# Titan_v1p7.net
KiCad netlist of a schematic drawn in EAGLE
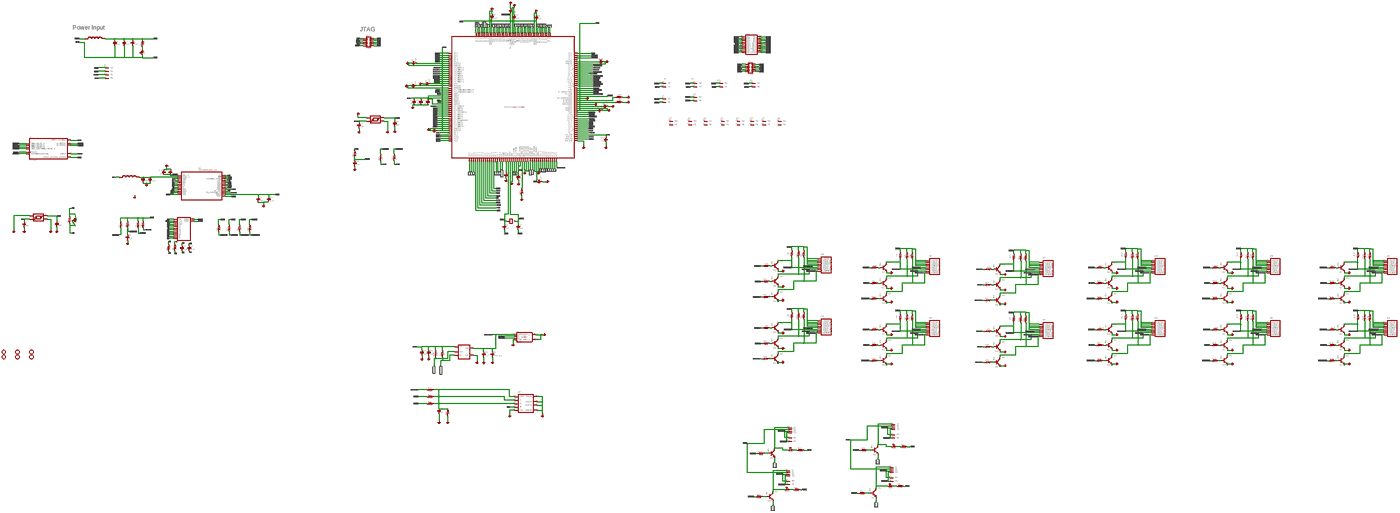
[diagram p0: schematic, sheet 1, overview]
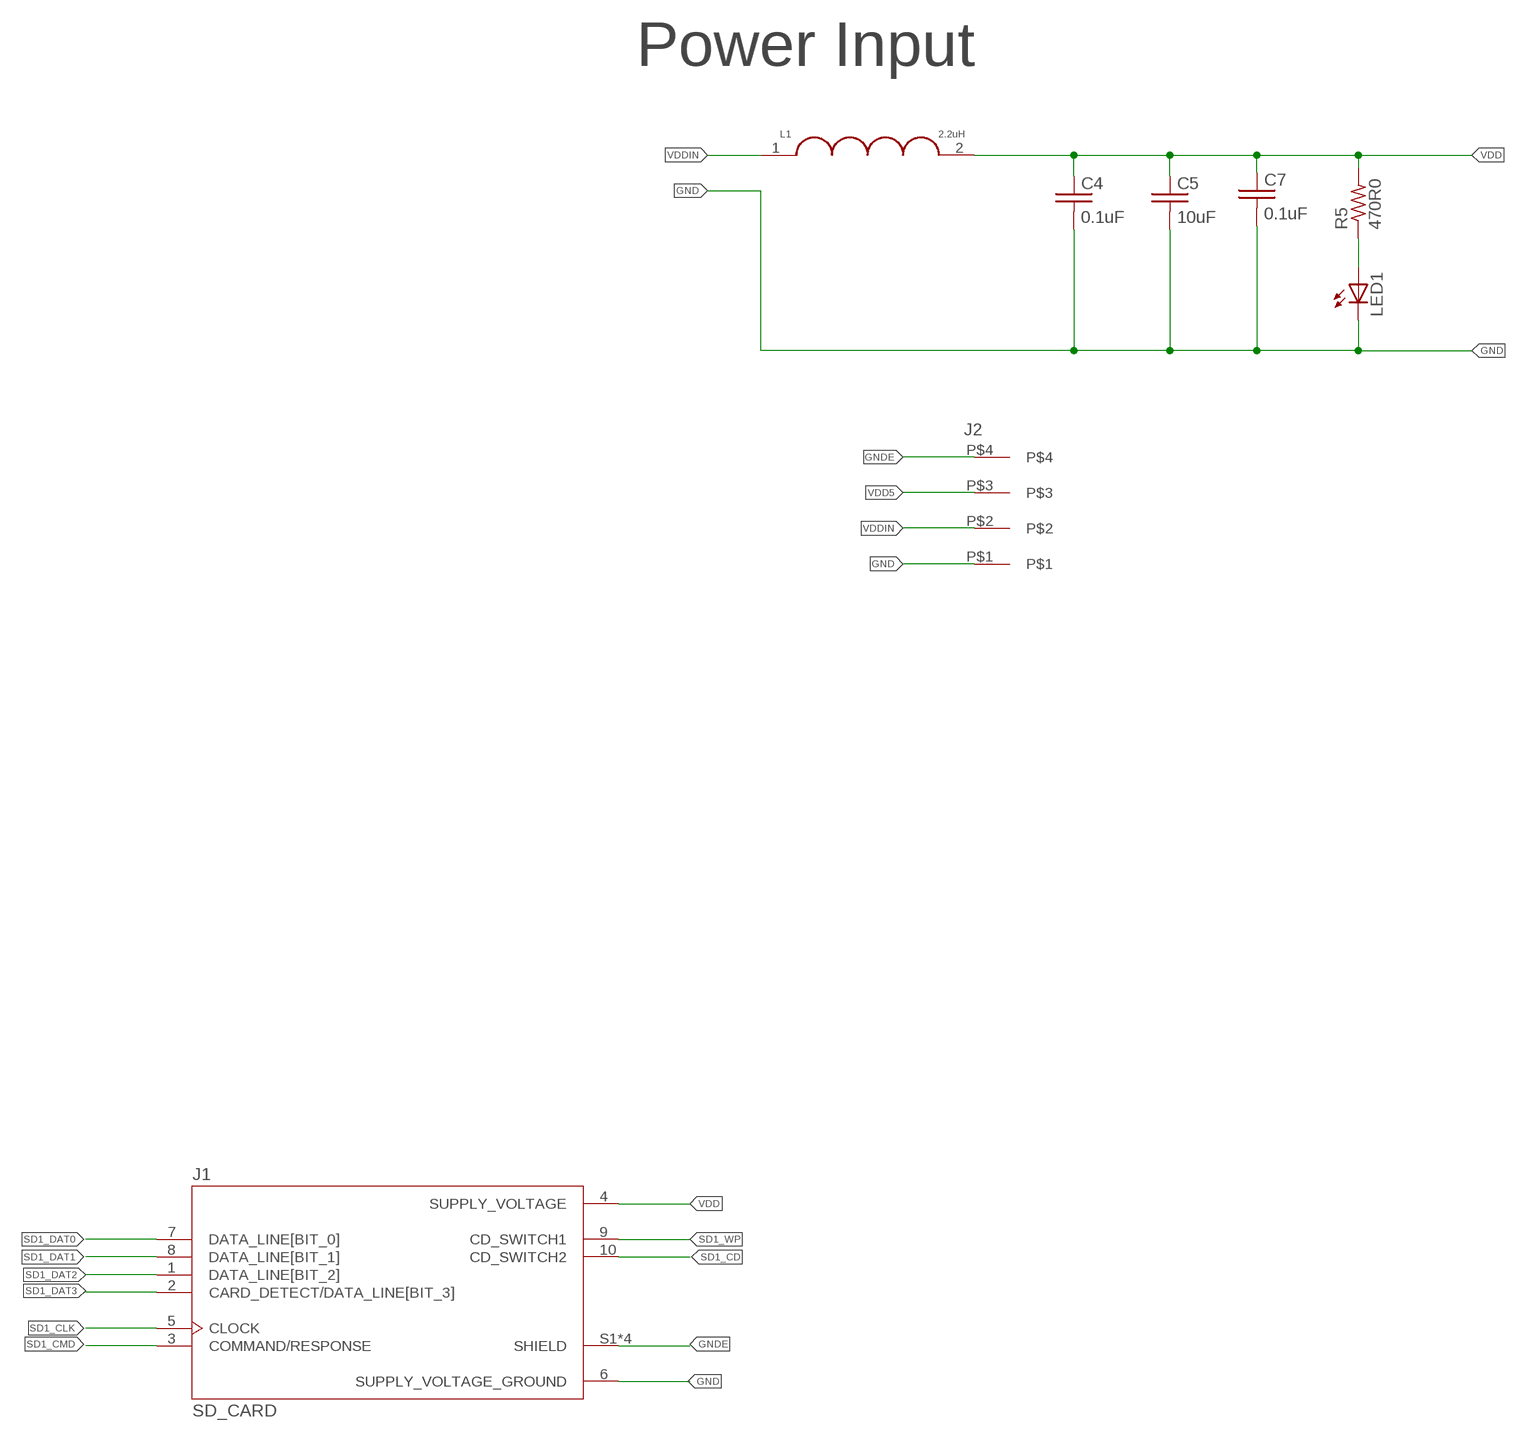
[diagram p1: schematic, sheet 1, part 1 of 8]
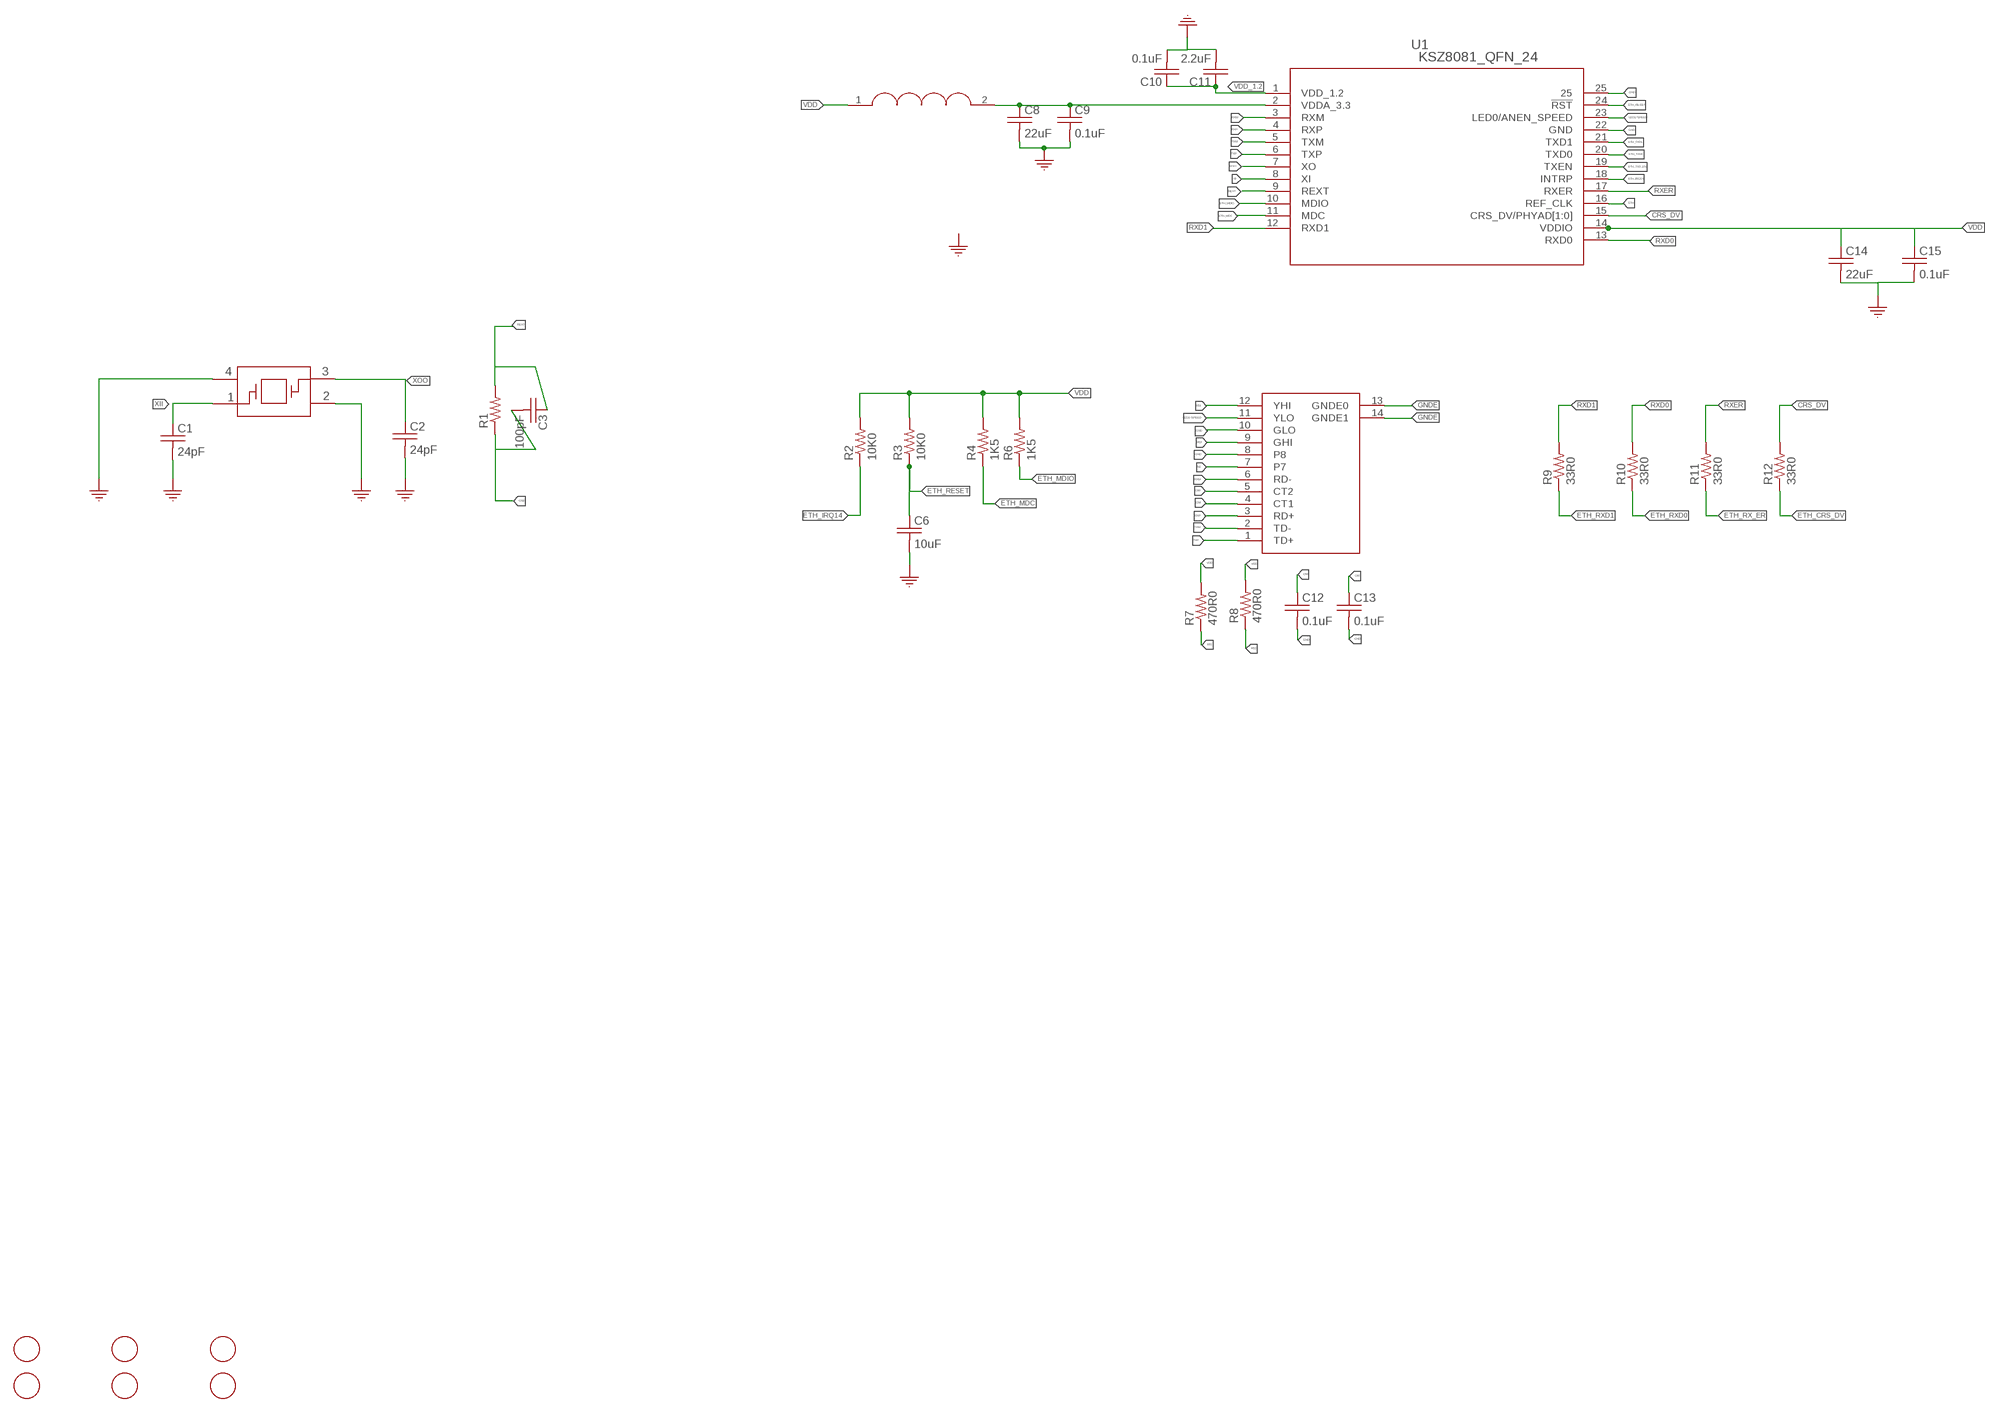
[diagram p2: schematic, sheet 1, part 2 of 8]
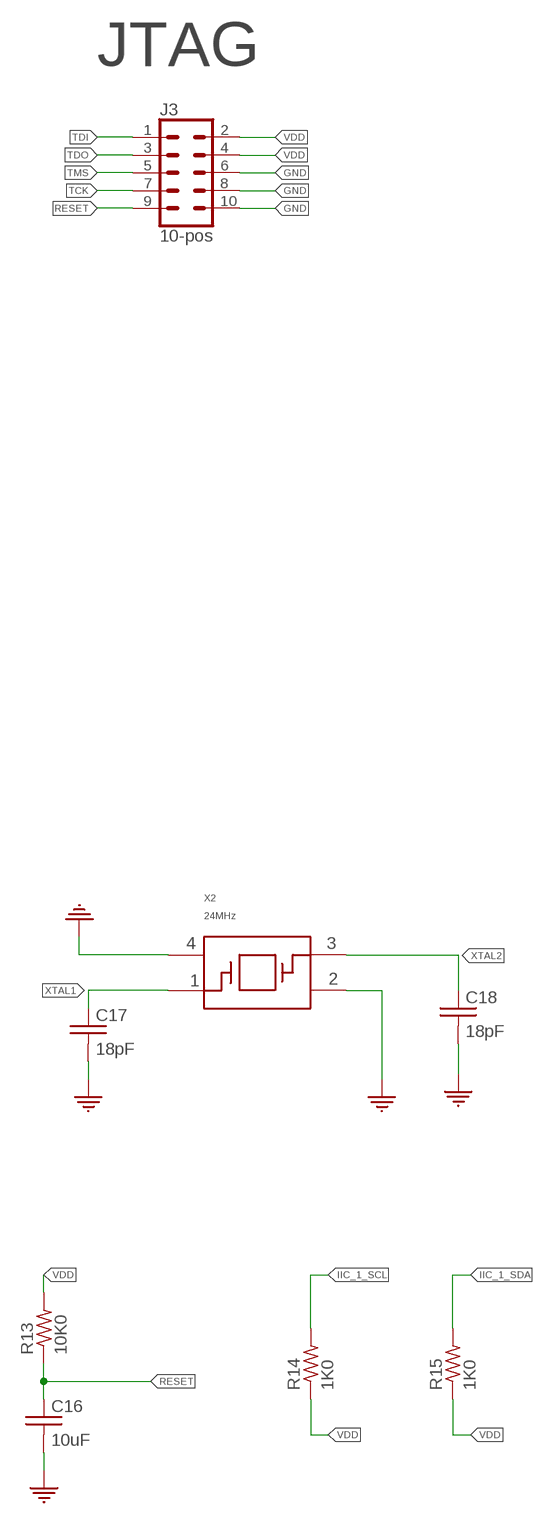
[diagram p3: schematic, sheet 1, part 3 of 8]
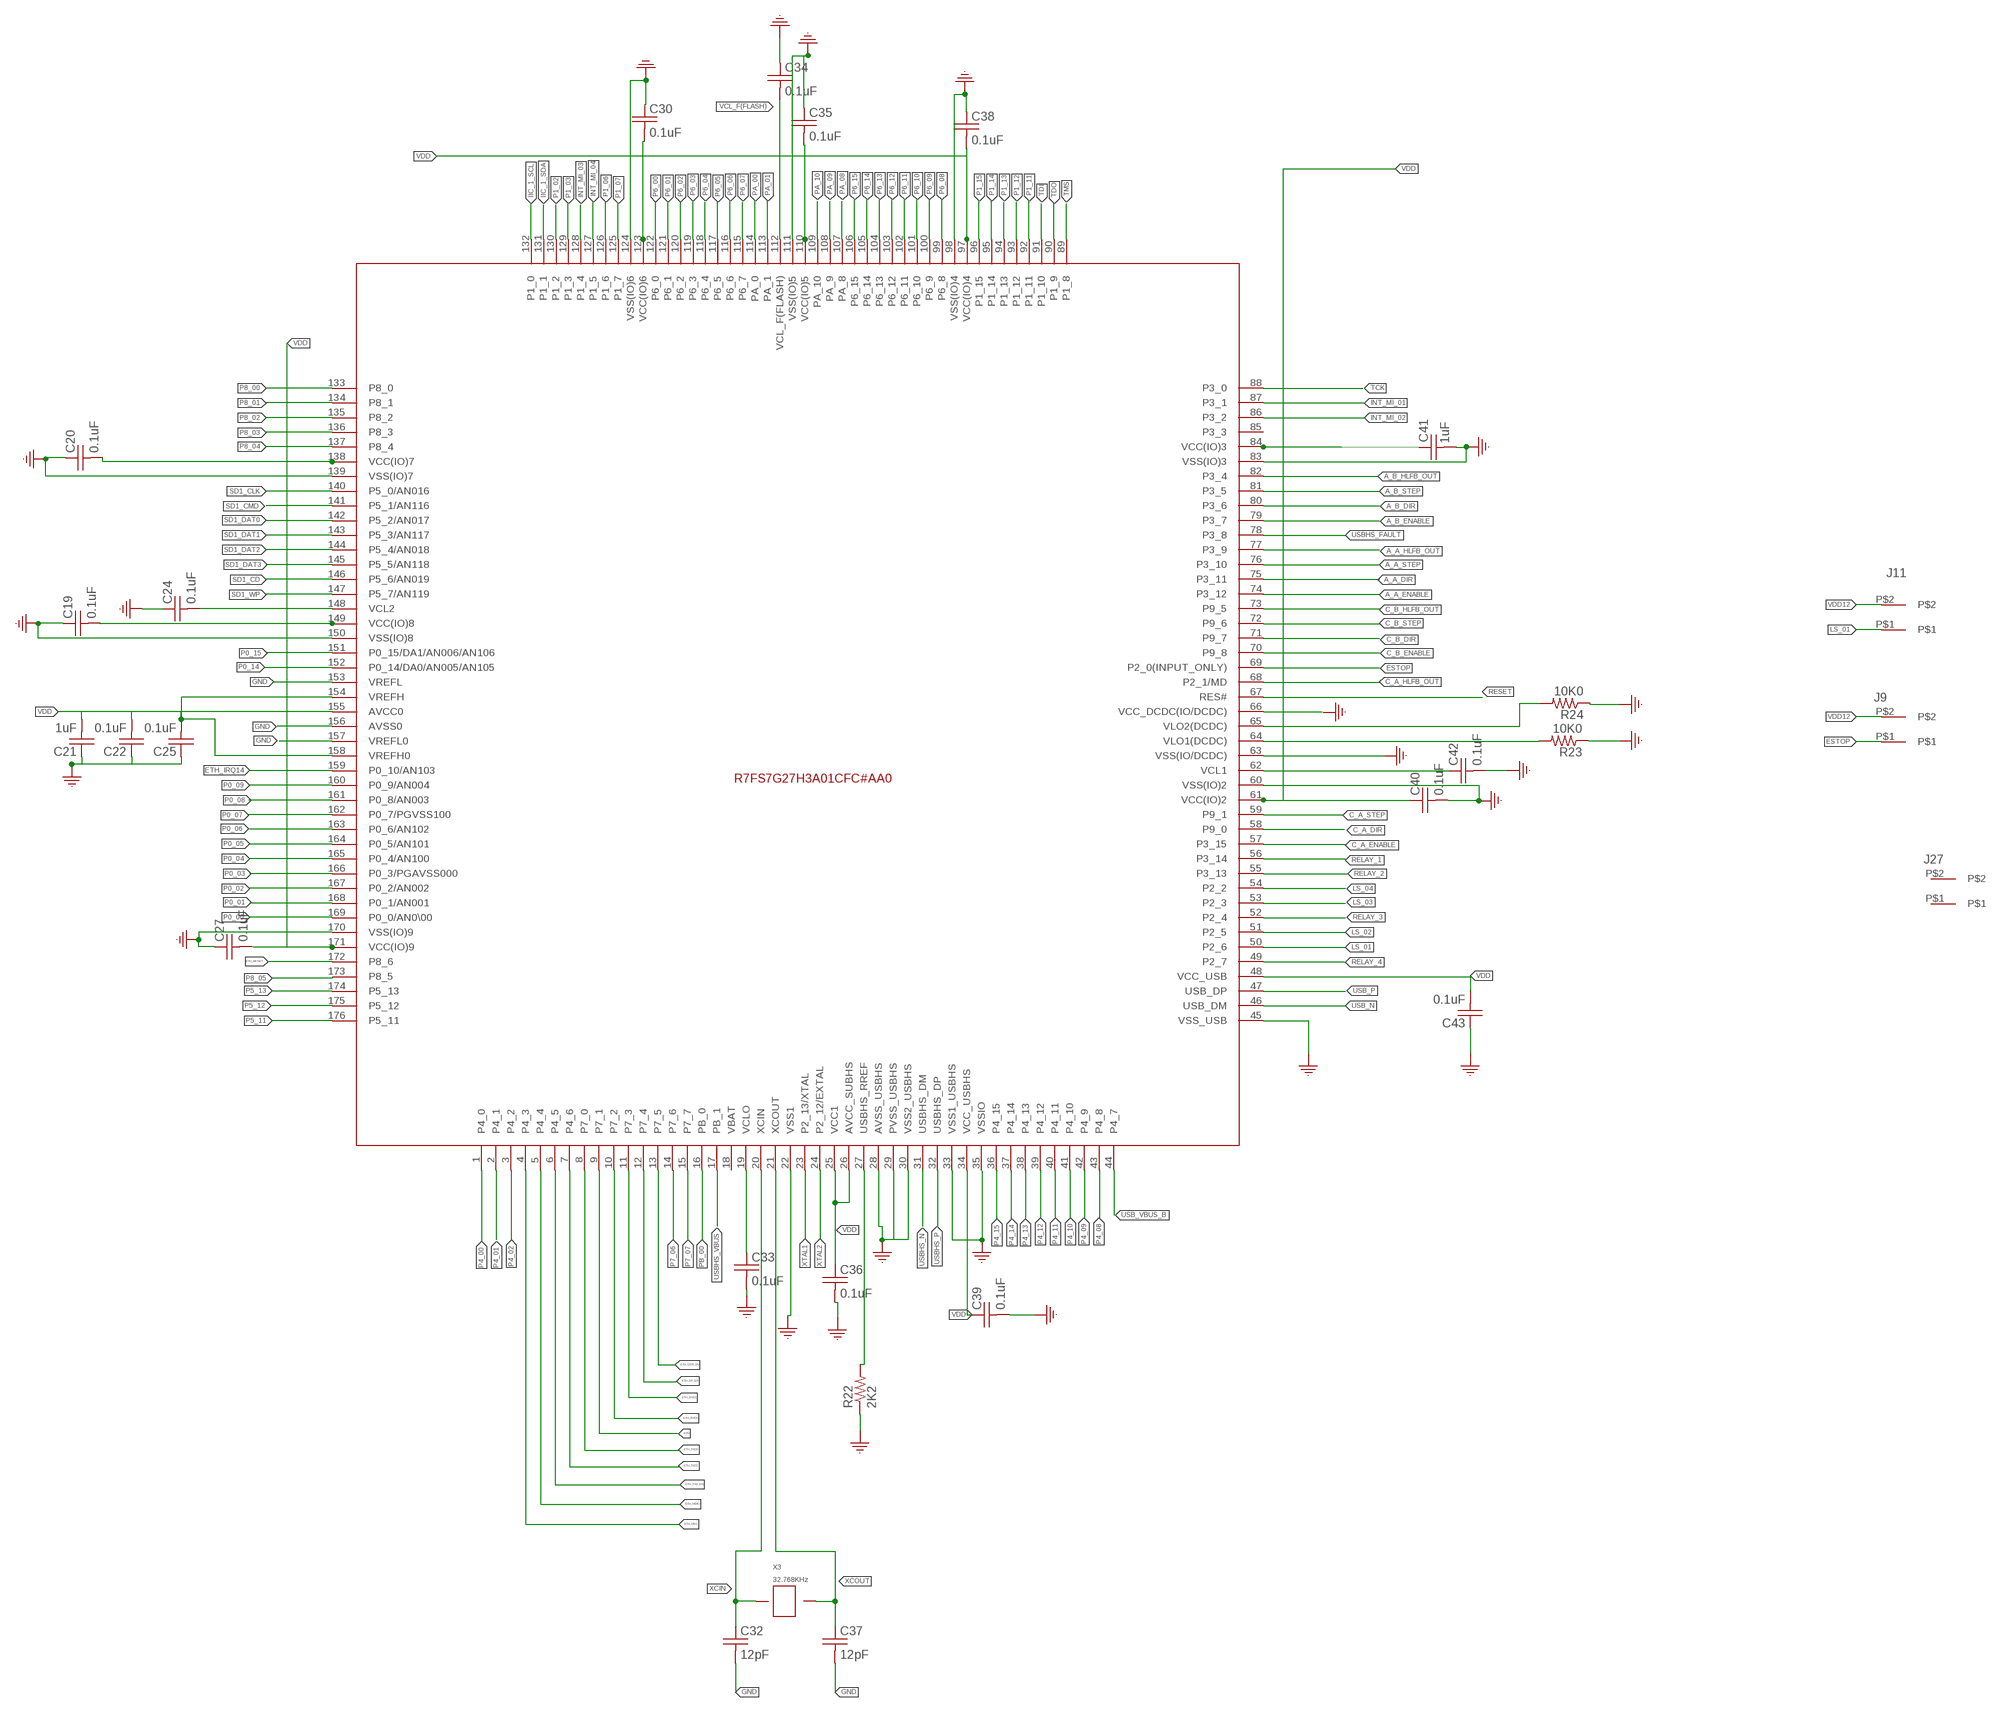
[diagram p4: schematic, sheet 1, part 4 of 8]
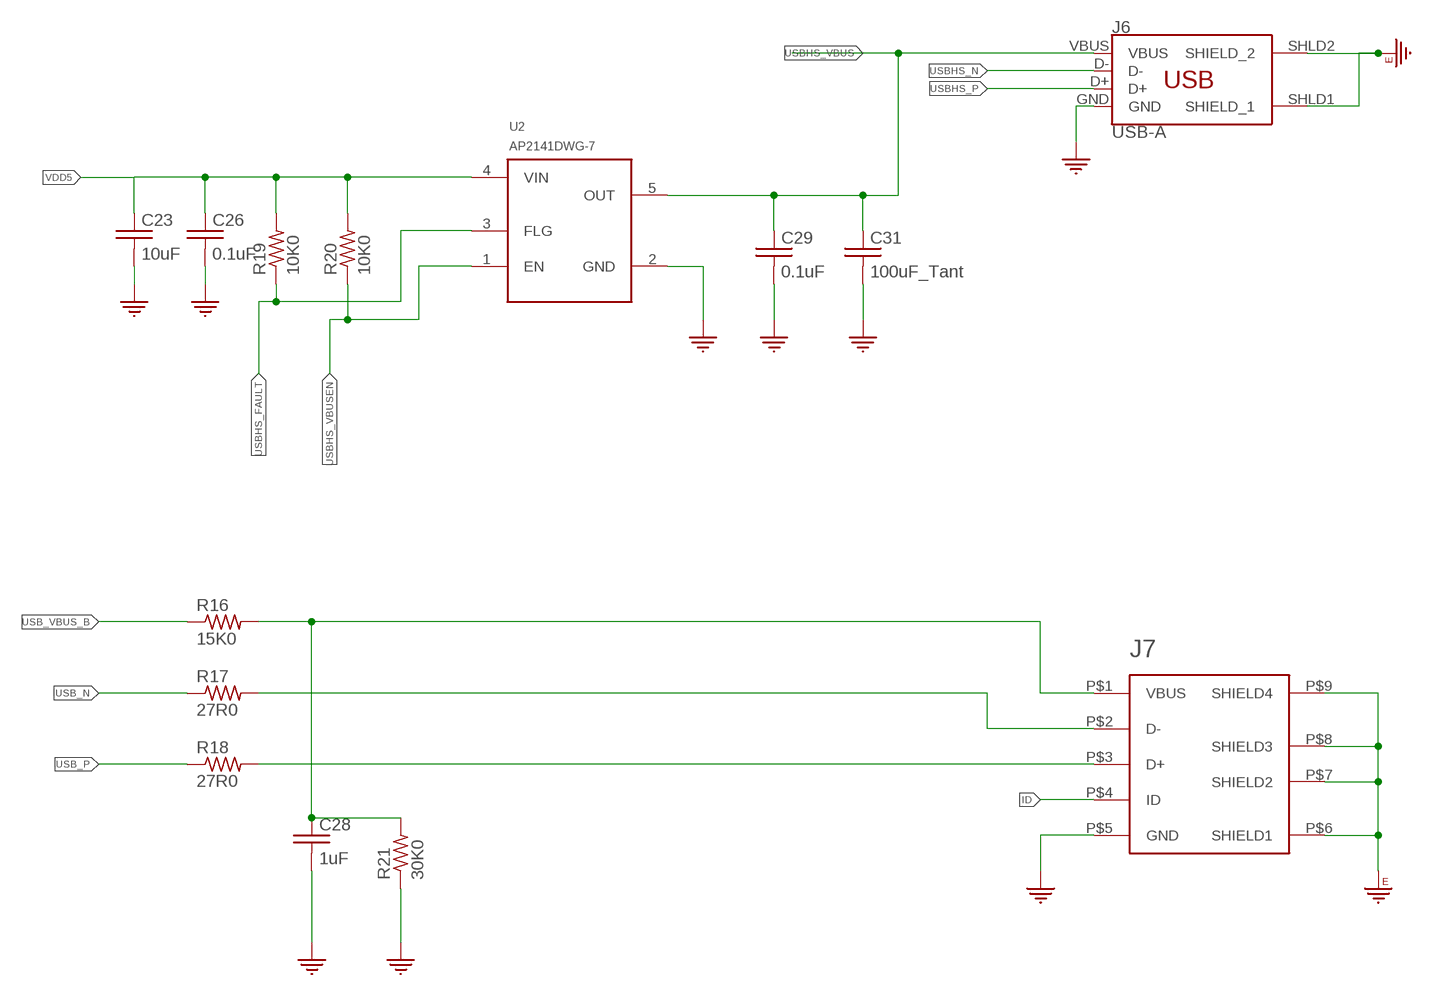
[diagram p5: schematic, sheet 1, part 5 of 8]
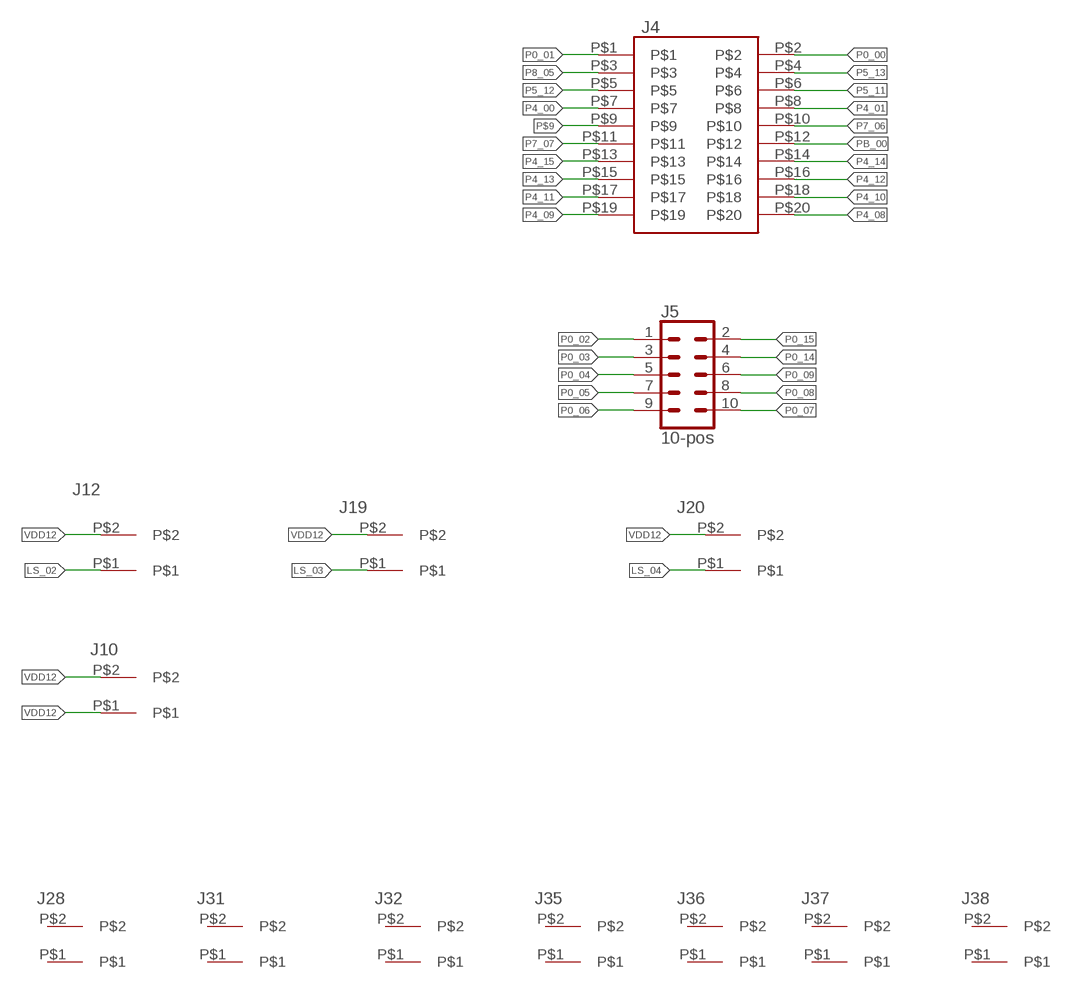
[diagram p6: schematic, sheet 1, part 6 of 8]
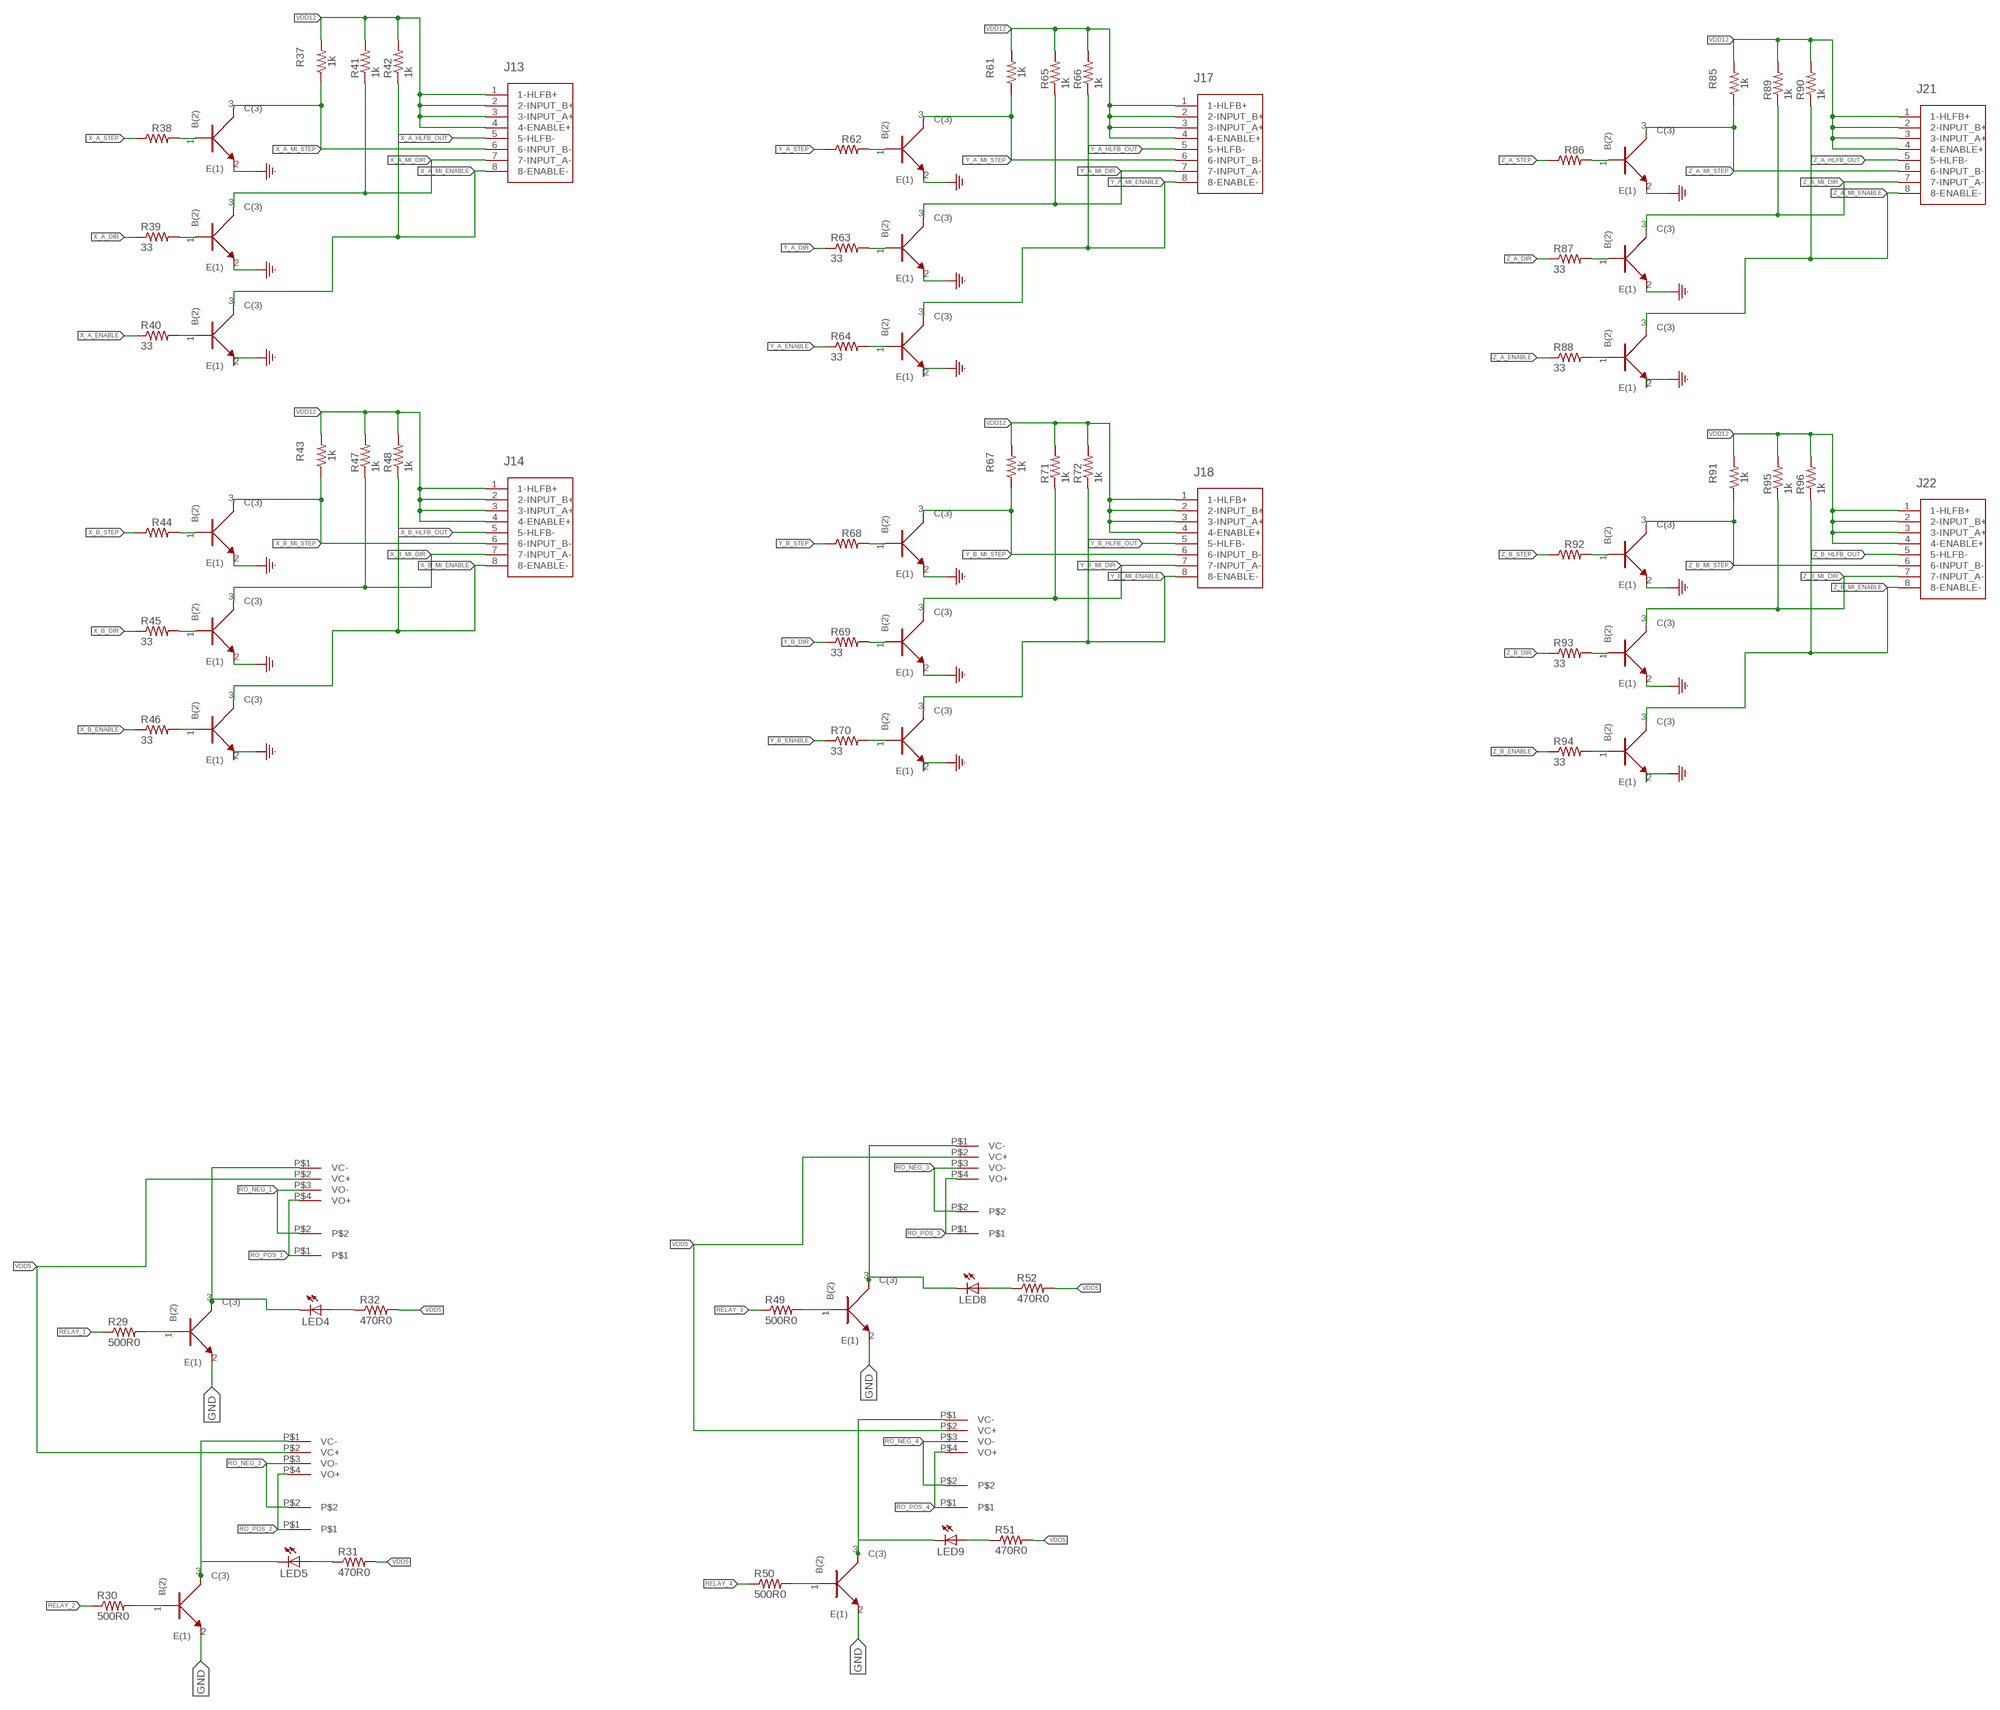
[diagram p7: schematic, sheet 1, part 7 of 8]
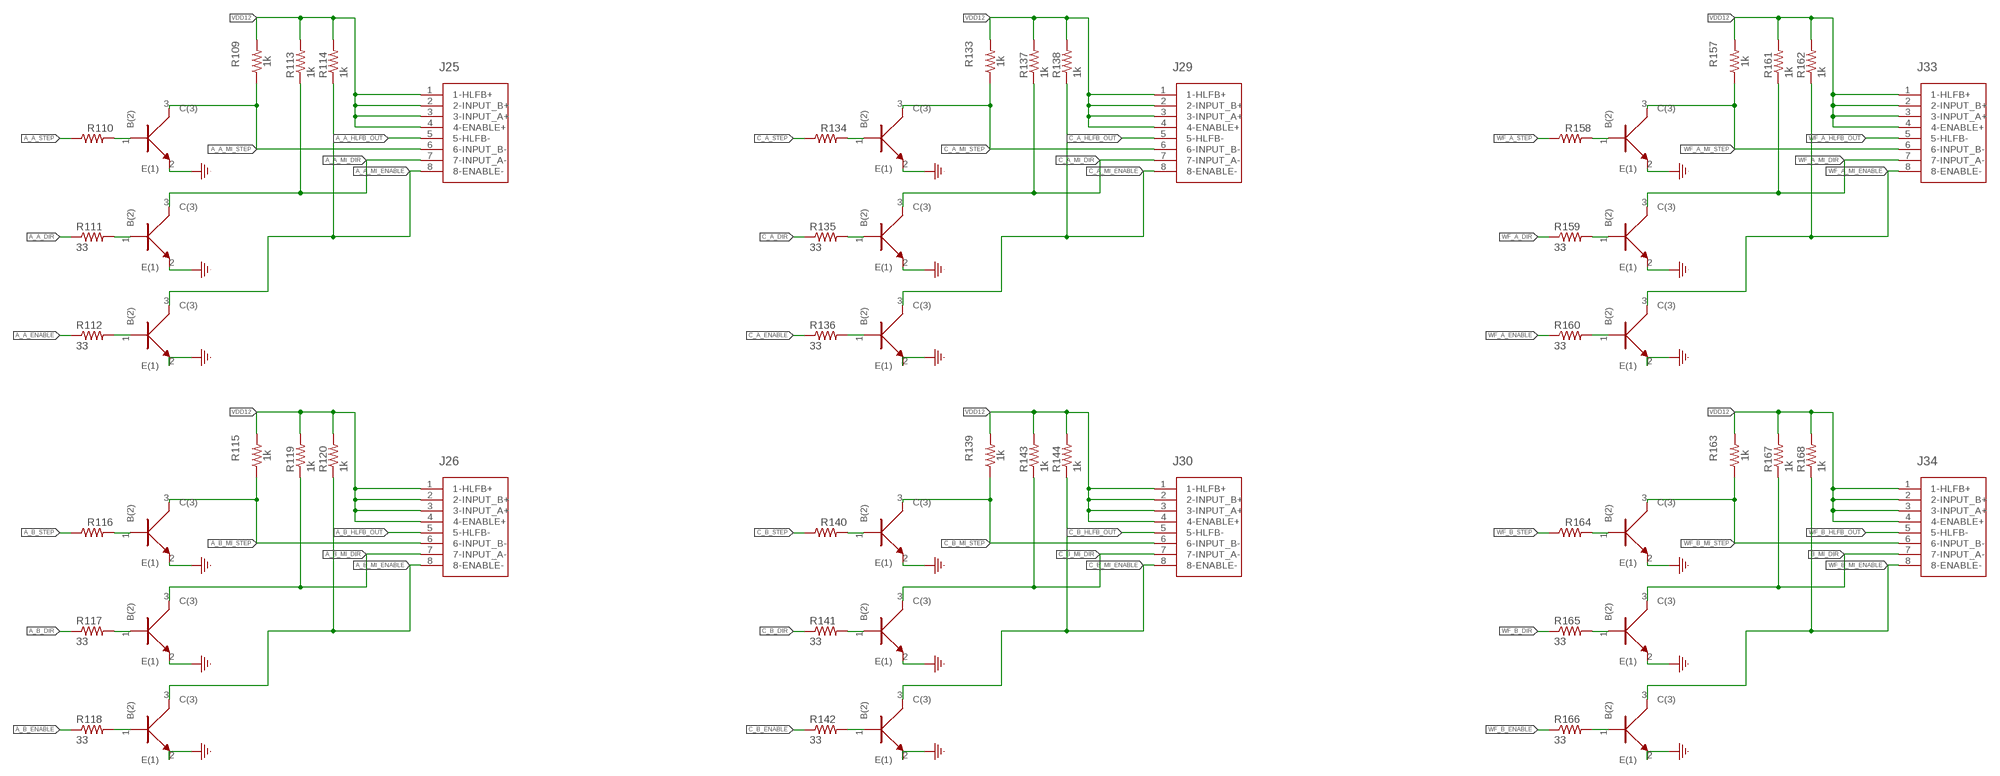
[diagram p8: schematic, sheet 1, part 8 of 8]

(export (version "E")
  (design (tool "Eeschema 10.0.6"))
  (components
    (comp (ref "AFID1")
      (value "FIDUCIAL_1MM")
      (footprint "eagle-import:FIDUCIAL_1MM")
      (libsource (lib "eagle-import") (part "FIDUCIAL_1MM"))
    )
    (comp (ref "AFID2")
      (value "FIDUCIAL_1MM")
      (footprint "eagle-import:FIDUCIAL_1MM")
      (libsource (lib "eagle-import") (part "FIDUCIAL_1MM"))
    )
    (comp (ref "AFID3")
      (value "FIDUCIAL_1MM")
      (footprint "eagle-import:FIDUCIAL_1MM")
      (libsource (lib "eagle-import") (part "FIDUCIAL_1MM"))
    )
    (comp (ref "AFID4")
      (value "FIDUCIAL_1MM")
      (footprint "eagle-import:FIDUCIAL_1MM")
      (libsource (lib "eagle-import") (part "FIDUCIAL_1MM"))
    )
    (comp (ref "AFID5")
      (value "FIDUCIAL_1MM")
      (footprint "eagle-import:FIDUCIAL_1MM")
      (libsource (lib "eagle-import") (part "FIDUCIAL_1MM"))
    )
    (comp (ref "AFID6")
      (value "FIDUCIAL_1MM")
      (footprint "eagle-import:FIDUCIAL_1MM")
      (libsource (lib "eagle-import") (part "FIDUCIAL_1MM"))
    )
    (comp (ref "C1")
      (value "24pF")
      (footprint "eagle-import:0402")
      (fields (field (name "PARTNO") "CC0402GRNPO9BN240"))
      (libsource (lib "eagle-import") (part "C_0402_24PF"))
    )
    (comp (ref "C2")
      (value "24pF")
      (footprint "eagle-import:0402")
      (fields (field (name "PARTNO") "CC0402GRNPO9BN240"))
      (libsource (lib "eagle-import") (part "C_0402_24PF"))
    )
    (comp (ref "C3")
      (value "100pF")
      (footprint "eagle-import:0402")
      (fields (field (name "PARTNO") "CL05C101JB5NNNC"))
      (libsource (lib "eagle-import") (part "C_0402_100PF"))
    )
    (comp (ref "C4")
      (value "0.1uF")
      (footprint "eagle-import:0402")
      (fields (field (name "PARTNO") "CL05F104ZO5NNNC"))
      (libsource (lib "eagle-import") (part "C_0402_0.1UF"))
    )
    (comp (ref "C5")
      (value "10uF")
      (footprint "eagle-import:0402")
      (fields (field (name "PARTNO") "CL05A106MP8NUB8"))
      (libsource (lib "eagle-import") (part "C_0402_10UF"))
    )
    (comp (ref "C6")
      (value "10uF")
      (footprint "eagle-import:0402")
      (fields (field (name "PARTNO") "CL05A106MP8NUB8"))
      (libsource (lib "eagle-import") (part "C_0402_10UF"))
    )
    (comp (ref "C7")
      (value "0.1uF")
      (footprint "eagle-import:0402")
      (fields (field (name "PARTNO") "CL05F104ZO5NNNC"))
      (libsource (lib "eagle-import") (part "C_0402_0.1UF"))
    )
    (comp (ref "C8")
      (value "22uF")
      (footprint "eagle-import:0402")
      (fields (field (name "PARTNO") "CL05A226MQ5N6J8"))
      (libsource (lib "eagle-import") (part "C_0402_22UF"))
    )
    (comp (ref "C9")
      (value "0.1uF")
      (footprint "eagle-import:0402")
      (fields (field (name "PARTNO") "CL05F104ZO5NNNC"))
      (libsource (lib "eagle-import") (part "C_0402_0.1UF"))
    )
    (comp (ref "C10")
      (value "0.1uF")
      (footprint "eagle-import:0402")
      (fields (field (name "PARTNO") "CL05F104ZO5NNNC"))
      (libsource (lib "eagle-import") (part "C_0402_0.1UF"))
    )
    (comp (ref "C11")
      (value "2.2uF")
      (footprint "eagle-import:0402")
      (fields (field (name "PARTNO") "GRM155C81C225ME15D"))
      (libsource (lib "eagle-import") (part "C_0402_2.2UF"))
    )
    (comp (ref "C12")
      (value "0.1uF")
      (footprint "eagle-import:0402")
      (fields (field (name "PARTNO") "CL05F104ZO5NNNC"))
      (libsource (lib "eagle-import") (part "C_0402_0.1UF"))
    )
    (comp (ref "C13")
      (value "0.1uF")
      (footprint "eagle-import:0402")
      (fields (field (name "PARTNO") "CL05F104ZO5NNNC"))
      (libsource (lib "eagle-import") (part "C_0402_0.1UF"))
    )
    (comp (ref "C14")
      (value "22uF")
      (footprint "eagle-import:0402")
      (fields (field (name "PARTNO") "CL05A226MQ5N6J8"))
      (libsource (lib "eagle-import") (part "C_0402_22UF"))
    )
    (comp (ref "C15")
      (value "0.1uF")
      (footprint "eagle-import:0402")
      (fields (field (name "PARTNO") "CL05F104ZO5NNNC"))
      (libsource (lib "eagle-import") (part "C_0402_0.1UF"))
    )
    (comp (ref "C16")
      (value "10uF")
      (footprint "eagle-import:0402")
      (fields (field (name "PARTNO") "CL05A106MP8NUB8"))
      (libsource (lib "eagle-import") (part "C_0402_10UF"))
    )
    (comp (ref "C17")
      (value "18pF")
      (footprint "eagle-import:0402")
      (fields (field (name "PARTNO") "UMK105CG180JV-F"))
      (libsource (lib "eagle-import") (part "C_0402_18PF"))
    )
    (comp (ref "C18")
      (value "18pF")
      (footprint "eagle-import:0402")
      (fields (field (name "PARTNO") "UMK105CG180JV-F"))
      (libsource (lib "eagle-import") (part "C_0402_18PF"))
    )
    (comp (ref "C19")
      (value "0.1uF")
      (footprint "eagle-import:0402")
      (fields (field (name "PARTNO") "CL05F104ZO5NNNC"))
      (libsource (lib "eagle-import") (part "C_0402_0.1UF"))
    )
    (comp (ref "C20")
      (value "0.1uF")
      (footprint "eagle-import:0402")
      (fields (field (name "PARTNO") "CL05F104ZO5NNNC"))
      (libsource (lib "eagle-import") (part "C_0402_0.1UF"))
    )
    (comp (ref "C21")
      (value "1uF")
      (footprint "eagle-import:0402")
      (fields (field (name "PARTNO") "CL05A105KO5NNNC"))
      (libsource (lib "eagle-import") (part "C_0402_1UF"))
    )
    (comp (ref "C22")
      (value "0.1uF")
      (footprint "eagle-import:0402")
      (fields (field (name "PARTNO") "CL05F104ZO5NNNC"))
      (libsource (lib "eagle-import") (part "C_0402_0.1UF"))
    )
    (comp (ref "C23")
      (value "10uF")
      (footprint "eagle-import:0402")
      (fields (field (name "PARTNO") "CL05A106MP8NUB8"))
      (libsource (lib "eagle-import") (part "C_0402_10UF"))
    )
    (comp (ref "C24")
      (value "0.1uF")
      (footprint "eagle-import:0402")
      (fields (field (name "PARTNO") "CL05F104ZO5NNNC"))
      (libsource (lib "eagle-import") (part "C_0402_0.1UF"))
    )
    (comp (ref "C25")
      (value "0.1uF")
      (footprint "eagle-import:0402")
      (fields (field (name "PARTNO") "CL05F104ZO5NNNC"))
      (libsource (lib "eagle-import") (part "C_0402_0.1UF"))
    )
    (comp (ref "C26")
      (value "0.1uF")
      (footprint "eagle-import:0402")
      (fields (field (name "PARTNO") "CL05F104ZO5NNNC"))
      (libsource (lib "eagle-import") (part "C_0402_0.1UF"))
    )
    (comp (ref "C27")
      (value "0.1uF")
      (footprint "eagle-import:0402")
      (fields (field (name "PARTNO") "CL05F104ZO5NNNC"))
      (libsource (lib "eagle-import") (part "C_0402_0.1UF"))
    )
    (comp (ref "C28")
      (value "1uF")
      (footprint "eagle-import:0402")
      (fields (field (name "PARTNO") "CL05A105KO5NNNC"))
      (libsource (lib "eagle-import") (part "C_0402_1UF"))
    )
    (comp (ref "C29")
      (value "0.1uF")
      (footprint "eagle-import:0402")
      (fields (field (name "PARTNO") "CL05F104ZO5NNNC"))
      (libsource (lib "eagle-import") (part "C_0402_0.1UF"))
    )
    (comp (ref "C30")
      (value "0.1uF")
      (footprint "eagle-import:0402")
      (fields (field (name "PARTNO") "CL05F104ZO5NNNC"))
      (libsource (lib "eagle-import") (part "C_0402_0.1UF"))
    )
    (comp (ref "C31")
      (value "100uF_Tant")
      (footprint "eagle-import:C1210")
      (fields (field (name "PARTNO") "TLJT107M010R0900"))
      (libsource (lib "eagle-import") (part "C_1210_100UF_TANT"))
    )
    (comp (ref "C32")
      (value "12pF")
      (footprint "eagle-import:0402")
      (fields (field (name "PARTNO") "CL05C120JB5NNNC"))
      (libsource (lib "eagle-import") (part "C_0402_12PF"))
    )
    (comp (ref "C33")
      (value "0.1uF")
      (footprint "eagle-import:0402")
      (fields (field (name "PARTNO") "CL05F104ZO5NNNC"))
      (libsource (lib "eagle-import") (part "C_0402_0.1UF"))
    )
    (comp (ref "C34")
      (value "0.1uF")
      (footprint "eagle-import:0402")
      (fields (field (name "PARTNO") "CL05F104ZO5NNNC"))
      (libsource (lib "eagle-import") (part "C_0402_0.1UF"))
    )
    (comp (ref "C35")
      (value "0.1uF")
      (footprint "eagle-import:0402")
      (fields (field (name "PARTNO") "CL05F104ZO5NNNC"))
      (libsource (lib "eagle-import") (part "C_0402_0.1UF"))
    )
    (comp (ref "C36")
      (value "0.1uF")
      (footprint "eagle-import:0402")
      (fields (field (name "PARTNO") "CL05F104ZO5NNNC"))
      (libsource (lib "eagle-import") (part "C_0402_0.1UF"))
    )
    (comp (ref "C37")
      (value "12pF")
      (footprint "eagle-import:0402")
      (fields (field (name "PARTNO") "CL05C120JB5NNNC"))
      (libsource (lib "eagle-import") (part "C_0402_12PF"))
    )
    (comp (ref "C38")
      (value "0.1uF")
      (footprint "eagle-import:0402")
      (fields (field (name "PARTNO") "CL05F104ZO5NNNC"))
      (libsource (lib "eagle-import") (part "C_0402_0.1UF"))
    )
    (comp (ref "C39")
      (value "0.1uF")
      (footprint "eagle-import:0402")
      (fields (field (name "PARTNO") "CL05F104ZO5NNNC"))
      (libsource (lib "eagle-import") (part "C_0402_0.1UF"))
    )
    (comp (ref "C40")
      (value "0.1uF")
      (footprint "eagle-import:0402")
      (fields (field (name "PARTNO") "CL05F104ZO5NNNC"))
      (libsource (lib "eagle-import") (part "C_0402_0.1UF"))
    )
    (comp (ref "C41")
      (value "1uF")
      (footprint "eagle-import:0402")
      (fields (field (name "PARTNO") "CL05A105KO5NNNC"))
      (libsource (lib "eagle-import") (part "C_0402_1UF"))
    )
    (comp (ref "C42")
      (value "0.1uF")
      (footprint "eagle-import:0402")
      (fields (field (name "PARTNO") "CL05F104ZO5NNNC"))
      (libsource (lib "eagle-import") (part "C_0402_0.1UF"))
    )
    (comp (ref "C43")
      (value "0.1uF")
      (footprint "eagle-import:0402")
      (fields (field (name "PARTNO") "CL05F104ZO5NNNC"))
      (libsource (lib "eagle-import") (part "C_0402_0.1UF"))
    )
    (comp (ref "FB1")
      (value "FB2_603")
      (footprint "eagle-import:0603")
      (fields (field (name "PARTNO") "BLM18PG121SN1D"))
      (libsource (lib "eagle-import") (part "FB_0603_120_OHM0603"))
    )
    (comp (ref "J1")
      (value "SD_CARD")
      (footprint "eagle-import:SD_CARD")
      (fields (field (name "MF") "Amphenol ICC") (field (name "PARTNO") "114-00841-68"))
      (libsource (lib "eagle-import") (part "SD_CARD_1140084168"))
    )
    (comp (ref "J2")
      (value "4-pos")
      (footprint "eagle-import:1X4_3.81MM_PITCH")
      (fields (field (name "PARTNO") "691322310004"))
      (libsource (lib "eagle-import") (part "3.81MM_1_X_4_RT_ANGLE_PLUG_HEADER"))
    )
    (comp (ref "J3")
      (value "10-pos")
      (footprint "eagle-import:2X5")
      (fields (field (name "PARTNO") "PH2RA-10-UA"))
      (libsource (lib "eagle-import") (part "CONN_05X2_RAPTH"))
    )
    (comp (ref "J4")
      (value "20-pos")
      (footprint "eagle-import:2_X_10_.1_INCH")
      (fields (field (name "PARTNO") "67996-420HLF"))
      (libsource (lib "eagle-import") (part "2_X_10_HEADER_GENERIC"))
    )
    (comp (ref "J5")
      (value "10-pos")
      (footprint "eagle-import:2X5")
      (fields (field (name "PARTNO") "PH2RA-10-UA"))
      (libsource (lib "eagle-import") (part "CONN_05X2_RAPTH"))
    )
    (comp (ref "J6")
      (value "USB-A")
      (footprint "eagle-import:USB_A_SMT")
      (fields (field (name "PARTNO") "87583-3010RPALF"))
      (libsource (lib "eagle-import") (part "USB_A"))
    )
    (comp (ref "J7")
      (value "USB-B-Micro")
      (footprint "eagle-import:USB_MICRO-B")
      (fields (field (name "PARTNO") "10118192-0002LF"))
      (libsource (lib "eagle-import") (part "USB_MICRO-B"))
    )
    (comp (ref "J9")
      (value "2-pos")
      (footprint "eagle-import:2_3.81MM_PITCH")
      (fields (field (name "PARTNO") "691322310002"))
      (libsource (lib "eagle-import") (part "3.81MM_1_X_2_RT_ANGLE_PLUG_HEADER"))
    )
    (comp (ref "J10")
      (value "2-pos")
      (footprint "eagle-import:2_3.81MM_PITCH")
      (fields (field (name "PARTNO") "691322310002"))
      (libsource (lib "eagle-import") (part "3.81MM_1_X_2_RT_ANGLE_PLUG_HEADER"))
    )
    (comp (ref "J11")
      (value "2-pos")
      (footprint "eagle-import:2_3.81MM_PITCH")
      (fields (field (name "PARTNO") "691322310002"))
      (libsource (lib "eagle-import") (part "3.81MM_1_X_2_RT_ANGLE_PLUG_HEADER"))
    )
    (comp (ref "J12")
      (value "2-pos")
      (footprint "eagle-import:2_3.81MM_PITCH")
      (fields (field (name "PARTNO") "691322310002"))
      (libsource (lib "eagle-import") (part "3.81MM_1_X_2_RT_ANGLE_PLUG_HEADER"))
    )
    (comp (ref "J13")
      (value "TEKNIC_8PIN_MOTOR")
      (footprint "eagle-import:CON_39281083")
      (fields
        (field (name "MANUFACTURER_PART_NUMBER") "39281083")
        (field (name "COPYRIGHT") "Copyright (C) 2022 Ultra Librarian. All rights reserved.")
      )
      (libsource (lib "eagle-import") (part "TEKNIC_8PIN_MOTOR"))
    )
    (comp (ref "J14")
      (value "TEKNIC_8PIN_MOTOR")
      (footprint "eagle-import:CON_39281083")
      (fields
        (field (name "MANUFACTURER_PART_NUMBER") "39281083")
        (field (name "COPYRIGHT") "Copyright (C) 2022 Ultra Librarian. All rights reserved.")
      )
      (libsource (lib "eagle-import") (part "TEKNIC_8PIN_MOTOR"))
    )
    (comp (ref "J15")
      (value "2-pos")
      (footprint "eagle-import:2_3.81MM_PITCH")
      (fields (field (name "PARTNO") "691322310002"))
      (libsource (lib "eagle-import") (part "3.81MM_1_X_2_RT_ANGLE_PLUG_HEADER"))
    )
    (comp (ref "J16")
      (value "2-pos")
      (footprint "eagle-import:2_3.81MM_PITCH")
      (fields (field (name "PARTNO") "691322310002"))
      (libsource (lib "eagle-import") (part "3.81MM_1_X_2_RT_ANGLE_PLUG_HEADER"))
    )
    (comp (ref "J17")
      (value "TEKNIC_8PIN_MOTOR")
      (footprint "eagle-import:CON_39281083")
      (fields
        (field (name "MANUFACTURER_PART_NUMBER") "39281083")
        (field (name "COPYRIGHT") "Copyright (C) 2022 Ultra Librarian. All rights reserved.")
      )
      (libsource (lib "eagle-import") (part "TEKNIC_8PIN_MOTOR"))
    )
    (comp (ref "J18")
      (value "TEKNIC_8PIN_MOTOR")
      (footprint "eagle-import:CON_39281083")
      (fields
        (field (name "MANUFACTURER_PART_NUMBER") "39281083")
        (field (name "COPYRIGHT") "Copyright (C) 2022 Ultra Librarian. All rights reserved.")
      )
      (libsource (lib "eagle-import") (part "TEKNIC_8PIN_MOTOR"))
    )
    (comp (ref "J19")
      (value "2-pos")
      (footprint "eagle-import:2_3.81MM_PITCH")
      (fields (field (name "PARTNO") "691322310002"))
      (libsource (lib "eagle-import") (part "3.81MM_1_X_2_RT_ANGLE_PLUG_HEADER"))
    )
    (comp (ref "J20")
      (value "2-pos")
      (footprint "eagle-import:2_3.81MM_PITCH")
      (fields (field (name "PARTNO") "691322310002"))
      (libsource (lib "eagle-import") (part "3.81MM_1_X_2_RT_ANGLE_PLUG_HEADER"))
    )
    (comp (ref "J21")
      (value "TEKNIC_8PIN_MOTOR")
      (footprint "eagle-import:CON_39281083")
      (fields
        (field (name "MANUFACTURER_PART_NUMBER") "39281083")
        (field (name "COPYRIGHT") "Copyright (C) 2022 Ultra Librarian. All rights reserved.")
      )
      (libsource (lib "eagle-import") (part "TEKNIC_8PIN_MOTOR"))
    )
    (comp (ref "J22")
      (value "TEKNIC_8PIN_MOTOR")
      (footprint "eagle-import:CON_39281083")
      (fields
        (field (name "MANUFACTURER_PART_NUMBER") "39281083")
        (field (name "COPYRIGHT") "Copyright (C) 2022 Ultra Librarian. All rights reserved.")
      )
      (libsource (lib "eagle-import") (part "TEKNIC_8PIN_MOTOR"))
    )
    (comp (ref "J23")
      (value "2-pos")
      (footprint "eagle-import:2_3.81MM_PITCH")
      (fields (field (name "PARTNO") "691322310002"))
      (libsource (lib "eagle-import") (part "3.81MM_1_X_2_RT_ANGLE_PLUG_HEADER"))
    )
    (comp (ref "J24")
      (value "2-pos")
      (footprint "eagle-import:2_3.81MM_PITCH")
      (fields (field (name "PARTNO") "691322310002"))
      (libsource (lib "eagle-import") (part "3.81MM_1_X_2_RT_ANGLE_PLUG_HEADER"))
    )
    (comp (ref "J25")
      (value "TEKNIC_8PIN_MOTOR")
      (footprint "eagle-import:CON_39281083")
      (fields
        (field (name "MANUFACTURER_PART_NUMBER") "39281083")
        (field (name "COPYRIGHT") "Copyright (C) 2022 Ultra Librarian. All rights reserved.")
      )
      (libsource (lib "eagle-import") (part "TEKNIC_8PIN_MOTOR"))
    )
    (comp (ref "J26")
      (value "TEKNIC_8PIN_MOTOR")
      (footprint "eagle-import:CON_39281083")
      (fields
        (field (name "MANUFACTURER_PART_NUMBER") "39281083")
        (field (name "COPYRIGHT") "Copyright (C) 2022 Ultra Librarian. All rights reserved.")
      )
      (libsource (lib "eagle-import") (part "TEKNIC_8PIN_MOTOR"))
    )
    (comp (ref "J27")
      (value "2-pos")
      (footprint "eagle-import:2_3.81MM_PITCH")
      (fields (field (name "PARTNO") "691322310002"))
      (libsource (lib "eagle-import") (part "3.81MM_1_X_2_RT_ANGLE_PLUG_HEADER"))
    )
    (comp (ref "J28")
      (value "2-pos")
      (footprint "eagle-import:2_3.81MM_PITCH")
      (fields (field (name "PARTNO") "691322310002"))
      (libsource (lib "eagle-import") (part "3.81MM_1_X_2_RT_ANGLE_PLUG_HEADER"))
    )
    (comp (ref "J29")
      (value "TEKNIC_8PIN_MOTOR")
      (footprint "eagle-import:CON_39281083")
      (fields
        (field (name "MANUFACTURER_PART_NUMBER") "39281083")
        (field (name "COPYRIGHT") "Copyright (C) 2022 Ultra Librarian. All rights reserved.")
      )
      (libsource (lib "eagle-import") (part "TEKNIC_8PIN_MOTOR"))
    )
    (comp (ref "J30")
      (value "TEKNIC_8PIN_MOTOR")
      (footprint "eagle-import:CON_39281083")
      (fields
        (field (name "MANUFACTURER_PART_NUMBER") "39281083")
        (field (name "COPYRIGHT") "Copyright (C) 2022 Ultra Librarian. All rights reserved.")
      )
      (libsource (lib "eagle-import") (part "TEKNIC_8PIN_MOTOR"))
    )
    (comp (ref "J31")
      (value "2-pos")
      (footprint "eagle-import:2_3.81MM_PITCH")
      (fields (field (name "PARTNO") "691322310002"))
      (libsource (lib "eagle-import") (part "3.81MM_1_X_2_RT_ANGLE_PLUG_HEADER"))
    )
    (comp (ref "J32")
      (value "2-pos")
      (footprint "eagle-import:2_3.81MM_PITCH")
      (fields (field (name "PARTNO") "691322310002"))
      (libsource (lib "eagle-import") (part "3.81MM_1_X_2_RT_ANGLE_PLUG_HEADER"))
    )
    (comp (ref "J33")
      (value "TEKNIC_8PIN_MOTOR")
      (footprint "eagle-import:CON_39281083")
      (fields
        (field (name "MANUFACTURER_PART_NUMBER") "39281083")
        (field (name "COPYRIGHT") "Copyright (C) 2022 Ultra Librarian. All rights reserved.")
      )
      (libsource (lib "eagle-import") (part "TEKNIC_8PIN_MOTOR"))
    )
    (comp (ref "J34")
      (value "TEKNIC_8PIN_MOTOR")
      (footprint "eagle-import:CON_39281083")
      (fields
        (field (name "MANUFACTURER_PART_NUMBER") "39281083")
        (field (name "COPYRIGHT") "Copyright (C) 2022 Ultra Librarian. All rights reserved.")
      )
      (libsource (lib "eagle-import") (part "TEKNIC_8PIN_MOTOR"))
    )
    (comp (ref "J35")
      (value "2-pos")
      (footprint "eagle-import:2_3.81MM_PITCH")
      (fields (field (name "PARTNO") "691322310002"))
      (libsource (lib "eagle-import") (part "3.81MM_1_X_2_RT_ANGLE_PLUG_HEADER"))
    )
    (comp (ref "J36")
      (value "2-pos")
      (footprint "eagle-import:2_3.81MM_PITCH")
      (fields (field (name "PARTNO") "691322310002"))
      (libsource (lib "eagle-import") (part "3.81MM_1_X_2_RT_ANGLE_PLUG_HEADER"))
    )
    (comp (ref "J37")
      (value "2-pos")
      (footprint "eagle-import:2_3.81MM_PITCH")
      (fields (field (name "PARTNO") "691322310002"))
      (libsource (lib "eagle-import") (part "3.81MM_1_X_2_RT_ANGLE_PLUG_HEADER"))
    )
    (comp (ref "J38")
      (value "2-pos")
      (footprint "eagle-import:2_3.81MM_PITCH")
      (fields (field (name "PARTNO") "691322310002"))
      (libsource (lib "eagle-import") (part "3.81MM_1_X_2_RT_ANGLE_PLUG_HEADER"))
    )
    (comp (ref "L1")
      (value "2.2uH")
      (footprint "eagle-import:1008")
      (fields (field (name "PARTNO") "LQM2HPN2R2MG0L"))
      (libsource (lib "eagle-import") (part "INDUCTOR_1008_2.2_MH_1.3A"))
    )
    (comp (ref "LED1")
      (value "Green")
      (footprint "eagle-import:0805")
      (fields (field (name "PARTNO") "LG R971-KN-1"))
      (libsource (lib "eagle-import") (part "LED_0805_GREEN"))
    )
    (comp (ref "LED4")
      (value "Green")
      (footprint "eagle-import:0805")
      (fields (field (name "PARTNO") "LG R971-KN-1"))
      (libsource (lib "eagle-import") (part "LED_0805_GREEN"))
    )
    (comp (ref "LED5")
      (value "Green")
      (footprint "eagle-import:0805")
      (fields (field (name "PARTNO") "LG R971-KN-1"))
      (libsource (lib "eagle-import") (part "LED_0805_GREEN"))
    )
    (comp (ref "LED8")
      (value "Green")
      (footprint "eagle-import:0805")
      (fields (field (name "PARTNO") "LG R971-KN-1"))
      (libsource (lib "eagle-import") (part "LED_0805_GREEN"))
    )
    (comp (ref "LED9")
      (value "Green")
      (footprint "eagle-import:0805")
      (fields (field (name "PARTNO") "LG R971-KN-1"))
      (libsource (lib "eagle-import") (part "LED_0805_GREEN"))
    )
    (comp (ref "R1")
      (value "6K49")
      (footprint "eagle-import:0402")
      (fields (field (name "PARTNO") "RMCF0402FT6K49"))
      (libsource (lib "eagle-import") (part "R_0402_6K49"))
    )
    (comp (ref "R2")
      (value "10K0")
      (footprint "eagle-import:0402")
      (fields (field (name "PARTNO") "RMCF0402JT10K0"))
      (libsource (lib "eagle-import") (part "R_0402_10K0"))
    )
    (comp (ref "R3")
      (value "10K0")
      (footprint "eagle-import:0402")
      (fields (field (name "PARTNO") "RMCF0402JT10K0"))
      (libsource (lib "eagle-import") (part "R_0402_10K0"))
    )
    (comp (ref "R4")
      (value "1K5")
      (footprint "eagle-import:0402")
      (fields (field (name "PARTNO") "RMCF0402JT1K50"))
      (libsource (lib "eagle-import") (part "R_0402_1K5"))
    )
    (comp (ref "R5")
      (value "470R0")
      (footprint "eagle-import:0402")
      (fields (field (name "PARTNO") "RMCF0402JT470R"))
      (libsource (lib "eagle-import") (part "R_0402_470R0"))
    )
    (comp (ref "R6")
      (value "1K5")
      (footprint "eagle-import:0402")
      (fields (field (name "PARTNO") "RMCF0402JT1K50"))
      (libsource (lib "eagle-import") (part "R_0402_1K5"))
    )
    (comp (ref "R7")
      (value "470R0")
      (footprint "eagle-import:0402")
      (fields (field (name "PARTNO") "RMCF0402JT470R"))
      (libsource (lib "eagle-import") (part "R_0402_470R0"))
    )
    (comp (ref "R8")
      (value "470R0")
      (footprint "eagle-import:0402")
      (fields (field (name "PARTNO") "RMCF0402JT470R"))
      (libsource (lib "eagle-import") (part "R_0402_470R0"))
    )
    (comp (ref "R9")
      (value "33R0")
      (footprint "eagle-import:0402")
      (fields (field (name "PARTNO") "RMCF0402JT33R0"))
      (libsource (lib "eagle-import") (part "R_0402_33R0"))
    )
    (comp (ref "R10")
      (value "33R0")
      (footprint "eagle-import:0402")
      (fields (field (name "PARTNO") "RMCF0402JT33R0"))
      (libsource (lib "eagle-import") (part "R_0402_33R0"))
    )
    (comp (ref "R11")
      (value "33R0")
      (footprint "eagle-import:0402")
      (fields (field (name "PARTNO") "RMCF0402JT33R0"))
      (libsource (lib "eagle-import") (part "R_0402_33R0"))
    )
    (comp (ref "R12")
      (value "33R0")
      (footprint "eagle-import:0402")
      (fields (field (name "PARTNO") "RMCF0402JT33R0"))
      (libsource (lib "eagle-import") (part "R_0402_33R0"))
    )
    (comp (ref "R13")
      (value "10K0")
      (footprint "eagle-import:0402")
      (fields (field (name "PARTNO") "RMCF0402JT10K0"))
      (libsource (lib "eagle-import") (part "R_0402_10K0"))
    )
    (comp (ref "R14")
      (value "1K0")
      (footprint "eagle-import:0402")
      (fields (field (name "PARTNO") "CRG0402J1K0"))
      (libsource (lib "eagle-import") (part "R_0402_1K0"))
    )
    (comp (ref "R15")
      (value "1K0")
      (footprint "eagle-import:0402")
      (fields (field (name "PARTNO") "CRG0402J1K0"))
      (libsource (lib "eagle-import") (part "R_0402_1K0"))
    )
    (comp (ref "R16")
      (value "15K0")
      (footprint "eagle-import:0402")
      (fields (field (name "PARTNO") "RMCF0402JT15K0"))
      (libsource (lib "eagle-import") (part "R_0402_15K0"))
    )
    (comp (ref "R17")
      (value "27R0")
      (footprint "eagle-import:0402")
      (fields (field (name "PARTNO") "RMCF0402JT27R0"))
      (libsource (lib "eagle-import") (part "R_0402_27R0"))
    )
    (comp (ref "R18")
      (value "27R0")
      (footprint "eagle-import:0402")
      (fields (field (name "PARTNO") "RMCF0402JT27R0"))
      (libsource (lib "eagle-import") (part "R_0402_27R0"))
    )
    (comp (ref "R19")
      (value "10K0")
      (footprint "eagle-import:0402")
      (fields (field (name "PARTNO") "RMCF0402JT10K0"))
      (libsource (lib "eagle-import") (part "R_0402_10K0"))
    )
    (comp (ref "R20")
      (value "10K0")
      (footprint "eagle-import:0402")
      (fields (field (name "PARTNO") "RMCF0402JT10K0"))
      (libsource (lib "eagle-import") (part "R_0402_10K0"))
    )
    (comp (ref "R21")
      (value "30K0")
      (footprint "eagle-import:0402")
      (fields (field (name "PARTNO") "RC0402JR-0730KL"))
      (libsource (lib "eagle-import") (part "R_0402_30K0"))
    )
    (comp (ref "R22")
      (value "2K2")
      (footprint "eagle-import:0402")
      (fields (field (name "PARTNO") "RMCF0402JT2K20"))
      (libsource (lib "eagle-import") (part "R_0402_2K2"))
    )
    (comp (ref "R23")
      (value "10K0")
      (footprint "eagle-import:0402")
      (fields (field (name "PARTNO") "RMCF0402JT10K0"))
      (libsource (lib "eagle-import") (part "R_0402_10K0"))
    )
    (comp (ref "R24")
      (value "10K0")
      (footprint "eagle-import:0402")
      (fields (field (name "PARTNO") "RMCF0402JT10K0"))
      (libsource (lib "eagle-import") (part "R_0402_10K0"))
    )
    (comp (ref "R29")
      (value "500R0")
      (footprint "eagle-import:0402")
      (libsource (lib "eagle-import") (part "R_0402"))
    )
    (comp (ref "R30")
      (value "500R0")
      (footprint "eagle-import:0402")
      (libsource (lib "eagle-import") (part "R_0402"))
    )
    (comp (ref "R31")
      (value "470R0")
      (footprint "eagle-import:0402")
      (fields (field (name "PARTNO") "RMCF0402JT470R"))
      (libsource (lib "eagle-import") (part "R_0402_470R0"))
    )
    (comp (ref "R32")
      (value "470R0")
      (footprint "eagle-import:0402")
      (fields (field (name "PARTNO") "RMCF0402JT470R"))
      (libsource (lib "eagle-import") (part "R_0402_470R0"))
    )
    (comp (ref "R37")
      (value "1k")
      (footprint "eagle-import:0805")
      (libsource (lib "eagle-import") (part "R_0805"))
    )
    (comp (ref "R38")
      (value "33")
      (footprint "eagle-import:0805")
      (libsource (lib "eagle-import") (part "R_0805"))
    )
    (comp (ref "R39")
      (value "33")
      (footprint "eagle-import:0805")
      (libsource (lib "eagle-import") (part "R_0805"))
    )
    (comp (ref "R40")
      (value "33")
      (footprint "eagle-import:0805")
      (libsource (lib "eagle-import") (part "R_0805"))
    )
    (comp (ref "R41")
      (value "1k")
      (footprint "eagle-import:0805")
      (libsource (lib "eagle-import") (part "R_0805"))
    )
    (comp (ref "R42")
      (value "1k")
      (footprint "eagle-import:0805")
      (libsource (lib "eagle-import") (part "R_0805"))
    )
    (comp (ref "R43")
      (value "1k")
      (footprint "eagle-import:0805")
      (libsource (lib "eagle-import") (part "R_0805"))
    )
    (comp (ref "R44")
      (value "33")
      (footprint "eagle-import:0805")
      (libsource (lib "eagle-import") (part "R_0805"))
    )
    (comp (ref "R45")
      (value "33")
      (footprint "eagle-import:0805")
      (libsource (lib "eagle-import") (part "R_0805"))
    )
    (comp (ref "R46")
      (value "33")
      (footprint "eagle-import:0805")
      (libsource (lib "eagle-import") (part "R_0805"))
    )
    (comp (ref "R47")
      (value "1k")
      (footprint "eagle-import:0805")
      (libsource (lib "eagle-import") (part "R_0805"))
    )
    (comp (ref "R48")
      (value "1k")
      (footprint "eagle-import:0805")
      (libsource (lib "eagle-import") (part "R_0805"))
    )
    (comp (ref "R49")
      (value "500R0")
      (footprint "eagle-import:0402")
      (libsource (lib "eagle-import") (part "R_0402"))
    )
    (comp (ref "R50")
      (value "500R0")
      (footprint "eagle-import:0402")
      (libsource (lib "eagle-import") (part "R_0402"))
    )
    (comp (ref "R51")
      (value "470R0")
      (footprint "eagle-import:0402")
      (fields (field (name "PARTNO") "RMCF0402JT470R"))
      (libsource (lib "eagle-import") (part "R_0402_470R0"))
    )
    (comp (ref "R52")
      (value "470R0")
      (footprint "eagle-import:0402")
      (fields (field (name "PARTNO") "RMCF0402JT470R"))
      (libsource (lib "eagle-import") (part "R_0402_470R0"))
    )
    (comp (ref "R61")
      (value "1k")
      (footprint "eagle-import:0805")
      (libsource (lib "eagle-import") (part "R_0805"))
    )
    (comp (ref "R62")
      (value "33")
      (footprint "eagle-import:0805")
      (libsource (lib "eagle-import") (part "R_0805"))
    )
    (comp (ref "R63")
      (value "33")
      (footprint "eagle-import:0805")
      (libsource (lib "eagle-import") (part "R_0805"))
    )
    (comp (ref "R64")
      (value "33")
      (footprint "eagle-import:0805")
      (libsource (lib "eagle-import") (part "R_0805"))
    )
    (comp (ref "R65")
      (value "1k")
      (footprint "eagle-import:0805")
      (libsource (lib "eagle-import") (part "R_0805"))
    )
    (comp (ref "R66")
      (value "1k")
      (footprint "eagle-import:0805")
      (libsource (lib "eagle-import") (part "R_0805"))
    )
    (comp (ref "R67")
      (value "1k")
      (footprint "eagle-import:0805")
      (libsource (lib "eagle-import") (part "R_0805"))
    )
    (comp (ref "R68")
      (value "33")
      (footprint "eagle-import:0805")
      (libsource (lib "eagle-import") (part "R_0805"))
    )
    (comp (ref "R69")
      (value "33")
      (footprint "eagle-import:0805")
      (libsource (lib "eagle-import") (part "R_0805"))
    )
    (comp (ref "R70")
      (value "33")
      (footprint "eagle-import:0805")
      (libsource (lib "eagle-import") (part "R_0805"))
    )
    (comp (ref "R71")
      (value "1k")
      (footprint "eagle-import:0805")
      (libsource (lib "eagle-import") (part "R_0805"))
    )
    (comp (ref "R72")
      (value "1k")
      (footprint "eagle-import:0805")
      (libsource (lib "eagle-import") (part "R_0805"))
    )
    (comp (ref "R85")
      (value "1k")
      (footprint "eagle-import:0805")
      (libsource (lib "eagle-import") (part "R_0805"))
    )
    (comp (ref "R86")
      (value "33")
      (footprint "eagle-import:0805")
      (libsource (lib "eagle-import") (part "R_0805"))
    )
    (comp (ref "R87")
      (value "33")
      (footprint "eagle-import:0805")
      (libsource (lib "eagle-import") (part "R_0805"))
    )
    (comp (ref "R88")
      (value "33")
      (footprint "eagle-import:0805")
      (libsource (lib "eagle-import") (part "R_0805"))
    )
    (comp (ref "R89")
      (value "1k")
      (footprint "eagle-import:0805")
      (libsource (lib "eagle-import") (part "R_0805"))
    )
    (comp (ref "R90")
      (value "1k")
      (footprint "eagle-import:0805")
      (libsource (lib "eagle-import") (part "R_0805"))
    )
    (comp (ref "R91")
      (value "1k")
      (footprint "eagle-import:0805")
      (libsource (lib "eagle-import") (part "R_0805"))
    )
    (comp (ref "R92")
      (value "33")
      (footprint "eagle-import:0805")
      (libsource (lib "eagle-import") (part "R_0805"))
    )
    (comp (ref "R93")
      (value "33")
      (footprint "eagle-import:0805")
      (libsource (lib "eagle-import") (part "R_0805"))
    )
    (comp (ref "R94")
      (value "33")
      (footprint "eagle-import:0805")
      (libsource (lib "eagle-import") (part "R_0805"))
    )
    (comp (ref "R95")
      (value "1k")
      (footprint "eagle-import:0805")
      (libsource (lib "eagle-import") (part "R_0805"))
    )
    (comp (ref "R96")
      (value "1k")
      (footprint "eagle-import:0805")
      (libsource (lib "eagle-import") (part "R_0805"))
    )
    (comp (ref "R109")
      (value "1k")
      (footprint "eagle-import:0805")
      (libsource (lib "eagle-import") (part "R_0805"))
    )
    (comp (ref "R110")
      (value "33")
      (footprint "eagle-import:0805")
      (libsource (lib "eagle-import") (part "R_0805"))
    )
    (comp (ref "R111")
      (value "33")
      (footprint "eagle-import:0805")
      (libsource (lib "eagle-import") (part "R_0805"))
    )
    (comp (ref "R112")
      (value "33")
      (footprint "eagle-import:0805")
      (libsource (lib "eagle-import") (part "R_0805"))
    )
    (comp (ref "R113")
      (value "1k")
      (footprint "eagle-import:0805")
      (libsource (lib "eagle-import") (part "R_0805"))
    )
    (comp (ref "R114")
      (value "1k")
      (footprint "eagle-import:0805")
      (libsource (lib "eagle-import") (part "R_0805"))
    )
    (comp (ref "R115")
      (value "1k")
      (footprint "eagle-import:0805")
      (libsource (lib "eagle-import") (part "R_0805"))
    )
    (comp (ref "R116")
      (value "33")
      (footprint "eagle-import:0805")
      (libsource (lib "eagle-import") (part "R_0805"))
    )
    (comp (ref "R117")
      (value "33")
      (footprint "eagle-import:0805")
      (libsource (lib "eagle-import") (part "R_0805"))
    )
    (comp (ref "R118")
      (value "33")
      (footprint "eagle-import:0805")
      (libsource (lib "eagle-import") (part "R_0805"))
    )
    (comp (ref "R119")
      (value "1k")
      (footprint "eagle-import:0805")
      (libsource (lib "eagle-import") (part "R_0805"))
    )
    (comp (ref "R120")
      (value "1k")
      (footprint "eagle-import:0805")
      (libsource (lib "eagle-import") (part "R_0805"))
    )
    (comp (ref "R133")
      (value "1k")
      (footprint "eagle-import:0805")
      (libsource (lib "eagle-import") (part "R_0805"))
    )
    (comp (ref "R134")
      (value "33")
      (footprint "eagle-import:0805")
      (libsource (lib "eagle-import") (part "R_0805"))
    )
    (comp (ref "R135")
      (value "33")
      (footprint "eagle-import:0805")
      (libsource (lib "eagle-import") (part "R_0805"))
    )
    (comp (ref "R136")
      (value "33")
      (footprint "eagle-import:0805")
      (libsource (lib "eagle-import") (part "R_0805"))
    )
    (comp (ref "R137")
      (value "1k")
      (footprint "eagle-import:0805")
      (libsource (lib "eagle-import") (part "R_0805"))
    )
    (comp (ref "R138")
      (value "1k")
      (footprint "eagle-import:0805")
      (libsource (lib "eagle-import") (part "R_0805"))
    )
    (comp (ref "R139")
      (value "1k")
      (footprint "eagle-import:0805")
      (libsource (lib "eagle-import") (part "R_0805"))
    )
    (comp (ref "R140")
      (value "33")
      (footprint "eagle-import:0805")
      (libsource (lib "eagle-import") (part "R_0805"))
    )
    (comp (ref "R141")
      (value "33")
      (footprint "eagle-import:0805")
      (libsource (lib "eagle-import") (part "R_0805"))
    )
    (comp (ref "R142")
      (value "33")
      (footprint "eagle-import:0805")
      (libsource (lib "eagle-import") (part "R_0805"))
    )
    (comp (ref "R143")
      (value "1k")
      (footprint "eagle-import:0805")
      (libsource (lib "eagle-import") (part "R_0805"))
    )
    (comp (ref "R144")
      (value "1k")
      (footprint "eagle-import:0805")
      (libsource (lib "eagle-import") (part "R_0805"))
    )
    (comp (ref "R157")
      (value "1k")
      (footprint "eagle-import:0805")
      (libsource (lib "eagle-import") (part "R_0805"))
    )
    (comp (ref "R158")
      (value "33")
      (footprint "eagle-import:0805")
      (libsource (lib "eagle-import") (part "R_0805"))
    )
    (comp (ref "R159")
      (value "33")
      (footprint "eagle-import:0805")
      (libsource (lib "eagle-import") (part "R_0805"))
    )
    (comp (ref "R160")
      (value "33")
      (footprint "eagle-import:0805")
      (libsource (lib "eagle-import") (part "R_0805"))
    )
    (comp (ref "R161")
      (value "1k")
      (footprint "eagle-import:0805")
      (libsource (lib "eagle-import") (part "R_0805"))
    )
    (comp (ref "R162")
      (value "1k")
      (footprint "eagle-import:0805")
      (libsource (lib "eagle-import") (part "R_0805"))
    )
    (comp (ref "R163")
      (value "1k")
      (footprint "eagle-import:0805")
      (libsource (lib "eagle-import") (part "R_0805"))
    )
    (comp (ref "R164")
      (value "33")
      (footprint "eagle-import:0805")
      (libsource (lib "eagle-import") (part "R_0805"))
    )
    (comp (ref "R165")
      (value "33")
      (footprint "eagle-import:0805")
      (libsource (lib "eagle-import") (part "R_0805"))
    )
    (comp (ref "R166")
      (value "33")
      (footprint "eagle-import:0805")
      (libsource (lib "eagle-import") (part "R_0805"))
    )
    (comp (ref "R167")
      (value "1k")
      (footprint "eagle-import:0805")
      (libsource (lib "eagle-import") (part "R_0805"))
    )
    (comp (ref "R168")
      (value "1k")
      (footprint "eagle-import:0805")
      (libsource (lib "eagle-import") (part "R_0805"))
    )
    (comp (ref "RJ1")
      (value "RJ45")
      (footprint "eagle-import:RJ45_TH_ELEC")
      (fields (field (name "PARTNO") "13F-64GYD2PL2NL"))
      (libsource (lib "eagle-import") (part "RJ45_WITH_ELEC"))
    )
    (comp (ref "U$1")
      (value "RELAY_KYOTO_KF0604D")
      (footprint "eagle-import:RELAY_KYOTO_KF0604D")
      (libsource (lib "eagle-import") (part "RELAY_KYOTO_KF0604D"))
    )
    (comp (ref "U$2")
      (value "RELAY_KYOTO_KF0604D")
      (footprint "eagle-import:RELAY_KYOTO_KF0604D")
      (libsource (lib "eagle-import") (part "RELAY_KYOTO_KF0604D"))
    )
    (comp (ref "U$7")
      (value "RELAY_KYOTO_KF0604D")
      (footprint "eagle-import:RELAY_KYOTO_KF0604D")
      (libsource (lib "eagle-import") (part "RELAY_KYOTO_KF0604D"))
    )
    (comp (ref "U$8")
      (value "RELAY_KYOTO_KF0604D")
      (footprint "eagle-import:RELAY_KYOTO_KF0604D")
      (libsource (lib "eagle-import") (part "RELAY_KYOTO_KF0604D"))
    )
    (comp (ref "U1")
      (value "KSZ8081_QFN_24")
      (footprint "eagle-import:QFN-24-M")
      (fields (field (name "PARTNO") "KSZ8081RNACA"))
      (libsource (lib "eagle-import") (part "KSZ8081RNACAQFN-24-M"))
    )
    (comp (ref "U2")
      (value "AP2151DWG-7")
      (footprint "eagle-import:SOT-23-5")
      (fields (field (name "PARTNO") "AP2151WG-7"))
      (libsource (lib "eagle-import") (part "AP2151DWG-7"))
    )
    (comp (ref "U3")
      (value "S7G2LQFP176")
      (footprint "eagle-import:LQFP176_24X24")
      (fields (field (name "PARTNO") "R7FS7G27H3A01CFC#AA0"))
      (libsource (lib "eagle-import") (part "RENESAS_S7G2_X_176"))
    )
    (comp (ref "U6")
      (value "NPN")
      (footprint "eagle-import:SOT323")
      (fields (field (name "PARTNO") "BC846BW_NPN"))
      (libsource (lib "eagle-import") (part "BC846BW"))
    )
    (comp (ref "U7")
      (value "NPN")
      (footprint "eagle-import:SOT323")
      (fields (field (name "PARTNO") "BC846BW_NPN"))
      (libsource (lib "eagle-import") (part "BC846BW"))
    )
    (comp (ref "U10")
      (value "NPN")
      (footprint "eagle-import:SOT323")
      (fields (field (name "PARTNO") "BC846BW_NPN"))
      (libsource (lib "eagle-import") (part "BC846BW"))
    )
    (comp (ref "U11")
      (value "NPN")
      (footprint "eagle-import:SOT323")
      (fields (field (name "PARTNO") "BC846BW_NPN"))
      (libsource (lib "eagle-import") (part "BC846BW"))
    )
    (comp (ref "U12")
      (value "NPN")
      (footprint "eagle-import:SOT323")
      (fields (field (name "PARTNO") "BC846BW_NPN"))
      (libsource (lib "eagle-import") (part "BC846BW"))
    )
    (comp (ref "U13")
      (value "NPN")
      (footprint "eagle-import:SOT323")
      (fields (field (name "PARTNO") "BC846BW_NPN"))
      (libsource (lib "eagle-import") (part "BC846BW"))
    )
    (comp (ref "U14")
      (value "NPN")
      (footprint "eagle-import:SOT323")
      (fields (field (name "PARTNO") "BC846BW_NPN"))
      (libsource (lib "eagle-import") (part "BC846BW"))
    )
    (comp (ref "U15")
      (value "NPN")
      (footprint "eagle-import:SOT323")
      (fields (field (name "PARTNO") "BC846BW_NPN"))
      (libsource (lib "eagle-import") (part "BC846BW"))
    )
    (comp (ref "U16")
      (value "NPN")
      (footprint "eagle-import:SOT323")
      (fields (field (name "PARTNO") "BC846BW_NPN"))
      (libsource (lib "eagle-import") (part "BC846BW"))
    )
    (comp (ref "U17")
      (value "NPN")
      (footprint "eagle-import:SOT323")
      (fields (field (name "PARTNO") "BC846BW_NPN"))
      (libsource (lib "eagle-import") (part "BC846BW"))
    )
    (comp (ref "U22")
      (value "NPN")
      (footprint "eagle-import:SOT323")
      (fields (field (name "PARTNO") "BC846BW_NPN"))
      (libsource (lib "eagle-import") (part "BC846BW"))
    )
    (comp (ref "U23")
      (value "NPN")
      (footprint "eagle-import:SOT323")
      (fields (field (name "PARTNO") "BC846BW_NPN"))
      (libsource (lib "eagle-import") (part "BC846BW"))
    )
    (comp (ref "U24")
      (value "NPN")
      (footprint "eagle-import:SOT323")
      (fields (field (name "PARTNO") "BC846BW_NPN"))
      (libsource (lib "eagle-import") (part "BC846BW"))
    )
    (comp (ref "U25")
      (value "NPN")
      (footprint "eagle-import:SOT323")
      (fields (field (name "PARTNO") "BC846BW_NPN"))
      (libsource (lib "eagle-import") (part "BC846BW"))
    )
    (comp (ref "U26")
      (value "NPN")
      (footprint "eagle-import:SOT323")
      (fields (field (name "PARTNO") "BC846BW_NPN"))
      (libsource (lib "eagle-import") (part "BC846BW"))
    )
    (comp (ref "U27")
      (value "NPN")
      (footprint "eagle-import:SOT323")
      (fields (field (name "PARTNO") "BC846BW_NPN"))
      (libsource (lib "eagle-import") (part "BC846BW"))
    )
    (comp (ref "U34")
      (value "NPN")
      (footprint "eagle-import:SOT323")
      (fields (field (name "PARTNO") "BC846BW_NPN"))
      (libsource (lib "eagle-import") (part "BC846BW"))
    )
    (comp (ref "U35")
      (value "NPN")
      (footprint "eagle-import:SOT323")
      (fields (field (name "PARTNO") "BC846BW_NPN"))
      (libsource (lib "eagle-import") (part "BC846BW"))
    )
    (comp (ref "U36")
      (value "NPN")
      (footprint "eagle-import:SOT323")
      (fields (field (name "PARTNO") "BC846BW_NPN"))
      (libsource (lib "eagle-import") (part "BC846BW"))
    )
    (comp (ref "U37")
      (value "NPN")
      (footprint "eagle-import:SOT323")
      (fields (field (name "PARTNO") "BC846BW_NPN"))
      (libsource (lib "eagle-import") (part "BC846BW"))
    )
    (comp (ref "U38")
      (value "NPN")
      (footprint "eagle-import:SOT323")
      (fields (field (name "PARTNO") "BC846BW_NPN"))
      (libsource (lib "eagle-import") (part "BC846BW"))
    )
    (comp (ref "U39")
      (value "NPN")
      (footprint "eagle-import:SOT323")
      (fields (field (name "PARTNO") "BC846BW_NPN"))
      (libsource (lib "eagle-import") (part "BC846BW"))
    )
    (comp (ref "U46")
      (value "NPN")
      (footprint "eagle-import:SOT323")
      (fields (field (name "PARTNO") "BC846BW_NPN"))
      (libsource (lib "eagle-import") (part "BC846BW"))
    )
    (comp (ref "U47")
      (value "NPN")
      (footprint "eagle-import:SOT323")
      (fields (field (name "PARTNO") "BC846BW_NPN"))
      (libsource (lib "eagle-import") (part "BC846BW"))
    )
    (comp (ref "U48")
      (value "NPN")
      (footprint "eagle-import:SOT323")
      (fields (field (name "PARTNO") "BC846BW_NPN"))
      (libsource (lib "eagle-import") (part "BC846BW"))
    )
    (comp (ref "U49")
      (value "NPN")
      (footprint "eagle-import:SOT323")
      (fields (field (name "PARTNO") "BC846BW_NPN"))
      (libsource (lib "eagle-import") (part "BC846BW"))
    )
    (comp (ref "U50")
      (value "NPN")
      (footprint "eagle-import:SOT323")
      (fields (field (name "PARTNO") "BC846BW_NPN"))
      (libsource (lib "eagle-import") (part "BC846BW"))
    )
    (comp (ref "U51")
      (value "NPN")
      (footprint "eagle-import:SOT323")
      (fields (field (name "PARTNO") "BC846BW_NPN"))
      (libsource (lib "eagle-import") (part "BC846BW"))
    )
    (comp (ref "U58")
      (value "NPN")
      (footprint "eagle-import:SOT323")
      (fields (field (name "PARTNO") "BC846BW_NPN"))
      (libsource (lib "eagle-import") (part "BC846BW"))
    )
    (comp (ref "U59")
      (value "NPN")
      (footprint "eagle-import:SOT323")
      (fields (field (name "PARTNO") "BC846BW_NPN"))
      (libsource (lib "eagle-import") (part "BC846BW"))
    )
    (comp (ref "U60")
      (value "NPN")
      (footprint "eagle-import:SOT323")
      (fields (field (name "PARTNO") "BC846BW_NPN"))
      (libsource (lib "eagle-import") (part "BC846BW"))
    )
    (comp (ref "U61")
      (value "NPN")
      (footprint "eagle-import:SOT323")
      (fields (field (name "PARTNO") "BC846BW_NPN"))
      (libsource (lib "eagle-import") (part "BC846BW"))
    )
    (comp (ref "U62")
      (value "NPN")
      (footprint "eagle-import:SOT323")
      (fields (field (name "PARTNO") "BC846BW_NPN"))
      (libsource (lib "eagle-import") (part "BC846BW"))
    )
    (comp (ref "U63")
      (value "NPN")
      (footprint "eagle-import:SOT323")
      (fields (field (name "PARTNO") "BC846BW_NPN"))
      (libsource (lib "eagle-import") (part "BC846BW"))
    )
    (comp (ref "U70")
      (value "NPN")
      (footprint "eagle-import:SOT323")
      (fields (field (name "PARTNO") "BC846BW_NPN"))
      (libsource (lib "eagle-import") (part "BC846BW"))
    )
    (comp (ref "U71")
      (value "NPN")
      (footprint "eagle-import:SOT323")
      (fields (field (name "PARTNO") "BC846BW_NPN"))
      (libsource (lib "eagle-import") (part "BC846BW"))
    )
    (comp (ref "U72")
      (value "NPN")
      (footprint "eagle-import:SOT323")
      (fields (field (name "PARTNO") "BC846BW_NPN"))
      (libsource (lib "eagle-import") (part "BC846BW"))
    )
    (comp (ref "U73")
      (value "NPN")
      (footprint "eagle-import:SOT323")
      (fields (field (name "PARTNO") "BC846BW_NPN"))
      (libsource (lib "eagle-import") (part "BC846BW"))
    )
    (comp (ref "U74")
      (value "NPN")
      (footprint "eagle-import:SOT323")
      (fields (field (name "PARTNO") "BC846BW_NPN"))
      (libsource (lib "eagle-import") (part "BC846BW"))
    )
    (comp (ref "U75")
      (value "NPN")
      (footprint "eagle-import:SOT323")
      (fields (field (name "PARTNO") "BC846BW_NPN"))
      (libsource (lib "eagle-import") (part "BC846BW"))
    )
    (comp (ref "X1")
      (value "25MHz")
      (footprint "eagle-import:SMD_3225")
      (fields (field (name "PARTNO") "FA-238 25.0000MB-B3"))
      (libsource (lib "eagle-import") (part "XTAL_25_MHZ"))
    )
    (comp (ref "X2")
      (value "24MHz")
      (footprint "eagle-import:SMD_3225")
      (fields (field (name "PARTNO") "FA-238 24.0000MB-C3 "))
      (libsource (lib "eagle-import") (part "XTAL_24_MHZ"))
    )
    (comp (ref "X3")
      (value "32.768KHz")
      (footprint "eagle-import:SMD_X_2_PADS")
      (fields (field (name "PARTNO") "ABS07-32.768KHZ-T"))
      (libsource (lib "eagle-import") (part "XTAL_32.768KHZ"))
    )
  )
  (nets
    (net (code "1") (name "A_A_DIR") (class "Default")
      (node (ref "R111") (pin "1") (pinfunction "1_1") (pintype "passive"))
      (node (ref "U3") (pin "75") (pinfunction "P3_11_75") (pintype "bidirectional"))
    )
    (net (code "2") (name "A_A_ENABLE") (class "Default")
      (node (ref "R112") (pin "1") (pinfunction "1_1") (pintype "passive"))
      (node (ref "U3") (pin "74") (pinfunction "P3_12_74") (pintype "bidirectional"))
    )
    (net (code "3") (name "A_A_HLFB_OUT") (class "Default")
      (node (ref "J25") (pin "5") (pinfunction "5-HLFB-_5") (pintype "passive"))
      (node (ref "U3") (pin "77") (pinfunction "P3_9_77") (pintype "bidirectional"))
    )
    (net (code "4") (name "A_A_MI_DIR") (class "Default")
      (node (ref "J25") (pin "7") (pinfunction "7-INPUT_A-_7") (pintype "passive"))
      (node (ref "R113") (pin "1") (pinfunction "1_1") (pintype "passive"))
      (node (ref "U47") (pin "3") (pinfunction "C(3)_3") (pintype "input"))
    )
    (net (code "5") (name "A_A_MI_ENABLE") (class "Default")
      (node (ref "J25") (pin "8") (pinfunction "8-ENABLE-_8") (pintype "passive"))
      (node (ref "R114") (pin "1") (pinfunction "1_1") (pintype "passive"))
      (node (ref "U48") (pin "3") (pinfunction "C(3)_3") (pintype "input"))
    )
    (net (code "6") (name "A_A_MI_STEP") (class "Default")
      (node (ref "J25") (pin "6") (pinfunction "6-INPUT_B-_6") (pintype "passive"))
      (node (ref "R109") (pin "1") (pinfunction "1_1") (pintype "passive"))
      (node (ref "U46") (pin "3") (pinfunction "C(3)_3") (pintype "input"))
    )
    (net (code "7") (name "A_A_STEP") (class "Default")
      (node (ref "R110") (pin "1") (pinfunction "1_1") (pintype "passive"))
      (node (ref "U3") (pin "76") (pinfunction "P3_10_76") (pintype "bidirectional"))
    )
    (net (code "8") (name "A_B_DIR") (class "Default")
      (node (ref "R117") (pin "1") (pinfunction "1_1") (pintype "passive"))
      (node (ref "U3") (pin "80") (pinfunction "P3_6_80") (pintype "bidirectional"))
    )
    (net (code "9") (name "A_B_ENABLE") (class "Default")
      (node (ref "R118") (pin "1") (pinfunction "1_1") (pintype "passive"))
      (node (ref "U3") (pin "79") (pinfunction "P3_7_79") (pintype "bidirectional"))
    )
    (net (code "10") (name "A_B_HLFB_OUT") (class "Default")
      (node (ref "J26") (pin "5") (pinfunction "5-HLFB-_5") (pintype "passive"))
      (node (ref "U3") (pin "82") (pinfunction "P3_4_82") (pintype "bidirectional"))
    )
    (net (code "11") (name "A_B_MI_DIR") (class "Default")
      (node (ref "J26") (pin "7") (pinfunction "7-INPUT_A-_7") (pintype "passive"))
      (node (ref "R119") (pin "1") (pinfunction "1_1") (pintype "passive"))
      (node (ref "U50") (pin "3") (pinfunction "C(3)_3") (pintype "input"))
    )
    (net (code "12") (name "A_B_MI_ENABLE") (class "Default")
      (node (ref "J26") (pin "8") (pinfunction "8-ENABLE-_8") (pintype "passive"))
      (node (ref "R120") (pin "1") (pinfunction "1_1") (pintype "passive"))
      (node (ref "U51") (pin "3") (pinfunction "C(3)_3") (pintype "input"))
    )
    (net (code "13") (name "A_B_MI_STEP") (class "Default")
      (node (ref "J26") (pin "6") (pinfunction "6-INPUT_B-_6") (pintype "passive"))
      (node (ref "R115") (pin "1") (pinfunction "1_1") (pintype "passive"))
      (node (ref "U49") (pin "3") (pinfunction "C(3)_3") (pintype "input"))
    )
    (net (code "14") (name "A_B_STEP") (class "Default")
      (node (ref "R116") (pin "1") (pinfunction "1_1") (pintype "passive"))
      (node (ref "U3") (pin "81") (pinfunction "P3_5_81") (pintype "bidirectional"))
    )
    (net (code "15") (name "B_MI_DIR") (class "Default")
      (node (ref "J34") (pin "7") (pinfunction "7-INPUT_A-_7") (pintype "passive"))
      (node (ref "R167") (pin "1") (pinfunction "1_1") (pintype "passive"))
      (node (ref "U74") (pin "3") (pinfunction "C(3)_3") (pintype "input"))
    )
    (net (code "16") (name "C58") (class "Default")
      (node (ref "C12") (pin "P$1") (pinfunction "1_P$1") (pintype "passive"))
      (node (ref "RJ1") (pin "4") (pinfunction "CT1_4") (pintype "bidirectional"))
    )
    (net (code "17") (name "C60") (class "Default")
      (node (ref "C13") (pin "P$1") (pinfunction "1_P$1") (pintype "passive"))
      (node (ref "RJ1") (pin "5") (pinfunction "CT2_5") (pintype "bidirectional"))
    )
    (net (code "18") (name "CRS_DV") (class "Default")
      (node (ref "R12") (pin "P$2") (pinfunction "2_P$2") (pintype "passive"))
      (node (ref "U1") (pin "15") (pinfunction "CRS_DV/PHYAD[1:0]_15") (pintype "bidirectional"))
    )
    (net (code "19") (name "C_A_DIR") (class "Default")
      (node (ref "R135") (pin "1") (pinfunction "1_1") (pintype "passive"))
      (node (ref "U3") (pin "58") (pinfunction "P9_0_58") (pintype "bidirectional"))
    )
    (net (code "20") (name "C_A_ENABLE") (class "Default")
      (node (ref "R136") (pin "1") (pinfunction "1_1") (pintype "passive"))
      (node (ref "U3") (pin "57") (pinfunction "P3_15_57") (pintype "bidirectional"))
    )
    (net (code "21") (name "C_A_HLFB_OUT") (class "Default")
      (node (ref "J29") (pin "5") (pinfunction "5-HLFB-_5") (pintype "passive"))
      (node (ref "U3") (pin "68") (pinfunction "P2_1/MD_68") (pintype "bidirectional"))
    )
    (net (code "22") (name "C_A_MI_DIR") (class "Default")
      (node (ref "J29") (pin "7") (pinfunction "7-INPUT_A-_7") (pintype "passive"))
      (node (ref "R137") (pin "1") (pinfunction "1_1") (pintype "passive"))
      (node (ref "U59") (pin "3") (pinfunction "C(3)_3") (pintype "input"))
    )
    (net (code "23") (name "C_A_MI_ENABLE") (class "Default")
      (node (ref "J29") (pin "8") (pinfunction "8-ENABLE-_8") (pintype "passive"))
      (node (ref "R138") (pin "1") (pinfunction "1_1") (pintype "passive"))
      (node (ref "U60") (pin "3") (pinfunction "C(3)_3") (pintype "input"))
    )
    (net (code "24") (name "C_A_MI_STEP") (class "Default")
      (node (ref "J29") (pin "6") (pinfunction "6-INPUT_B-_6") (pintype "passive"))
      (node (ref "R133") (pin "1") (pinfunction "1_1") (pintype "passive"))
      (node (ref "U58") (pin "3") (pinfunction "C(3)_3") (pintype "input"))
    )
    (net (code "25") (name "C_A_STEP") (class "Default")
      (node (ref "R134") (pin "1") (pinfunction "1_1") (pintype "passive"))
      (node (ref "U3") (pin "59") (pinfunction "P9_1_59") (pintype "bidirectional"))
    )
    (net (code "26") (name "C_B_DIR") (class "Default")
      (node (ref "R141") (pin "1") (pinfunction "1_1") (pintype "passive"))
      (node (ref "U3") (pin "71") (pinfunction "P9_7_71") (pintype "bidirectional"))
    )
    (net (code "27") (name "C_B_ENABLE") (class "Default")
      (node (ref "R142") (pin "1") (pinfunction "1_1") (pintype "passive"))
      (node (ref "U3") (pin "70") (pinfunction "P9_8_70") (pintype "bidirectional"))
    )
    (net (code "28") (name "C_B_HLFB_OUT") (class "Default")
      (node (ref "J30") (pin "5") (pinfunction "5-HLFB-_5") (pintype "passive"))
      (node (ref "U3") (pin "73") (pinfunction "P9_5_73") (pintype "bidirectional"))
    )
    (net (code "29") (name "C_B_MI_DIR") (class "Default")
      (node (ref "J30") (pin "7") (pinfunction "7-INPUT_A-_7") (pintype "passive"))
      (node (ref "R143") (pin "1") (pinfunction "1_1") (pintype "passive"))
      (node (ref "U62") (pin "3") (pinfunction "C(3)_3") (pintype "input"))
    )
    (net (code "30") (name "C_B_MI_ENABLE") (class "Default")
      (node (ref "J30") (pin "8") (pinfunction "8-ENABLE-_8") (pintype "passive"))
      (node (ref "R144") (pin "1") (pinfunction "1_1") (pintype "passive"))
      (node (ref "U63") (pin "3") (pinfunction "C(3)_3") (pintype "input"))
    )
    (net (code "31") (name "C_B_MI_STEP") (class "Default")
      (node (ref "J30") (pin "6") (pinfunction "6-INPUT_B-_6") (pintype "passive"))
      (node (ref "R139") (pin "1") (pinfunction "1_1") (pintype "passive"))
      (node (ref "U61") (pin "3") (pinfunction "C(3)_3") (pintype "input"))
    )
    (net (code "32") (name "C_B_STEP") (class "Default")
      (node (ref "R140") (pin "1") (pinfunction "1_1") (pintype "passive"))
      (node (ref "U3") (pin "72") (pinfunction "P9_6_72") (pintype "bidirectional"))
    )
    (net (code "33") (name "ESTOP") (class "Default")
      (node (ref "J9") (pin "P$1") (pinfunction "P$1_P$1") (pintype "bidirectional"))
      (node (ref "U3") (pin "69") (pinfunction "P2_0(INPUT_ONLY)_69") (pintype "bidirectional"))
    )
    (net (code "34") (name "ETH") (class "Default")
      (node (ref "U1") (pin "16") (pinfunction "REF_CLK_16") (pintype "bidirectional"))
      (node (ref "U3") (pin "9") (pinfunction "P7_1_9") (pintype "bidirectional"))
    )
    (net (code "35") (name "ETH_CRS_DV") (class "Default")
      (node (ref "R12") (pin "P$1") (pinfunction "1_P$1") (pintype "passive"))
      (node (ref "U3") (pin "13") (pinfunction "P7_5_13") (pintype "bidirectional"))
    )
    (net (code "36") (name "ETH_IRQ14") (class "Default")
      (node (ref "R2") (pin "P$1") (pinfunction "1_P$1") (pintype "passive"))
      (node (ref "U1") (pin "18") (pinfunction "INTRP_18") (pintype "bidirectional"))
      (node (ref "U3") (pin "159") (pinfunction "P0_10/AN103_159") (pintype "bidirectional"))
    )
    (net (code "37") (name "ETH_MDC") (class "Default")
      (node (ref "R4") (pin "P$1") (pinfunction "1_P$1") (pintype "passive"))
      (node (ref "U1") (pin "11") (pinfunction "MDC_11") (pintype "input"))
      (node (ref "U3") (pin "4") (pinfunction "P4_3_4") (pintype "bidirectional"))
    )
    (net (code "38") (name "ETH_MDIO") (class "Default")
      (node (ref "R6") (pin "P$1") (pinfunction "1_P$1") (pintype "passive"))
      (node (ref "U1") (pin "10") (pinfunction "MDIO_10") (pintype "bidirectional"))
      (node (ref "U3") (pin "5") (pinfunction "P4_4_5") (pintype "bidirectional"))
    )
    (net (code "39") (name "ETH_RESET") (class "Default")
      (node (ref "C6") (pin "P$1") (pinfunction "1_P$1") (pintype "passive"))
      (node (ref "R3") (pin "P$1") (pinfunction "1_P$1") (pintype "passive"))
      (node (ref "U1") (pin "24") (pinfunction "~{RST}_24") (pintype "input"))
      (node (ref "U3") (pin "172") (pinfunction "P8_6_172") (pintype "bidirectional"))
    )
    (net (code "40") (name "ETH_RXD0") (class "Default")
      (node (ref "R10") (pin "P$1") (pinfunction "1_P$1") (pintype "passive"))
      (node (ref "U3") (pin "10") (pinfunction "P7_2_10") (pintype "bidirectional"))
    )
    (net (code "41") (name "ETH_RXD1") (class "Default")
      (node (ref "R9") (pin "P$1") (pinfunction "1_P$1") (pintype "passive"))
      (node (ref "U3") (pin "11") (pinfunction "P7_3_11") (pintype "bidirectional"))
    )
    (net (code "42") (name "ETH_RX_ER") (class "Default")
      (node (ref "R11") (pin "P$1") (pinfunction "1_P$1") (pintype "passive"))
      (node (ref "U3") (pin "12") (pinfunction "P7_4_12") (pintype "bidirectional"))
    )
    (net (code "43") (name "ETH_TXD0") (class "Default")
      (node (ref "U1") (pin "20") (pinfunction "TXD0_20") (pintype "input"))
      (node (ref "U3") (pin "8") (pinfunction "P7_0_8") (pintype "bidirectional"))
    )
    (net (code "44") (name "ETH_TXD1") (class "Default")
      (node (ref "U1") (pin "21") (pinfunction "TXD1_21") (pintype "bidirectional"))
      (node (ref "U3") (pin "7") (pinfunction "P4_6_7") (pintype "bidirectional"))
    )
    (net (code "45") (name "ETH_TXD_EN") (class "Default")
      (node (ref "U1") (pin "19") (pinfunction "TXEN_19") (pintype "input"))
      (node (ref "U3") (pin "6") (pinfunction "P4_5_6") (pintype "bidirectional"))
    )
    (net (code "46") (name "GND") (class "Default")
      (node (ref "C1") (pin "P$2") (pinfunction "2_P$2") (pintype "passive"))
      (node (ref "C10") (pin "P$2") (pinfunction "2_P$2") (pintype "passive"))
      (node (ref "C11") (pin "P$2") (pinfunction "2_P$2") (pintype "passive"))
      (node (ref "C12") (pin "P$2") (pinfunction "2_P$2") (pintype "passive"))
      (node (ref "C13") (pin "P$2") (pinfunction "2_P$2") (pintype "passive"))
      (node (ref "C14") (pin "P$2") (pinfunction "2_P$2") (pintype "passive"))
      (node (ref "C15") (pin "P$2") (pinfunction "2_P$2") (pintype "passive"))
      (node (ref "C16") (pin "P$2") (pinfunction "2_P$2") (pintype "passive"))
      (node (ref "C17") (pin "P$2") (pinfunction "2_P$2") (pintype "passive"))
      (node (ref "C18") (pin "P$2") (pinfunction "2_P$2") (pintype "passive"))
      (node (ref "C19") (pin "P$1") (pinfunction "1_P$1") (pintype "passive"))
      (node (ref "C2") (pin "P$2") (pinfunction "2_P$2") (pintype "passive"))
      (node (ref "C20") (pin "P$1") (pinfunction "1_P$1") (pintype "passive"))
      (node (ref "C21") (pin "P$1") (pinfunction "1_P$1") (pintype "passive"))
      (node (ref "C22") (pin "P$1") (pinfunction "1_P$1") (pintype "passive"))
      (node (ref "C23") (pin "P$2") (pinfunction "2_P$2") (pintype "passive"))
      (node (ref "C24") (pin "P$1") (pinfunction "1_P$1") (pintype "passive"))
      (node (ref "C25") (pin "P$1") (pinfunction "1_P$1") (pintype "passive"))
      (node (ref "C26") (pin "P$2") (pinfunction "2_P$2") (pintype "passive"))
      (node (ref "C27") (pin "P$1") (pinfunction "1_P$1") (pintype "passive"))
      (node (ref "C28") (pin "P$2") (pinfunction "2_P$2") (pintype "passive"))
      (node (ref "C29") (pin "P$2") (pinfunction "2_P$2") (pintype "passive"))
      (node (ref "C3") (pin "P$2") (pinfunction "2_P$2") (pintype "passive"))
      (node (ref "C30") (pin "P$1") (pinfunction "1_P$1") (pintype "passive"))
      (node (ref "C31") (pin "2") (pinfunction "2_2") (pintype "passive"))
      (node (ref "C32") (pin "P$2") (pinfunction "2_P$2") (pintype "passive"))
      (node (ref "C33") (pin "P$2") (pinfunction "2_P$2") (pintype "passive"))
      (node (ref "C34") (pin "P$1") (pinfunction "1_P$1") (pintype "passive"))
      (node (ref "C35") (pin "P$1") (pinfunction "1_P$1") (pintype "passive"))
      (node (ref "C36") (pin "P$2") (pinfunction "2_P$2") (pintype "passive"))
      (node (ref "C37") (pin "P$2") (pinfunction "2_P$2") (pintype "passive"))
      (node (ref "C38") (pin "P$1") (pinfunction "1_P$1") (pintype "passive"))
      (node (ref "C39") (pin "P$2") (pinfunction "2_P$2") (pintype "passive"))
      (node (ref "C4") (pin "P$2") (pinfunction "2_P$2") (pintype "passive"))
      (node (ref "C40") (pin "P$2") (pinfunction "2_P$2") (pintype "passive"))
      (node (ref "C41") (pin "P$2") (pinfunction "2_P$2") (pintype "passive"))
      (node (ref "C42") (pin "P$2") (pinfunction "2_P$2") (pintype "passive"))
      (node (ref "C43") (pin "P$1") (pinfunction "1_P$1") (pintype "passive"))
      (node (ref "C5") (pin "P$2") (pinfunction "2_P$2") (pintype "passive"))
      (node (ref "C6") (pin "P$2") (pinfunction "2_P$2") (pintype "passive"))
      (node (ref "C7") (pin "P$2") (pinfunction "2_P$2") (pintype "passive"))
      (node (ref "C8") (pin "P$2") (pinfunction "2_P$2") (pintype "passive"))
      (node (ref "C9") (pin "P$2") (pinfunction "2_P$2") (pintype "passive"))
      (node (ref "J1") (pin "6") (pinfunction "SUPPLY_VOLTAGE_GROUND_6") (pintype "power_in"))
      (node (ref "J2") (pin "P$1") (pinfunction "P$1_P$1") (pintype "bidirectional"))
      (node (ref "J3") (pin "10") (pinfunction "10_10") (pintype "passive"))
      (node (ref "J3") (pin "6") (pinfunction "6_6") (pintype "passive"))
      (node (ref "J3") (pin "8") (pinfunction "8_8") (pintype "passive"))
      (node (ref "J6") (pin "GND") (pinfunction "GND_GND") (pintype "power_in"))
      (node (ref "J7") (pin "P$5") (pinfunction "GND_P$5") (pintype "bidirectional"))
      (node (ref "LED1") (pin "2") (pinfunction "C_2") (pintype "passive"))
      (node (ref "R1") (pin "P$1") (pinfunction "1_P$1") (pintype "passive"))
      (node (ref "R21") (pin "P$1") (pinfunction "1_P$1") (pintype "passive"))
      (node (ref "R22") (pin "P$1") (pinfunction "1_P$1") (pintype "passive"))
      (node (ref "R23") (pin "P$1") (pinfunction "1_P$1") (pintype "passive"))
      (node (ref "R24") (pin "P$1") (pinfunction "1_P$1") (pintype "passive"))
      (node (ref "RJ1") (pin "10") (pinfunction "GLO_10") (pintype "bidirectional"))
      (node (ref "RJ1") (pin "8") (pinfunction "P8_8") (pintype "bidirectional"))
      (node (ref "U1") (pin "22") (pinfunction "GND_22") (pintype "power_in"))
      (node (ref "U1") (pin "25") (pinfunction "25_25") (pintype "passive"))
      (node (ref "U10") (pin "2") (pinfunction "E(1)_2") (pintype "output"))
      (node (ref "U11") (pin "2") (pinfunction "E(1)_2") (pintype "output"))
      (node (ref "U12") (pin "2") (pinfunction "E(1)_2") (pintype "output"))
      (node (ref "U13") (pin "2") (pinfunction "E(1)_2") (pintype "output"))
      (node (ref "U14") (pin "2") (pinfunction "E(1)_2") (pintype "output"))
      (node (ref "U15") (pin "2") (pinfunction "E(1)_2") (pintype "output"))
      (node (ref "U16") (pin "2") (pinfunction "E(1)_2") (pintype "output"))
      (node (ref "U17") (pin "2") (pinfunction "E(1)_2") (pintype "output"))
      (node (ref "U2") (pin "2") (pinfunction "GND_2") (pintype "input"))
      (node (ref "U22") (pin "2") (pinfunction "E(1)_2") (pintype "output"))
      (node (ref "U23") (pin "2") (pinfunction "E(1)_2") (pintype "output"))
      (node (ref "U24") (pin "2") (pinfunction "E(1)_2") (pintype "output"))
      (node (ref "U25") (pin "2") (pinfunction "E(1)_2") (pintype "output"))
      (node (ref "U26") (pin "2") (pinfunction "E(1)_2") (pintype "output"))
      (node (ref "U27") (pin "2") (pinfunction "E(1)_2") (pintype "output"))
      (node (ref "U3") (pin "111") (pinfunction "VSS(IO)5_111") (pintype "bidirectional"))
      (node (ref "U3") (pin "124") (pinfunction "VSS(IO)6_124") (pintype "bidirectional"))
      (node (ref "U3") (pin "139") (pinfunction "VSS(IO)7_139") (pintype "bidirectional"))
      (node (ref "U3") (pin "150") (pinfunction "VSS(IO)8_150") (pintype "bidirectional"))
      (node (ref "U3") (pin "153") (pinfunction "VREFL_153") (pintype "bidirectional"))
      (node (ref "U3") (pin "156") (pinfunction "AVSS0_156") (pintype "bidirectional"))
      (node (ref "U3") (pin "157") (pinfunction "VREFL0_157") (pintype "bidirectional"))
      (node (ref "U3") (pin "170") (pinfunction "VSS(IO)9_170") (pintype "bidirectional"))
      (node (ref "U3") (pin "22") (pinfunction "VSS1_22") (pintype "bidirectional"))
      (node (ref "U3") (pin "28") (pinfunction "AVSS_USBHS_28") (pintype "bidirectional"))
      (node (ref "U3") (pin "29") (pinfunction "PVSS_USBHS_29") (pintype "bidirectional"))
      (node (ref "U3") (pin "30") (pinfunction "VSS2_USBHS_30") (pintype "bidirectional"))
      (node (ref "U3") (pin "33") (pinfunction "VSS1_USBHS_33") (pintype "bidirectional"))
      (node (ref "U3") (pin "35") (pinfunction "VSSIO_35") (pintype "bidirectional"))
      (node (ref "U3") (pin "45") (pinfunction "VSS_USB_45") (pintype "bidirectional"))
      (node (ref "U3") (pin "60") (pinfunction "VSS(IO)2_60") (pintype "bidirectional"))
      (node (ref "U3") (pin "63") (pinfunction "VSS(IO/DCDC)_63") (pintype "bidirectional"))
      (node (ref "U3") (pin "66") (pinfunction "VCC_DCDC(IO/DCDC)_66") (pintype "bidirectional"))
      (node (ref "U3") (pin "83") (pinfunction "VSS(IO)3_83") (pintype "bidirectional"))
      (node (ref "U3") (pin "98") (pinfunction "VSS(IO)4_98") (pintype "bidirectional"))
      (node (ref "U34") (pin "2") (pinfunction "E(1)_2") (pintype "output"))
      (node (ref "U35") (pin "2") (pinfunction "E(1)_2") (pintype "output"))
      (node (ref "U36") (pin "2") (pinfunction "E(1)_2") (pintype "output"))
      (node (ref "U37") (pin "2") (pinfunction "E(1)_2") (pintype "output"))
      (node (ref "U38") (pin "2") (pinfunction "E(1)_2") (pintype "output"))
      (node (ref "U39") (pin "2") (pinfunction "E(1)_2") (pintype "output"))
      (node (ref "U46") (pin "2") (pinfunction "E(1)_2") (pintype "output"))
      (node (ref "U47") (pin "2") (pinfunction "E(1)_2") (pintype "output"))
      (node (ref "U48") (pin "2") (pinfunction "E(1)_2") (pintype "output"))
      (node (ref "U49") (pin "2") (pinfunction "E(1)_2") (pintype "output"))
      (node (ref "U50") (pin "2") (pinfunction "E(1)_2") (pintype "output"))
      (node (ref "U51") (pin "2") (pinfunction "E(1)_2") (pintype "output"))
      (node (ref "U58") (pin "2") (pinfunction "E(1)_2") (pintype "output"))
      (node (ref "U59") (pin "2") (pinfunction "E(1)_2") (pintype "output"))
      (node (ref "U6") (pin "2") (pinfunction "E(1)_2") (pintype "output"))
      (node (ref "U60") (pin "2") (pinfunction "E(1)_2") (pintype "output"))
      (node (ref "U61") (pin "2") (pinfunction "E(1)_2") (pintype "output"))
      (node (ref "U62") (pin "2") (pinfunction "E(1)_2") (pintype "output"))
      (node (ref "U63") (pin "2") (pinfunction "E(1)_2") (pintype "output"))
      (node (ref "U7") (pin "2") (pinfunction "E(1)_2") (pintype "output"))
      (node (ref "U70") (pin "2") (pinfunction "E(1)_2") (pintype "output"))
      (node (ref "U71") (pin "2") (pinfunction "E(1)_2") (pintype "output"))
      (node (ref "U72") (pin "2") (pinfunction "E(1)_2") (pintype "output"))
      (node (ref "U73") (pin "2") (pinfunction "E(1)_2") (pintype "output"))
      (node (ref "U74") (pin "2") (pinfunction "E(1)_2") (pintype "output"))
      (node (ref "U75") (pin "2") (pinfunction "E(1)_2") (pintype "output"))
      (node (ref "X1") (pin "2") (pinfunction "2_2") (pintype "bidirectional"))
      (node (ref "X1") (pin "4") (pinfunction "4_4") (pintype "bidirectional"))
      (node (ref "X2") (pin "2") (pinfunction "2_2") (pintype "bidirectional"))
      (node (ref "X2") (pin "4") (pinfunction "4_4") (pintype "bidirectional"))
    )
    (net (code "47") (name "GNDE") (class "Default")
      (node (ref "J1") (pin "S1") (pinfunction "SHIELD_S1") (pintype "passive"))
      (node (ref "J1") (pin "S2") (pinfunction "SHIELD_S2") (pintype "passive"))
      (node (ref "J1") (pin "S3") (pinfunction "SHIELD_S3") (pintype "passive"))
      (node (ref "J1") (pin "S4") (pinfunction "SHIELD_S4") (pintype "passive"))
      (node (ref "J2") (pin "P$4") (pinfunction "P$4_P$4") (pintype "bidirectional"))
      (node (ref "J6") (pin "SHLD1") (pinfunction "SHIELD_1_SHLD1") (pintype "bidirectional"))
      (node (ref "J6") (pin "SHLD2") (pinfunction "SHIELD_2_SHLD2") (pintype "bidirectional"))
      (node (ref "J7") (pin "P$6") (pinfunction "SHIELD1_P$6") (pintype "bidirectional"))
      (node (ref "J7") (pin "P$7") (pinfunction "SHIELD2_P$7") (pintype "bidirectional"))
      (node (ref "J7") (pin "P$8") (pinfunction "SHIELD3_P$8") (pintype "bidirectional"))
      (node (ref "J7") (pin "P$9") (pinfunction "SHIELD4_P$9") (pintype "bidirectional"))
      (node (ref "RJ1") (pin "13") (pinfunction "GNDE0_13") (pintype "bidirectional"))
      (node (ref "RJ1") (pin "14") (pinfunction "GNDE1_14") (pintype "bidirectional"))
    )
    (net (code "48") (name "ID") (class "Default")
      (node (ref "J7") (pin "P$4") (pinfunction "ID_P$4") (pintype "bidirectional"))
    )
    (net (code "49") (name "IIC_1_SCL") (class "Default")
      (node (ref "R14") (pin "P$2") (pinfunction "2_P$2") (pintype "passive"))
      (node (ref "U3") (pin "132") (pinfunction "P1_0_132") (pintype "bidirectional"))
    )
    (net (code "50") (name "IIC_1_SDA") (class "Default")
      (node (ref "R15") (pin "P$2") (pinfunction "2_P$2") (pintype "passive"))
      (node (ref "U3") (pin "131") (pinfunction "P1_1_131") (pintype "bidirectional"))
    )
    (net (code "51") (name "INT_MI_01") (class "Default")
      (node (ref "U3") (pin "87") (pinfunction "P3_1_87") (pintype "bidirectional"))
    )
    (net (code "52") (name "INT_MI_02") (class "Default")
      (node (ref "U3") (pin "86") (pinfunction "P3_2_86") (pintype "bidirectional"))
    )
    (net (code "53") (name "INT_MI_03") (class "Default")
      (node (ref "U3") (pin "128") (pinfunction "P1_4_128") (pintype "bidirectional"))
    )
    (net (code "54") (name "INT_MI_04") (class "Default")
      (node (ref "U3") (pin "127") (pinfunction "P1_5_127") (pintype "bidirectional"))
    )
    (net (code "55") (name "LED1{slash}SPEED") (class "Default")
      (node (ref "RJ1") (pin "11") (pinfunction "YLO_11") (pintype "bidirectional"))
      (node (ref "U1") (pin "23") (pinfunction "LED0/ANEN_SPEED_23") (pintype "bidirectional"))
    )
    (net (code "56") (name "LS_01") (class "Default")
      (node (ref "J11") (pin "P$1") (pinfunction "P$1_P$1") (pintype "bidirectional"))
      (node (ref "U3") (pin "50") (pinfunction "P2_6_50") (pintype "bidirectional"))
    )
    (net (code "57") (name "LS_02") (class "Default")
      (node (ref "J12") (pin "P$1") (pinfunction "P$1_P$1") (pintype "bidirectional"))
      (node (ref "U3") (pin "51") (pinfunction "P2_5_51") (pintype "bidirectional"))
    )
    (net (code "58") (name "LS_03") (class "Default")
      (node (ref "J19") (pin "P$1") (pinfunction "P$1_P$1") (pintype "bidirectional"))
      (node (ref "U3") (pin "53") (pinfunction "P2_3_53") (pintype "bidirectional"))
    )
    (net (code "59") (name "LS_04") (class "Default")
      (node (ref "J20") (pin "P$1") (pinfunction "P$1_P$1") (pintype "bidirectional"))
      (node (ref "U3") (pin "54") (pinfunction "P2_2_54") (pintype "bidirectional"))
    )
    (net (code "60") (name "NC") (class "Default")
      (node (ref "RJ1") (pin "7") (pinfunction "P7_7") (pintype "bidirectional"))
    )
    (net (code "61") (name "Net-(C8-1)") (class "Default")
      (node (ref "C8") (pin "P$1") (pinfunction "1_P$1") (pintype "passive"))
      (node (ref "C9") (pin "P$1") (pinfunction "1_P$1") (pintype "passive"))
      (node (ref "FB1") (pin "2") (pinfunction "P$2_2") (pintype "bidirectional"))
      (node (ref "U1") (pin "2") (pinfunction "VDDA_3.3_2") (pintype "power_in"))
    )
    (net (code "62") (name "Net-(C24-2)") (class "Default")
      (node (ref "C24") (pin "P$2") (pinfunction "2_P$2") (pintype "passive"))
      (node (ref "U3") (pin "148") (pinfunction "VCL2_148") (pintype "bidirectional"))
    )
    (net (code "63") (name "Net-(C28-1)") (class "Default")
      (node (ref "C28") (pin "P$1") (pinfunction "1_P$1") (pintype "passive"))
      (node (ref "J7") (pin "P$1") (pinfunction "VBUS_P$1") (pintype "bidirectional"))
      (node (ref "R16") (pin "P$2") (pinfunction "2_P$2") (pintype "passive"))
      (node (ref "R21") (pin "P$2") (pinfunction "2_P$2") (pintype "passive"))
    )
    (net (code "64") (name "Net-(C33-1)") (class "Default")
      (node (ref "C33") (pin "P$1") (pinfunction "1_P$1") (pintype "passive"))
      (node (ref "U3") (pin "19") (pinfunction "VCLO_19") (pintype "bidirectional"))
    )
    (net (code "65") (name "Net-(C42-1)") (class "Default")
      (node (ref "C42") (pin "P$1") (pinfunction "1_P$1") (pintype "passive"))
      (node (ref "U3") (pin "62") (pinfunction "VCL1_62") (pintype "bidirectional"))
    )
    (net (code "66") (name "Net-(J7-D+)") (class "Default")
      (node (ref "J7") (pin "P$3") (pinfunction "D+_P$3") (pintype "bidirectional"))
      (node (ref "R18") (pin "P$2") (pinfunction "2_P$2") (pintype "passive"))
    )
    (net (code "67") (name "Net-(J7-D-)") (class "Default")
      (node (ref "J7") (pin "P$2") (pinfunction "D-_P$2") (pintype "bidirectional"))
      (node (ref "R17") (pin "P$2") (pinfunction "2_P$2") (pintype "passive"))
    )
    (net (code "68") (name "Net-(LED1-A)") (class "Default")
      (node (ref "LED1") (pin "1") (pinfunction "A_1") (pintype "passive"))
      (node (ref "R5") (pin "P$1") (pinfunction "1_P$1") (pintype "passive"))
    )
    (net (code "69") (name "Net-(LED4-A)") (class "Default")
      (node (ref "LED4") (pin "1") (pinfunction "A_1") (pintype "passive"))
      (node (ref "R32") (pin "P$1") (pinfunction "1_P$1") (pintype "passive"))
    )
    (net (code "70") (name "Net-(LED4-C)") (class "Default")
      (node (ref "LED4") (pin "2") (pinfunction "C_2") (pintype "passive"))
      (node (ref "U$1") (pin "P$1") (pinfunction "VC-_P$1") (pintype "bidirectional"))
      (node (ref "U6") (pin "3") (pinfunction "C(3)_3") (pintype "input"))
    )
    (net (code "71") (name "Net-(LED5-A)") (class "Default")
      (node (ref "LED5") (pin "1") (pinfunction "A_1") (pintype "passive"))
      (node (ref "R31") (pin "P$1") (pinfunction "1_P$1") (pintype "passive"))
    )
    (net (code "72") (name "Net-(LED5-C)") (class "Default")
      (node (ref "LED5") (pin "2") (pinfunction "C_2") (pintype "passive"))
      (node (ref "U$2") (pin "P$1") (pinfunction "VC-_P$1") (pintype "bidirectional"))
      (node (ref "U7") (pin "3") (pinfunction "C(3)_3") (pintype "input"))
    )
    (net (code "73") (name "Net-(LED8-A)") (class "Default")
      (node (ref "LED8") (pin "1") (pinfunction "A_1") (pintype "passive"))
      (node (ref "R52") (pin "P$1") (pinfunction "1_P$1") (pintype "passive"))
    )
    (net (code "74") (name "Net-(LED8-C)") (class "Default")
      (node (ref "LED8") (pin "2") (pinfunction "C_2") (pintype "passive"))
      (node (ref "U$7") (pin "P$1") (pinfunction "VC-_P$1") (pintype "bidirectional"))
      (node (ref "U16") (pin "3") (pinfunction "C(3)_3") (pintype "input"))
    )
    (net (code "75") (name "Net-(LED9-A)") (class "Default")
      (node (ref "LED9") (pin "1") (pinfunction "A_1") (pintype "passive"))
      (node (ref "R51") (pin "P$1") (pinfunction "1_P$1") (pintype "passive"))
    )
    (net (code "76") (name "Net-(LED9-C)") (class "Default")
      (node (ref "LED9") (pin "2") (pinfunction "C_2") (pintype "passive"))
      (node (ref "U$8") (pin "P$1") (pinfunction "VC-_P$1") (pintype "bidirectional"))
      (node (ref "U17") (pin "3") (pinfunction "C(3)_3") (pintype "input"))
    )
    (net (code "77") (name "Net-(R22-2)") (class "Default")
      (node (ref "R22") (pin "P$2") (pinfunction "2_P$2") (pintype "passive"))
      (node (ref "U3") (pin "27") (pinfunction "USBHS_RREF_27") (pintype "bidirectional"))
    )
    (net (code "78") (name "Net-(R23-2)") (class "Default")
      (node (ref "R23") (pin "P$2") (pinfunction "2_P$2") (pintype "passive"))
      (node (ref "U3") (pin "64") (pinfunction "VLO1(DCDC)_64") (pintype "bidirectional"))
    )
    (net (code "79") (name "Net-(R24-2)") (class "Default")
      (node (ref "R24") (pin "P$2") (pinfunction "2_P$2") (pintype "passive"))
      (node (ref "U3") (pin "65") (pinfunction "VLO2(DCDC)_65") (pintype "bidirectional"))
    )
    (net (code "80") (name "Net-(R29-2)") (class "Default")
      (node (ref "R29") (pin "P$2") (pinfunction "2_P$2") (pintype "passive"))
      (node (ref "U6") (pin "1") (pinfunction "B(2)_1") (pintype "input"))
    )
    (net (code "81") (name "Net-(R30-2)") (class "Default")
      (node (ref "R30") (pin "P$2") (pinfunction "2_P$2") (pintype "passive"))
      (node (ref "U7") (pin "1") (pinfunction "B(2)_1") (pintype "input"))
    )
    (net (code "82") (name "Net-(R49-2)") (class "Default")
      (node (ref "R49") (pin "P$2") (pinfunction "2_P$2") (pintype "passive"))
      (node (ref "U16") (pin "1") (pinfunction "B(2)_1") (pintype "input"))
    )
    (net (code "83") (name "Net-(R50-2)") (class "Default")
      (node (ref "R50") (pin "P$2") (pinfunction "2_P$2") (pintype "passive"))
      (node (ref "U17") (pin "1") (pinfunction "B(2)_1") (pintype "input"))
    )
    (net (code "84") (name "Net-(U10-B(2))") (class "Default")
      (node (ref "R38") (pin "2") (pinfunction "2_2") (pintype "passive"))
      (node (ref "U10") (pin "1") (pinfunction "B(2)_1") (pintype "input"))
    )
    (net (code "85") (name "Net-(U11-B(2))") (class "Default")
      (node (ref "R39") (pin "2") (pinfunction "2_2") (pintype "passive"))
      (node (ref "U11") (pin "1") (pinfunction "B(2)_1") (pintype "input"))
    )
    (net (code "86") (name "Net-(U12-B(2))") (class "Default")
      (node (ref "R40") (pin "2") (pinfunction "2_2") (pintype "passive"))
      (node (ref "U12") (pin "1") (pinfunction "B(2)_1") (pintype "input"))
    )
    (net (code "87") (name "Net-(U13-B(2))") (class "Default")
      (node (ref "R44") (pin "2") (pinfunction "2_2") (pintype "passive"))
      (node (ref "U13") (pin "1") (pinfunction "B(2)_1") (pintype "input"))
    )
    (net (code "88") (name "Net-(U14-B(2))") (class "Default")
      (node (ref "R45") (pin "2") (pinfunction "2_2") (pintype "passive"))
      (node (ref "U14") (pin "1") (pinfunction "B(2)_1") (pintype "input"))
    )
    (net (code "89") (name "Net-(U15-B(2))") (class "Default")
      (node (ref "R46") (pin "2") (pinfunction "2_2") (pintype "passive"))
      (node (ref "U15") (pin "1") (pinfunction "B(2)_1") (pintype "input"))
    )
    (net (code "90") (name "Net-(U22-B(2))") (class "Default")
      (node (ref "R62") (pin "2") (pinfunction "2_2") (pintype "passive"))
      (node (ref "U22") (pin "1") (pinfunction "B(2)_1") (pintype "input"))
    )
    (net (code "91") (name "Net-(U23-B(2))") (class "Default")
      (node (ref "R63") (pin "2") (pinfunction "2_2") (pintype "passive"))
      (node (ref "U23") (pin "1") (pinfunction "B(2)_1") (pintype "input"))
    )
    (net (code "92") (name "Net-(U24-B(2))") (class "Default")
      (node (ref "R64") (pin "2") (pinfunction "2_2") (pintype "passive"))
      (node (ref "U24") (pin "1") (pinfunction "B(2)_1") (pintype "input"))
    )
    (net (code "93") (name "Net-(U25-B(2))") (class "Default")
      (node (ref "R68") (pin "2") (pinfunction "2_2") (pintype "passive"))
      (node (ref "U25") (pin "1") (pinfunction "B(2)_1") (pintype "input"))
    )
    (net (code "94") (name "Net-(U26-B(2))") (class "Default")
      (node (ref "R69") (pin "2") (pinfunction "2_2") (pintype "passive"))
      (node (ref "U26") (pin "1") (pinfunction "B(2)_1") (pintype "input"))
    )
    (net (code "95") (name "Net-(U27-B(2))") (class "Default")
      (node (ref "R70") (pin "2") (pinfunction "2_2") (pintype "passive"))
      (node (ref "U27") (pin "1") (pinfunction "B(2)_1") (pintype "input"))
    )
    (net (code "96") (name "Net-(U34-B(2))") (class "Default")
      (node (ref "R86") (pin "2") (pinfunction "2_2") (pintype "passive"))
      (node (ref "U34") (pin "1") (pinfunction "B(2)_1") (pintype "input"))
    )
    (net (code "97") (name "Net-(U35-B(2))") (class "Default")
      (node (ref "R87") (pin "2") (pinfunction "2_2") (pintype "passive"))
      (node (ref "U35") (pin "1") (pinfunction "B(2)_1") (pintype "input"))
    )
    (net (code "98") (name "Net-(U36-B(2))") (class "Default")
      (node (ref "R88") (pin "2") (pinfunction "2_2") (pintype "passive"))
      (node (ref "U36") (pin "1") (pinfunction "B(2)_1") (pintype "input"))
    )
    (net (code "99") (name "Net-(U37-B(2))") (class "Default")
      (node (ref "R92") (pin "2") (pinfunction "2_2") (pintype "passive"))
      (node (ref "U37") (pin "1") (pinfunction "B(2)_1") (pintype "input"))
    )
    (net (code "100") (name "Net-(U38-B(2))") (class "Default")
      (node (ref "R93") (pin "2") (pinfunction "2_2") (pintype "passive"))
      (node (ref "U38") (pin "1") (pinfunction "B(2)_1") (pintype "input"))
    )
    (net (code "101") (name "Net-(U39-B(2))") (class "Default")
      (node (ref "R94") (pin "2") (pinfunction "2_2") (pintype "passive"))
      (node (ref "U39") (pin "1") (pinfunction "B(2)_1") (pintype "input"))
    )
    (net (code "102") (name "Net-(U46-B(2))") (class "Default")
      (node (ref "R110") (pin "2") (pinfunction "2_2") (pintype "passive"))
      (node (ref "U46") (pin "1") (pinfunction "B(2)_1") (pintype "input"))
    )
    (net (code "103") (name "Net-(U47-B(2))") (class "Default")
      (node (ref "R111") (pin "2") (pinfunction "2_2") (pintype "passive"))
      (node (ref "U47") (pin "1") (pinfunction "B(2)_1") (pintype "input"))
    )
    (net (code "104") (name "Net-(U48-B(2))") (class "Default")
      (node (ref "R112") (pin "2") (pinfunction "2_2") (pintype "passive"))
      (node (ref "U48") (pin "1") (pinfunction "B(2)_1") (pintype "input"))
    )
    (net (code "105") (name "Net-(U49-B(2))") (class "Default")
      (node (ref "R116") (pin "2") (pinfunction "2_2") (pintype "passive"))
      (node (ref "U49") (pin "1") (pinfunction "B(2)_1") (pintype "input"))
    )
    (net (code "106") (name "Net-(U50-B(2))") (class "Default")
      (node (ref "R117") (pin "2") (pinfunction "2_2") (pintype "passive"))
      (node (ref "U50") (pin "1") (pinfunction "B(2)_1") (pintype "input"))
    )
    (net (code "107") (name "Net-(U51-B(2))") (class "Default")
      (node (ref "R118") (pin "2") (pinfunction "2_2") (pintype "passive"))
      (node (ref "U51") (pin "1") (pinfunction "B(2)_1") (pintype "input"))
    )
    (net (code "108") (name "Net-(U58-B(2))") (class "Default")
      (node (ref "R134") (pin "2") (pinfunction "2_2") (pintype "passive"))
      (node (ref "U58") (pin "1") (pinfunction "B(2)_1") (pintype "input"))
    )
    (net (code "109") (name "Net-(U59-B(2))") (class "Default")
      (node (ref "R135") (pin "2") (pinfunction "2_2") (pintype "passive"))
      (node (ref "U59") (pin "1") (pinfunction "B(2)_1") (pintype "input"))
    )
    (net (code "110") (name "Net-(U60-B(2))") (class "Default")
      (node (ref "R136") (pin "2") (pinfunction "2_2") (pintype "passive"))
      (node (ref "U60") (pin "1") (pinfunction "B(2)_1") (pintype "input"))
    )
    (net (code "111") (name "Net-(U61-B(2))") (class "Default")
      (node (ref "R140") (pin "2") (pinfunction "2_2") (pintype "passive"))
      (node (ref "U61") (pin "1") (pinfunction "B(2)_1") (pintype "input"))
    )
    (net (code "112") (name "Net-(U62-B(2))") (class "Default")
      (node (ref "R141") (pin "2") (pinfunction "2_2") (pintype "passive"))
      (node (ref "U62") (pin "1") (pinfunction "B(2)_1") (pintype "input"))
    )
    (net (code "113") (name "Net-(U63-B(2))") (class "Default")
      (node (ref "R142") (pin "2") (pinfunction "2_2") (pintype "passive"))
      (node (ref "U63") (pin "1") (pinfunction "B(2)_1") (pintype "input"))
    )
    (net (code "114") (name "Net-(U70-B(2))") (class "Default")
      (node (ref "R158") (pin "2") (pinfunction "2_2") (pintype "passive"))
      (node (ref "U70") (pin "1") (pinfunction "B(2)_1") (pintype "input"))
    )
    (net (code "115") (name "Net-(U71-B(2))") (class "Default")
      (node (ref "R159") (pin "2") (pinfunction "2_2") (pintype "passive"))
      (node (ref "U71") (pin "1") (pinfunction "B(2)_1") (pintype "input"))
    )
    (net (code "116") (name "Net-(U72-B(2))") (class "Default")
      (node (ref "R160") (pin "2") (pinfunction "2_2") (pintype "passive"))
      (node (ref "U72") (pin "1") (pinfunction "B(2)_1") (pintype "input"))
    )
    (net (code "117") (name "Net-(U73-B(2))") (class "Default")
      (node (ref "R164") (pin "2") (pinfunction "2_2") (pintype "passive"))
      (node (ref "U73") (pin "1") (pinfunction "B(2)_1") (pintype "input"))
    )
    (net (code "118") (name "Net-(U74-B(2))") (class "Default")
      (node (ref "R165") (pin "2") (pinfunction "2_2") (pintype "passive"))
      (node (ref "U74") (pin "1") (pinfunction "B(2)_1") (pintype "input"))
    )
    (net (code "119") (name "Net-(U75-B(2))") (class "Default")
      (node (ref "R166") (pin "2") (pinfunction "2_2") (pintype "passive"))
      (node (ref "U75") (pin "1") (pinfunction "B(2)_1") (pintype "input"))
    )
    (net (code "120") (name "P$9") (class "Default")
      (node (ref "J4") (pin "P$9") (pinfunction "P$9_P$9") (pintype "bidirectional"))
    )
    (net (code "121") (name "P0_00") (class "Default")
      (node (ref "J4") (pin "P$2") (pinfunction "P$2_P$2") (pintype "bidirectional"))
      (node (ref "U3") (pin "169") (pinfunction "P0_0/AN0\\00_169") (pintype "bidirectional"))
    )
    (net (code "122") (name "P0_01") (class "Default")
      (node (ref "J4") (pin "P$1") (pinfunction "P$1_P$1") (pintype "bidirectional"))
      (node (ref "U3") (pin "168") (pinfunction "P0_1/AN001_168") (pintype "bidirectional"))
    )
    (net (code "123") (name "P0_02") (class "Default")
      (node (ref "J5") (pin "1") (pinfunction "1_1") (pintype "passive"))
      (node (ref "U3") (pin "167") (pinfunction "P0_2/AN002_167") (pintype "bidirectional"))
    )
    (net (code "124") (name "P0_03") (class "Default")
      (node (ref "J5") (pin "3") (pinfunction "3_3") (pintype "passive"))
      (node (ref "U3") (pin "166") (pinfunction "P0_3/PGAVSS000_166") (pintype "bidirectional"))
    )
    (net (code "125") (name "P0_04") (class "Default")
      (node (ref "J5") (pin "5") (pinfunction "5_5") (pintype "passive"))
      (node (ref "U3") (pin "165") (pinfunction "P0_4/AN100_165") (pintype "bidirectional"))
    )
    (net (code "126") (name "P0_05") (class "Default")
      (node (ref "J5") (pin "7") (pinfunction "7_7") (pintype "passive"))
      (node (ref "U3") (pin "164") (pinfunction "P0_5/AN101_164") (pintype "bidirectional"))
    )
    (net (code "127") (name "P0_06") (class "Default")
      (node (ref "J5") (pin "9") (pinfunction "9_9") (pintype "passive"))
      (node (ref "U3") (pin "163") (pinfunction "P0_6/AN102_163") (pintype "bidirectional"))
    )
    (net (code "128") (name "P0_07") (class "Default")
      (node (ref "J5") (pin "10") (pinfunction "10_10") (pintype "passive"))
      (node (ref "U3") (pin "162") (pinfunction "P0_7/PGVSS100_162") (pintype "bidirectional"))
    )
    (net (code "129") (name "P0_08") (class "Default")
      (node (ref "J5") (pin "8") (pinfunction "8_8") (pintype "passive"))
      (node (ref "U3") (pin "161") (pinfunction "P0_8/AN003_161") (pintype "bidirectional"))
    )
    (net (code "130") (name "P0_09") (class "Default")
      (node (ref "J5") (pin "6") (pinfunction "6_6") (pintype "passive"))
      (node (ref "U3") (pin "160") (pinfunction "P0_9/AN004_160") (pintype "bidirectional"))
    )
    (net (code "131") (name "P0_14") (class "Default")
      (node (ref "J5") (pin "4") (pinfunction "4_4") (pintype "passive"))
      (node (ref "U3") (pin "152") (pinfunction "P0_14/DA0/AN005/AN105_152") (pintype "bidirectional"))
    )
    (net (code "132") (name "P0_15") (class "Default")
      (node (ref "J5") (pin "2") (pinfunction "2_2") (pintype "passive"))
      (node (ref "U3") (pin "151") (pinfunction "P0_15/DA1/AN006/AN106_151") (pintype "bidirectional"))
    )
    (net (code "133") (name "P1_02") (class "Default")
      (node (ref "U3") (pin "130") (pinfunction "P1_2_130") (pintype "bidirectional"))
    )
    (net (code "134") (name "P1_03") (class "Default")
      (node (ref "U3") (pin "129") (pinfunction "P1_3_129") (pintype "bidirectional"))
    )
    (net (code "135") (name "P1_06") (class "Default")
      (node (ref "U3") (pin "126") (pinfunction "P1_6_126") (pintype "bidirectional"))
    )
    (net (code "136") (name "P1_07") (class "Default")
      (node (ref "U3") (pin "125") (pinfunction "P1_7_125") (pintype "bidirectional"))
    )
    (net (code "137") (name "P1_11") (class "Default")
      (node (ref "U3") (pin "92") (pinfunction "P1_11_92") (pintype "bidirectional"))
    )
    (net (code "138") (name "P1_12") (class "Default")
      (node (ref "U3") (pin "93") (pinfunction "P1_12_93") (pintype "bidirectional"))
    )
    (net (code "139") (name "P1_13") (class "Default")
      (node (ref "U3") (pin "94") (pinfunction "P1_13_94") (pintype "bidirectional"))
    )
    (net (code "140") (name "P1_14") (class "Default")
      (node (ref "U3") (pin "95") (pinfunction "P1_14_95") (pintype "bidirectional"))
    )
    (net (code "141") (name "P1_15") (class "Default")
      (node (ref "U3") (pin "96") (pinfunction "P1_15_96") (pintype "bidirectional"))
    )
    (net (code "142") (name "P4_00") (class "Default")
      (node (ref "J4") (pin "P$7") (pinfunction "P$7_P$7") (pintype "bidirectional"))
      (node (ref "U3") (pin "1") (pinfunction "P4_0_1") (pintype "bidirectional"))
    )
    (net (code "143") (name "P4_01") (class "Default")
      (node (ref "J4") (pin "P$8") (pinfunction "P$8_P$8") (pintype "bidirectional"))
      (node (ref "U3") (pin "2") (pinfunction "P4_1_2") (pintype "bidirectional"))
    )
    (net (code "144") (name "P4_02") (class "Default")
      (node (ref "U3") (pin "3") (pinfunction "P4_2_3") (pintype "bidirectional"))
    )
    (net (code "145") (name "P4_08") (class "Default")
      (node (ref "J4") (pin "P$20") (pinfunction "P$20_P$20") (pintype "bidirectional"))
      (node (ref "U3") (pin "43") (pinfunction "P4_8_43") (pintype "bidirectional"))
    )
    (net (code "146") (name "P4_09") (class "Default")
      (node (ref "J4") (pin "P$19") (pinfunction "P$19_P$19") (pintype "bidirectional"))
      (node (ref "U3") (pin "42") (pinfunction "P4_9_42") (pintype "bidirectional"))
    )
    (net (code "147") (name "P4_10") (class "Default")
      (node (ref "J4") (pin "P$18") (pinfunction "P$18_P$18") (pintype "bidirectional"))
      (node (ref "U3") (pin "41") (pinfunction "P4_10_41") (pintype "bidirectional"))
    )
    (net (code "148") (name "P4_11") (class "Default")
      (node (ref "J4") (pin "P$17") (pinfunction "P$17_P$17") (pintype "bidirectional"))
      (node (ref "U3") (pin "40") (pinfunction "P4_11_40") (pintype "bidirectional"))
    )
    (net (code "149") (name "P4_12") (class "Default")
      (node (ref "J4") (pin "P$16") (pinfunction "P$16_P$16") (pintype "bidirectional"))
      (node (ref "U3") (pin "39") (pinfunction "P4_12_39") (pintype "bidirectional"))
    )
    (net (code "150") (name "P4_13") (class "Default")
      (node (ref "J4") (pin "P$15") (pinfunction "P$15_P$15") (pintype "bidirectional"))
      (node (ref "U3") (pin "38") (pinfunction "P4_13_38") (pintype "bidirectional"))
    )
    (net (code "151") (name "P4_14") (class "Default")
      (node (ref "J4") (pin "P$14") (pinfunction "P$14_P$14") (pintype "bidirectional"))
      (node (ref "U3") (pin "37") (pinfunction "P4_14_37") (pintype "bidirectional"))
    )
    (net (code "152") (name "P4_15") (class "Default")
      (node (ref "J4") (pin "P$13") (pinfunction "P$13_P$13") (pintype "bidirectional"))
      (node (ref "U3") (pin "36") (pinfunction "P4_15_36") (pintype "bidirectional"))
    )
    (net (code "153") (name "P5_11") (class "Default")
      (node (ref "J4") (pin "P$6") (pinfunction "P$6_P$6") (pintype "bidirectional"))
      (node (ref "U3") (pin "176") (pinfunction "P5_11_176") (pintype "bidirectional"))
    )
    (net (code "154") (name "P5_12") (class "Default")
      (node (ref "J4") (pin "P$5") (pinfunction "P$5_P$5") (pintype "bidirectional"))
      (node (ref "U3") (pin "175") (pinfunction "P5_12_175") (pintype "bidirectional"))
    )
    (net (code "155") (name "P5_13") (class "Default")
      (node (ref "J4") (pin "P$4") (pinfunction "P$4_P$4") (pintype "bidirectional"))
      (node (ref "U3") (pin "174") (pinfunction "P5_13_174") (pintype "bidirectional"))
    )
    (net (code "156") (name "P6_00") (class "Default")
      (node (ref "U3") (pin "122") (pinfunction "P6_0_122") (pintype "bidirectional"))
    )
    (net (code "157") (name "P6_01") (class "Default")
      (node (ref "U3") (pin "121") (pinfunction "P6_1_121") (pintype "bidirectional"))
    )
    (net (code "158") (name "P6_02") (class "Default")
      (node (ref "U3") (pin "120") (pinfunction "P6_2_120") (pintype "bidirectional"))
    )
    (net (code "159") (name "P6_03") (class "Default")
      (node (ref "U3") (pin "119") (pinfunction "P6_3_119") (pintype "bidirectional"))
    )
    (net (code "160") (name "P6_04") (class "Default")
      (node (ref "U3") (pin "118") (pinfunction "P6_4_118") (pintype "bidirectional"))
    )
    (net (code "161") (name "P6_05") (class "Default")
      (node (ref "U3") (pin "117") (pinfunction "P6_5_117") (pintype "bidirectional"))
    )
    (net (code "162") (name "P6_06") (class "Default")
      (node (ref "U3") (pin "116") (pinfunction "P6_6_116") (pintype "bidirectional"))
    )
    (net (code "163") (name "P6_07") (class "Default")
      (node (ref "U3") (pin "115") (pinfunction "P6_7_115") (pintype "bidirectional"))
    )
    (net (code "164") (name "P6_08") (class "Default")
      (node (ref "U3") (pin "99") (pinfunction "P6_8_99") (pintype "bidirectional"))
    )
    (net (code "165") (name "P6_09") (class "Default")
      (node (ref "U3") (pin "100") (pinfunction "P6_9_100") (pintype "bidirectional"))
    )
    (net (code "166") (name "P6_10") (class "Default")
      (node (ref "U3") (pin "101") (pinfunction "P6_10_101") (pintype "bidirectional"))
    )
    (net (code "167") (name "P6_11") (class "Default")
      (node (ref "U3") (pin "102") (pinfunction "P6_11_102") (pintype "bidirectional"))
    )
    (net (code "168") (name "P6_12") (class "Default")
      (node (ref "U3") (pin "103") (pinfunction "P6_12_103") (pintype "bidirectional"))
    )
    (net (code "169") (name "P6_13") (class "Default")
      (node (ref "U3") (pin "104") (pinfunction "P6_13_104") (pintype "bidirectional"))
    )
    (net (code "170") (name "P6_14") (class "Default")
      (node (ref "U3") (pin "105") (pinfunction "P6_14_105") (pintype "bidirectional"))
    )
    (net (code "171") (name "P6_15") (class "Default")
      (node (ref "U3") (pin "106") (pinfunction "P6_15_106") (pintype "bidirectional"))
    )
    (net (code "172") (name "P7_06") (class "Default")
      (node (ref "J4") (pin "P$10") (pinfunction "P$10_P$10") (pintype "bidirectional"))
      (node (ref "U3") (pin "14") (pinfunction "P7_6_14") (pintype "bidirectional"))
    )
    (net (code "173") (name "P7_07") (class "Default")
      (node (ref "J4") (pin "P$11") (pinfunction "P$11_P$11") (pintype "bidirectional"))
      (node (ref "U3") (pin "15") (pinfunction "P7_7_15") (pintype "bidirectional"))
    )
    (net (code "174") (name "P8_00") (class "Default")
      (node (ref "U3") (pin "133") (pinfunction "P8_0_133") (pintype "bidirectional"))
    )
    (net (code "175") (name "P8_01") (class "Default")
      (node (ref "U3") (pin "134") (pinfunction "P8_1_134") (pintype "bidirectional"))
    )
    (net (code "176") (name "P8_02") (class "Default")
      (node (ref "U3") (pin "135") (pinfunction "P8_2_135") (pintype "bidirectional"))
    )
    (net (code "177") (name "P8_03") (class "Default")
      (node (ref "U3") (pin "136") (pinfunction "P8_3_136") (pintype "bidirectional"))
    )
    (net (code "178") (name "P8_04") (class "Default")
      (node (ref "U3") (pin "137") (pinfunction "P8_4_137") (pintype "bidirectional"))
    )
    (net (code "179") (name "P8_05") (class "Default")
      (node (ref "J4") (pin "P$3") (pinfunction "P$3_P$3") (pintype "bidirectional"))
      (node (ref "U3") (pin "173") (pinfunction "P8_5_173") (pintype "bidirectional"))
    )
    (net (code "180") (name "PA_00") (class "Default")
      (node (ref "U3") (pin "114") (pinfunction "PA_0_114") (pintype "bidirectional"))
    )
    (net (code "181") (name "PA_01") (class "Default")
      (node (ref "U3") (pin "113") (pinfunction "PA_1_113") (pintype "bidirectional"))
    )
    (net (code "182") (name "PA_08") (class "Default")
      (node (ref "U3") (pin "107") (pinfunction "PA_8_107") (pintype "bidirectional"))
    )
    (net (code "183") (name "PA_09") (class "Default")
      (node (ref "U3") (pin "108") (pinfunction "PA_9_108") (pintype "bidirectional"))
    )
    (net (code "184") (name "PA_10") (class "Default")
      (node (ref "U3") (pin "109") (pinfunction "PA_10_109") (pintype "bidirectional"))
    )
    (net (code "185") (name "PB_00") (class "Default")
      (node (ref "J4") (pin "P$12") (pinfunction "P$12_P$12") (pintype "bidirectional"))
      (node (ref "U3") (pin "16") (pinfunction "PB_0_16") (pintype "bidirectional"))
    )
    (net (code "186") (name "R51") (class "Default")
      (node (ref "R7") (pin "P$1") (pinfunction "1_P$1") (pintype "passive"))
      (node (ref "RJ1") (pin "12") (pinfunction "YHI_12") (pintype "bidirectional"))
    )
    (net (code "187") (name "R52") (class "Default")
      (node (ref "R8") (pin "P$1") (pinfunction "1_P$1") (pintype "passive"))
      (node (ref "RJ1") (pin "9") (pinfunction "GHI_9") (pintype "bidirectional"))
    )
    (net (code "188") (name "RELAY_1") (class "Default")
      (node (ref "R29") (pin "P$1") (pinfunction "1_P$1") (pintype "passive"))
      (node (ref "U3") (pin "56") (pinfunction "P3_14_56") (pintype "bidirectional"))
    )
    (net (code "189") (name "RELAY_2") (class "Default")
      (node (ref "R30") (pin "P$1") (pinfunction "1_P$1") (pintype "passive"))
      (node (ref "U3") (pin "55") (pinfunction "P3_13_55") (pintype "bidirectional"))
    )
    (net (code "190") (name "RELAY_3") (class "Default")
      (node (ref "R49") (pin "P$1") (pinfunction "1_P$1") (pintype "passive"))
      (node (ref "U3") (pin "52") (pinfunction "P2_4_52") (pintype "bidirectional"))
    )
    (net (code "191") (name "RELAY_4") (class "Default")
      (node (ref "R50") (pin "P$1") (pinfunction "1_P$1") (pintype "passive"))
      (node (ref "U3") (pin "49") (pinfunction "P2_7_49") (pintype "bidirectional"))
    )
    (net (code "192") (name "RESET") (class "Default")
      (node (ref "C16") (pin "P$1") (pinfunction "1_P$1") (pintype "passive"))
      (node (ref "J3") (pin "9") (pinfunction "9_9") (pintype "passive"))
      (node (ref "R13") (pin "P$1") (pinfunction "1_P$1") (pintype "passive"))
      (node (ref "U3") (pin "67") (pinfunction "RES#_67") (pintype "bidirectional"))
    )
    (net (code "193") (name "REXT") (class "Default")
      (node (ref "C3") (pin "P$1") (pinfunction "1_P$1") (pintype "passive"))
      (node (ref "R1") (pin "P$2") (pinfunction "2_P$2") (pintype "passive"))
      (node (ref "U1") (pin "9") (pinfunction "REXT_9") (pintype "input"))
    )
    (net (code "194") (name "RO_NEG_1") (class "Default")
      (node (ref "J15") (pin "P$2") (pinfunction "P$2_P$2") (pintype "bidirectional"))
      (node (ref "U$1") (pin "P$3") (pinfunction "VO-_P$3") (pintype "bidirectional"))
    )
    (net (code "195") (name "RO_NEG_2") (class "Default")
      (node (ref "J16") (pin "P$2") (pinfunction "P$2_P$2") (pintype "bidirectional"))
      (node (ref "U$2") (pin "P$3") (pinfunction "VO-_P$3") (pintype "bidirectional"))
    )
    (net (code "196") (name "RO_NEG_3") (class "Default")
      (node (ref "J23") (pin "P$2") (pinfunction "P$2_P$2") (pintype "bidirectional"))
      (node (ref "U$7") (pin "P$3") (pinfunction "VO-_P$3") (pintype "bidirectional"))
    )
    (net (code "197") (name "RO_NEG_4") (class "Default")
      (node (ref "J24") (pin "P$2") (pinfunction "P$2_P$2") (pintype "bidirectional"))
      (node (ref "U$8") (pin "P$3") (pinfunction "VO-_P$3") (pintype "bidirectional"))
    )
    (net (code "198") (name "RO_POS_1") (class "Default")
      (node (ref "J15") (pin "P$1") (pinfunction "P$1_P$1") (pintype "bidirectional"))
      (node (ref "U$1") (pin "P$4") (pinfunction "VO+_P$4") (pintype "bidirectional"))
    )
    (net (code "199") (name "RO_POS_2") (class "Default")
      (node (ref "J16") (pin "P$1") (pinfunction "P$1_P$1") (pintype "bidirectional"))
      (node (ref "U$2") (pin "P$4") (pinfunction "VO+_P$4") (pintype "bidirectional"))
    )
    (net (code "200") (name "RO_POS_3") (class "Default")
      (node (ref "J23") (pin "P$1") (pinfunction "P$1_P$1") (pintype "bidirectional"))
      (node (ref "U$7") (pin "P$4") (pinfunction "VO+_P$4") (pintype "bidirectional"))
    )
    (net (code "201") (name "RO_POS_4") (class "Default")
      (node (ref "J24") (pin "P$1") (pinfunction "P$1_P$1") (pintype "bidirectional"))
      (node (ref "U$8") (pin "P$4") (pinfunction "VO+_P$4") (pintype "bidirectional"))
    )
    (net (code "202") (name "RXD0") (class "Default")
      (node (ref "R10") (pin "P$2") (pinfunction "2_P$2") (pintype "passive"))
      (node (ref "U1") (pin "13") (pinfunction "RXD0_13") (pintype "bidirectional"))
    )
    (net (code "203") (name "RXD1") (class "Default")
      (node (ref "R9") (pin "P$2") (pinfunction "2_P$2") (pintype "passive"))
      (node (ref "U1") (pin "12") (pinfunction "RXD1_12") (pintype "bidirectional"))
    )
    (net (code "204") (name "RXER") (class "Default")
      (node (ref "R11") (pin "P$2") (pinfunction "2_P$2") (pintype "passive"))
      (node (ref "U1") (pin "17") (pinfunction "RXER_17") (pintype "bidirectional"))
    )
    (net (code "205") (name "RXM") (class "Default")
      (node (ref "RJ1") (pin "6") (pinfunction "RD-_6") (pintype "bidirectional"))
      (node (ref "U1") (pin "3") (pinfunction "RXM_3") (pintype "bidirectional"))
    )
    (net (code "206") (name "RXP") (class "Default")
      (node (ref "RJ1") (pin "3") (pinfunction "RD+_3") (pintype "bidirectional"))
      (node (ref "U1") (pin "4") (pinfunction "RXP_4") (pintype "bidirectional"))
    )
    (net (code "207") (name "SD1_CD") (class "Default")
      (node (ref "J1") (pin "10") (pinfunction "CD_SWITCH2_10") (pintype "bidirectional"))
      (node (ref "U3") (pin "146") (pinfunction "P5_6/AN019_146") (pintype "bidirectional"))
    )
    (net (code "208") (name "SD1_CLK") (class "Default")
      (node (ref "J1") (pin "5") (pinfunction "CLOCK_5") (pintype "bidirectional"))
      (node (ref "U3") (pin "140") (pinfunction "P5_0/AN016_140") (pintype "bidirectional"))
    )
    (net (code "209") (name "SD1_CMD") (class "Default")
      (node (ref "J1") (pin "3") (pinfunction "COMMAND/RESPONSE_3") (pintype "bidirectional"))
      (node (ref "U3") (pin "141") (pinfunction "P5_1/AN116_141") (pintype "bidirectional"))
    )
    (net (code "210") (name "SD1_DAT0") (class "Default")
      (node (ref "J1") (pin "7") (pinfunction "DATA_LINE[BIT_0]_7") (pintype "bidirectional"))
      (node (ref "U3") (pin "142") (pinfunction "P5_2/AN017_142") (pintype "bidirectional"))
    )
    (net (code "211") (name "SD1_DAT1") (class "Default")
      (node (ref "J1") (pin "8") (pinfunction "DATA_LINE[BIT_1]_8") (pintype "bidirectional"))
      (node (ref "U3") (pin "143") (pinfunction "P5_3/AN117_143") (pintype "bidirectional"))
    )
    (net (code "212") (name "SD1_DAT2") (class "Default")
      (node (ref "J1") (pin "1") (pinfunction "DATA_LINE[BIT_2]_1") (pintype "bidirectional"))
      (node (ref "U3") (pin "144") (pinfunction "P5_4/AN018_144") (pintype "bidirectional"))
    )
    (net (code "213") (name "SD1_DAT3") (class "Default")
      (node (ref "J1") (pin "2") (pinfunction "CARD_DETECT/DATA_LINE[BIT_3]_2") (pintype "bidirectional"))
      (node (ref "U3") (pin "145") (pinfunction "P5_5/AN118_145") (pintype "bidirectional"))
    )
    (net (code "214") (name "SD1_WP") (class "Default")
      (node (ref "J1") (pin "9") (pinfunction "CD_SWITCH1_9") (pintype "bidirectional"))
      (node (ref "U3") (pin "147") (pinfunction "P5_7/AN119_147") (pintype "bidirectional"))
    )
    (net (code "215") (name "TCK") (class "Default")
      (node (ref "J3") (pin "7") (pinfunction "7_7") (pintype "passive"))
      (node (ref "U3") (pin "88") (pinfunction "P3_0_88") (pintype "bidirectional"))
    )
    (net (code "216") (name "TDI") (class "Default")
      (node (ref "J3") (pin "1") (pinfunction "1_1") (pintype "passive"))
      (node (ref "U3") (pin "91") (pinfunction "P1_10_91") (pintype "bidirectional"))
    )
    (net (code "217") (name "TDO") (class "Default")
      (node (ref "J3") (pin "3") (pinfunction "3_3") (pintype "passive"))
      (node (ref "U3") (pin "90") (pinfunction "P1_9_90") (pintype "bidirectional"))
    )
    (net (code "218") (name "TMS") (class "Default")
      (node (ref "J3") (pin "5") (pinfunction "5_5") (pintype "passive"))
      (node (ref "U3") (pin "89") (pinfunction "P1_8_89") (pintype "bidirectional"))
    )
    (net (code "219") (name "TXM") (class "Default")
      (node (ref "RJ1") (pin "2") (pinfunction "TD-_2") (pintype "bidirectional"))
      (node (ref "U1") (pin "5") (pinfunction "TXM_5") (pintype "bidirectional"))
    )
    (net (code "220") (name "TXP") (class "Default")
      (node (ref "RJ1") (pin "1") (pinfunction "TD+_1") (pintype "bidirectional"))
      (node (ref "U1") (pin "6") (pinfunction "TXP_6") (pintype "bidirectional"))
    )
    (net (code "221") (name "USBHS_FAULT") (class "Default")
      (node (ref "R19") (pin "P$1") (pinfunction "1_P$1") (pintype "passive"))
      (node (ref "U2") (pin "3") (pinfunction "FLG_3") (pintype "input"))
      (node (ref "U3") (pin "78") (pinfunction "P3_8_78") (pintype "bidirectional"))
    )
    (net (code "222") (name "USBHS_N") (class "Default")
      (node (ref "J6") (pin "D-") (pinfunction "D-_D-") (pintype "bidirectional"))
      (node (ref "U3") (pin "31") (pinfunction "USBHS_DM_31") (pintype "bidirectional"))
    )
    (net (code "223") (name "USBHS_P") (class "Default")
      (node (ref "J6") (pin "D+") (pinfunction "D+_D+") (pintype "bidirectional"))
      (node (ref "U3") (pin "32") (pinfunction "USBHS_DP_32") (pintype "bidirectional"))
    )
    (net (code "224") (name "USBHS_VBUS") (class "Default")
      (node (ref "C29") (pin "P$1") (pinfunction "1_P$1") (pintype "passive"))
      (node (ref "C31") (pin "1") (pinfunction "1_1") (pintype "passive"))
      (node (ref "J6") (pin "VBUS") (pinfunction "VBUS_VBUS") (pintype "power_in"))
      (node (ref "U2") (pin "5") (pinfunction "OUT_5") (pintype "input"))
      (node (ref "U3") (pin "17") (pinfunction "PB_1_17") (pintype "bidirectional"))
    )
    (net (code "225") (name "USBHS_VBUSEN") (class "Default")
      (node (ref "R20") (pin "P$1") (pinfunction "1_P$1") (pintype "passive"))
      (node (ref "U2") (pin "1") (pinfunction "EN_1") (pintype "input"))
    )
    (net (code "226") (name "USB_N") (class "Default")
      (node (ref "R17") (pin "P$1") (pinfunction "1_P$1") (pintype "passive"))
      (node (ref "U3") (pin "46") (pinfunction "USB_DM_46") (pintype "bidirectional"))
    )
    (net (code "227") (name "USB_P") (class "Default")
      (node (ref "R18") (pin "P$1") (pinfunction "1_P$1") (pintype "passive"))
      (node (ref "U3") (pin "47") (pinfunction "USB_DP_47") (pintype "bidirectional"))
    )
    (net (code "228") (name "USB_VBUS_B") (class "Default")
      (node (ref "R16") (pin "P$1") (pinfunction "1_P$1") (pintype "passive"))
      (node (ref "U3") (pin "44") (pinfunction "P4_7_44") (pintype "bidirectional"))
    )
    (net (code "229") (name "VCL_F(FLASH)") (class "Default")
      (node (ref "C34") (pin "P$2") (pinfunction "2_P$2") (pintype "passive"))
      (node (ref "U3") (pin "112") (pinfunction "VCL_F(FLASH)_112") (pintype "bidirectional"))
    )
    (net (code "230") (name "VDD") (class "Default")
      (node (ref "C14") (pin "P$1") (pinfunction "1_P$1") (pintype "passive"))
      (node (ref "C15") (pin "P$1") (pinfunction "1_P$1") (pintype "passive"))
      (node (ref "C19") (pin "P$2") (pinfunction "2_P$2") (pintype "passive"))
      (node (ref "C20") (pin "P$2") (pinfunction "2_P$2") (pintype "passive"))
      (node (ref "C21") (pin "P$2") (pinfunction "2_P$2") (pintype "passive"))
      (node (ref "C22") (pin "P$2") (pinfunction "2_P$2") (pintype "passive"))
      (node (ref "C25") (pin "P$2") (pinfunction "2_P$2") (pintype "passive"))
      (node (ref "C27") (pin "P$2") (pinfunction "2_P$2") (pintype "passive"))
      (node (ref "C30") (pin "P$2") (pinfunction "2_P$2") (pintype "passive"))
      (node (ref "C35") (pin "P$2") (pinfunction "2_P$2") (pintype "passive"))
      (node (ref "C36") (pin "P$1") (pinfunction "1_P$1") (pintype "passive"))
      (node (ref "C38") (pin "P$2") (pinfunction "2_P$2") (pintype "passive"))
      (node (ref "C39") (pin "P$1") (pinfunction "1_P$1") (pintype "passive"))
      (node (ref "C4") (pin "P$1") (pinfunction "1_P$1") (pintype "passive"))
      (node (ref "C40") (pin "P$1") (pinfunction "1_P$1") (pintype "passive"))
      (node (ref "C41") (pin "P$1") (pinfunction "1_P$1") (pintype "passive"))
      (node (ref "C43") (pin "P$2") (pinfunction "2_P$2") (pintype "passive"))
      (node (ref "C5") (pin "P$1") (pinfunction "1_P$1") (pintype "passive"))
      (node (ref "C7") (pin "P$1") (pinfunction "1_P$1") (pintype "passive"))
      (node (ref "FB1") (pin "1") (pinfunction "P$1_1") (pintype "bidirectional"))
      (node (ref "J1") (pin "4") (pinfunction "SUPPLY_VOLTAGE_4") (pintype "power_in"))
      (node (ref "J3") (pin "2") (pinfunction "2_2") (pintype "passive"))
      (node (ref "J3") (pin "4") (pinfunction "4_4") (pintype "passive"))
      (node (ref "L1") (pin "2") (pinfunction "P$2_2") (pintype "bidirectional"))
      (node (ref "R13") (pin "P$2") (pinfunction "2_P$2") (pintype "passive"))
      (node (ref "R14") (pin "P$1") (pinfunction "1_P$1") (pintype "passive"))
      (node (ref "R15") (pin "P$1") (pinfunction "1_P$1") (pintype "passive"))
      (node (ref "R2") (pin "P$2") (pinfunction "2_P$2") (pintype "passive"))
      (node (ref "R3") (pin "P$2") (pinfunction "2_P$2") (pintype "passive"))
      (node (ref "R4") (pin "P$2") (pinfunction "2_P$2") (pintype "passive"))
      (node (ref "R5") (pin "P$2") (pinfunction "2_P$2") (pintype "passive"))
      (node (ref "R6") (pin "P$2") (pinfunction "2_P$2") (pintype "passive"))
      (node (ref "R7") (pin "P$2") (pinfunction "2_P$2") (pintype "passive"))
      (node (ref "R8") (pin "P$2") (pinfunction "2_P$2") (pintype "passive"))
      (node (ref "U1") (pin "14") (pinfunction "VDDIO_14") (pintype "power_in"))
      (node (ref "U3") (pin "110") (pinfunction "VCC(IO)5_110") (pintype "bidirectional"))
      (node (ref "U3") (pin "123") (pinfunction "VCC(IO)6_123") (pintype "bidirectional"))
      (node (ref "U3") (pin "138") (pinfunction "VCC(IO)7_138") (pintype "bidirectional"))
      (node (ref "U3") (pin "149") (pinfunction "VCC(IO)8_149") (pintype "bidirectional"))
      (node (ref "U3") (pin "154") (pinfunction "VREFH_154") (pintype "bidirectional"))
      (node (ref "U3") (pin "155") (pinfunction "AVCC0_155") (pintype "bidirectional"))
      (node (ref "U3") (pin "158") (pinfunction "VREFH0_158") (pintype "bidirectional"))
      (node (ref "U3") (pin "171") (pinfunction "VCC(IO)9_171") (pintype "bidirectional"))
      (node (ref "U3") (pin "25") (pinfunction "VCC1_25") (pintype "bidirectional"))
      (node (ref "U3") (pin "26") (pinfunction "AVCC_SUBHS_26") (pintype "bidirectional"))
      (node (ref "U3") (pin "34") (pinfunction "VCC_USBHS_34") (pintype "bidirectional"))
      (node (ref "U3") (pin "48") (pinfunction "VCC_USB_48") (pintype "bidirectional"))
      (node (ref "U3") (pin "61") (pinfunction "VCC(IO)2_61") (pintype "bidirectional"))
      (node (ref "U3") (pin "84") (pinfunction "VCC(IO)3_84") (pintype "bidirectional"))
      (node (ref "U3") (pin "97") (pinfunction "VCC(IO)4_97") (pintype "bidirectional"))
    )
    (net (code "231") (name "VDD5") (class "Default")
      (node (ref "C23") (pin "P$1") (pinfunction "1_P$1") (pintype "passive"))
      (node (ref "C26") (pin "P$1") (pinfunction "1_P$1") (pintype "passive"))
      (node (ref "J2") (pin "P$3") (pinfunction "P$3_P$3") (pintype "bidirectional"))
      (node (ref "R19") (pin "P$2") (pinfunction "2_P$2") (pintype "passive"))
      (node (ref "R20") (pin "P$2") (pinfunction "2_P$2") (pintype "passive"))
      (node (ref "R31") (pin "P$2") (pinfunction "2_P$2") (pintype "passive"))
      (node (ref "R32") (pin "P$2") (pinfunction "2_P$2") (pintype "passive"))
      (node (ref "R51") (pin "P$2") (pinfunction "2_P$2") (pintype "passive"))
      (node (ref "R52") (pin "P$2") (pinfunction "2_P$2") (pintype "passive"))
      (node (ref "U$1") (pin "P$2") (pinfunction "VC+_P$2") (pintype "bidirectional"))
      (node (ref "U$2") (pin "P$2") (pinfunction "VC+_P$2") (pintype "bidirectional"))
      (node (ref "U$7") (pin "P$2") (pinfunction "VC+_P$2") (pintype "bidirectional"))
      (node (ref "U$8") (pin "P$2") (pinfunction "VC+_P$2") (pintype "bidirectional"))
      (node (ref "U2") (pin "4") (pinfunction "VIN_4") (pintype "input"))
    )
    (net (code "232") (name "VDD12") (class "Default")
      (node (ref "J10") (pin "P$1") (pinfunction "P$1_P$1") (pintype "bidirectional"))
      (node (ref "J10") (pin "P$2") (pinfunction "P$2_P$2") (pintype "bidirectional"))
      (node (ref "J11") (pin "P$2") (pinfunction "P$2_P$2") (pintype "bidirectional"))
      (node (ref "J12") (pin "P$2") (pinfunction "P$2_P$2") (pintype "bidirectional"))
      (node (ref "J13") (pin "1") (pinfunction "1-HLFB+_1") (pintype "passive"))
      (node (ref "J13") (pin "2") (pinfunction "2-INPUT_B+_2") (pintype "passive"))
      (node (ref "J13") (pin "3") (pinfunction "3-INPUT_A+_3") (pintype "passive"))
      (node (ref "J13") (pin "4") (pinfunction "4-ENABLE+_4") (pintype "passive"))
      (node (ref "J14") (pin "1") (pinfunction "1-HLFB+_1") (pintype "passive"))
      (node (ref "J14") (pin "2") (pinfunction "2-INPUT_B+_2") (pintype "passive"))
      (node (ref "J14") (pin "3") (pinfunction "3-INPUT_A+_3") (pintype "passive"))
      (node (ref "J14") (pin "4") (pinfunction "4-ENABLE+_4") (pintype "passive"))
      (node (ref "J17") (pin "1") (pinfunction "1-HLFB+_1") (pintype "passive"))
      (node (ref "J17") (pin "2") (pinfunction "2-INPUT_B+_2") (pintype "passive"))
      (node (ref "J17") (pin "3") (pinfunction "3-INPUT_A+_3") (pintype "passive"))
      (node (ref "J17") (pin "4") (pinfunction "4-ENABLE+_4") (pintype "passive"))
      (node (ref "J18") (pin "1") (pinfunction "1-HLFB+_1") (pintype "passive"))
      (node (ref "J18") (pin "2") (pinfunction "2-INPUT_B+_2") (pintype "passive"))
      (node (ref "J18") (pin "3") (pinfunction "3-INPUT_A+_3") (pintype "passive"))
      (node (ref "J18") (pin "4") (pinfunction "4-ENABLE+_4") (pintype "passive"))
      (node (ref "J19") (pin "P$2") (pinfunction "P$2_P$2") (pintype "bidirectional"))
      (node (ref "J20") (pin "P$2") (pinfunction "P$2_P$2") (pintype "bidirectional"))
      (node (ref "J21") (pin "1") (pinfunction "1-HLFB+_1") (pintype "passive"))
      (node (ref "J21") (pin "2") (pinfunction "2-INPUT_B+_2") (pintype "passive"))
      (node (ref "J21") (pin "3") (pinfunction "3-INPUT_A+_3") (pintype "passive"))
      (node (ref "J21") (pin "4") (pinfunction "4-ENABLE+_4") (pintype "passive"))
      (node (ref "J22") (pin "1") (pinfunction "1-HLFB+_1") (pintype "passive"))
      (node (ref "J22") (pin "2") (pinfunction "2-INPUT_B+_2") (pintype "passive"))
      (node (ref "J22") (pin "3") (pinfunction "3-INPUT_A+_3") (pintype "passive"))
      (node (ref "J22") (pin "4") (pinfunction "4-ENABLE+_4") (pintype "passive"))
      (node (ref "J25") (pin "1") (pinfunction "1-HLFB+_1") (pintype "passive"))
      (node (ref "J25") (pin "2") (pinfunction "2-INPUT_B+_2") (pintype "passive"))
      (node (ref "J25") (pin "3") (pinfunction "3-INPUT_A+_3") (pintype "passive"))
      (node (ref "J25") (pin "4") (pinfunction "4-ENABLE+_4") (pintype "passive"))
      (node (ref "J26") (pin "1") (pinfunction "1-HLFB+_1") (pintype "passive"))
      (node (ref "J26") (pin "2") (pinfunction "2-INPUT_B+_2") (pintype "passive"))
      (node (ref "J26") (pin "3") (pinfunction "3-INPUT_A+_3") (pintype "passive"))
      (node (ref "J26") (pin "4") (pinfunction "4-ENABLE+_4") (pintype "passive"))
      (node (ref "J29") (pin "1") (pinfunction "1-HLFB+_1") (pintype "passive"))
      (node (ref "J29") (pin "2") (pinfunction "2-INPUT_B+_2") (pintype "passive"))
      (node (ref "J29") (pin "3") (pinfunction "3-INPUT_A+_3") (pintype "passive"))
      (node (ref "J29") (pin "4") (pinfunction "4-ENABLE+_4") (pintype "passive"))
      (node (ref "J30") (pin "1") (pinfunction "1-HLFB+_1") (pintype "passive"))
      (node (ref "J30") (pin "2") (pinfunction "2-INPUT_B+_2") (pintype "passive"))
      (node (ref "J30") (pin "3") (pinfunction "3-INPUT_A+_3") (pintype "passive"))
      (node (ref "J30") (pin "4") (pinfunction "4-ENABLE+_4") (pintype "passive"))
      (node (ref "J33") (pin "1") (pinfunction "1-HLFB+_1") (pintype "passive"))
      (node (ref "J33") (pin "2") (pinfunction "2-INPUT_B+_2") (pintype "passive"))
      (node (ref "J33") (pin "3") (pinfunction "3-INPUT_A+_3") (pintype "passive"))
      (node (ref "J33") (pin "4") (pinfunction "4-ENABLE+_4") (pintype "passive"))
      (node (ref "J34") (pin "1") (pinfunction "1-HLFB+_1") (pintype "passive"))
      (node (ref "J34") (pin "2") (pinfunction "2-INPUT_B+_2") (pintype "passive"))
      (node (ref "J34") (pin "3") (pinfunction "3-INPUT_A+_3") (pintype "passive"))
      (node (ref "J34") (pin "4") (pinfunction "4-ENABLE+_4") (pintype "passive"))
      (node (ref "J9") (pin "P$2") (pinfunction "P$2_P$2") (pintype "bidirectional"))
      (node (ref "R109") (pin "2") (pinfunction "2_2") (pintype "passive"))
      (node (ref "R113") (pin "2") (pinfunction "2_2") (pintype "passive"))
      (node (ref "R114") (pin "2") (pinfunction "2_2") (pintype "passive"))
      (node (ref "R115") (pin "2") (pinfunction "2_2") (pintype "passive"))
      (node (ref "R119") (pin "2") (pinfunction "2_2") (pintype "passive"))
      (node (ref "R120") (pin "2") (pinfunction "2_2") (pintype "passive"))
      (node (ref "R133") (pin "2") (pinfunction "2_2") (pintype "passive"))
      (node (ref "R137") (pin "2") (pinfunction "2_2") (pintype "passive"))
      (node (ref "R138") (pin "2") (pinfunction "2_2") (pintype "passive"))
      (node (ref "R139") (pin "2") (pinfunction "2_2") (pintype "passive"))
      (node (ref "R143") (pin "2") (pinfunction "2_2") (pintype "passive"))
      (node (ref "R144") (pin "2") (pinfunction "2_2") (pintype "passive"))
      (node (ref "R157") (pin "2") (pinfunction "2_2") (pintype "passive"))
      (node (ref "R161") (pin "2") (pinfunction "2_2") (pintype "passive"))
      (node (ref "R162") (pin "2") (pinfunction "2_2") (pintype "passive"))
      (node (ref "R163") (pin "2") (pinfunction "2_2") (pintype "passive"))
      (node (ref "R167") (pin "2") (pinfunction "2_2") (pintype "passive"))
      (node (ref "R168") (pin "2") (pinfunction "2_2") (pintype "passive"))
      (node (ref "R37") (pin "2") (pinfunction "2_2") (pintype "passive"))
      (node (ref "R41") (pin "2") (pinfunction "2_2") (pintype "passive"))
      (node (ref "R42") (pin "2") (pinfunction "2_2") (pintype "passive"))
      (node (ref "R43") (pin "2") (pinfunction "2_2") (pintype "passive"))
      (node (ref "R47") (pin "2") (pinfunction "2_2") (pintype "passive"))
      (node (ref "R48") (pin "2") (pinfunction "2_2") (pintype "passive"))
      (node (ref "R61") (pin "2") (pinfunction "2_2") (pintype "passive"))
      (node (ref "R65") (pin "2") (pinfunction "2_2") (pintype "passive"))
      (node (ref "R66") (pin "2") (pinfunction "2_2") (pintype "passive"))
      (node (ref "R67") (pin "2") (pinfunction "2_2") (pintype "passive"))
      (node (ref "R71") (pin "2") (pinfunction "2_2") (pintype "passive"))
      (node (ref "R72") (pin "2") (pinfunction "2_2") (pintype "passive"))
      (node (ref "R85") (pin "2") (pinfunction "2_2") (pintype "passive"))
      (node (ref "R89") (pin "2") (pinfunction "2_2") (pintype "passive"))
      (node (ref "R90") (pin "2") (pinfunction "2_2") (pintype "passive"))
      (node (ref "R91") (pin "2") (pinfunction "2_2") (pintype "passive"))
      (node (ref "R95") (pin "2") (pinfunction "2_2") (pintype "passive"))
      (node (ref "R96") (pin "2") (pinfunction "2_2") (pintype "passive"))
    )
    (net (code "233") (name "VDDIN") (class "Default")
      (node (ref "J2") (pin "P$2") (pinfunction "P$2_P$2") (pintype "bidirectional"))
      (node (ref "L1") (pin "1") (pinfunction "P$1_1") (pintype "bidirectional"))
    )
    (net (code "234") (name "VDD_1.2") (class "Default")
      (node (ref "C10") (pin "P$1") (pinfunction "1_P$1") (pintype "passive"))
      (node (ref "C11") (pin "P$1") (pinfunction "1_P$1") (pintype "passive"))
      (node (ref "U1") (pin "1") (pinfunction "VDD_1.2_1") (pintype "power_in"))
    )
    (net (code "235") (name "WF_A_DIR") (class "Default")
      (node (ref "R159") (pin "1") (pinfunction "1_1") (pintype "passive"))
    )
    (net (code "236") (name "WF_A_ENABLE") (class "Default")
      (node (ref "R160") (pin "1") (pinfunction "1_1") (pintype "passive"))
    )
    (net (code "237") (name "WF_A_HLFB_OUT") (class "Default")
      (node (ref "J33") (pin "5") (pinfunction "5-HLFB-_5") (pintype "passive"))
    )
    (net (code "238") (name "WF_A_MI_DIR") (class "Default")
      (node (ref "J33") (pin "7") (pinfunction "7-INPUT_A-_7") (pintype "passive"))
      (node (ref "R161") (pin "1") (pinfunction "1_1") (pintype "passive"))
      (node (ref "U71") (pin "3") (pinfunction "C(3)_3") (pintype "input"))
    )
    (net (code "239") (name "WF_A_MI_ENABLE") (class "Default")
      (node (ref "J33") (pin "8") (pinfunction "8-ENABLE-_8") (pintype "passive"))
      (node (ref "R162") (pin "1") (pinfunction "1_1") (pintype "passive"))
      (node (ref "U72") (pin "3") (pinfunction "C(3)_3") (pintype "input"))
    )
    (net (code "240") (name "WF_A_MI_STEP") (class "Default")
      (node (ref "J33") (pin "6") (pinfunction "6-INPUT_B-_6") (pintype "passive"))
      (node (ref "R157") (pin "1") (pinfunction "1_1") (pintype "passive"))
      (node (ref "U70") (pin "3") (pinfunction "C(3)_3") (pintype "input"))
    )
    (net (code "241") (name "WF_A_STEP") (class "Default")
      (node (ref "R158") (pin "1") (pinfunction "1_1") (pintype "passive"))
    )
    (net (code "242") (name "WF_B_DIR") (class "Default")
      (node (ref "R165") (pin "1") (pinfunction "1_1") (pintype "passive"))
    )
    (net (code "243") (name "WF_B_ENABLE") (class "Default")
      (node (ref "R166") (pin "1") (pinfunction "1_1") (pintype "passive"))
    )
    (net (code "244") (name "WF_B_HLFB_OUT") (class "Default")
      (node (ref "J34") (pin "5") (pinfunction "5-HLFB-_5") (pintype "passive"))
    )
    (net (code "245") (name "WF_B_MI_ENABLE") (class "Default")
      (node (ref "J34") (pin "8") (pinfunction "8-ENABLE-_8") (pintype "passive"))
      (node (ref "R168") (pin "1") (pinfunction "1_1") (pintype "passive"))
      (node (ref "U75") (pin "3") (pinfunction "C(3)_3") (pintype "input"))
    )
    (net (code "246") (name "WF_B_MI_STEP") (class "Default")
      (node (ref "J34") (pin "6") (pinfunction "6-INPUT_B-_6") (pintype "passive"))
      (node (ref "R163") (pin "1") (pinfunction "1_1") (pintype "passive"))
      (node (ref "U73") (pin "3") (pinfunction "C(3)_3") (pintype "input"))
    )
    (net (code "247") (name "WF_B_STEP") (class "Default")
      (node (ref "R164") (pin "1") (pinfunction "1_1") (pintype "passive"))
    )
    (net (code "248") (name "XCIN") (class "Default")
      (node (ref "C32") (pin "P$1") (pinfunction "1_P$1") (pintype "passive"))
      (node (ref "U3") (pin "20") (pinfunction "XCIN_20") (pintype "bidirectional"))
      (node (ref "X3") (pin "P$1") (pinfunction "P$1_P$1") (pintype "bidirectional"))
    )
    (net (code "249") (name "XCOUT") (class "Default")
      (node (ref "C37") (pin "P$1") (pinfunction "1_P$1") (pintype "passive"))
      (node (ref "U3") (pin "21") (pinfunction "XCOUT_21") (pintype "bidirectional"))
      (node (ref "X3") (pin "P$2") (pinfunction "P$2_P$2") (pintype "bidirectional"))
    )
    (net (code "250") (name "XII") (class "Default")
      (node (ref "C1") (pin "P$1") (pinfunction "1_P$1") (pintype "passive"))
      (node (ref "U1") (pin "8") (pinfunction "XI_8") (pintype "input"))
      (node (ref "X1") (pin "1") (pinfunction "1_1") (pintype "bidirectional"))
    )
    (net (code "251") (name "XOO") (class "Default")
      (node (ref "C2") (pin "P$1") (pinfunction "1_P$1") (pintype "passive"))
      (node (ref "U1") (pin "7") (pinfunction "XO_7") (pintype "output"))
      (node (ref "X1") (pin "3") (pinfunction "3_3") (pintype "bidirectional"))
    )
    (net (code "252") (name "XTAL1") (class "Default")
      (node (ref "C17") (pin "P$1") (pinfunction "1_P$1") (pintype "passive"))
      (node (ref "U3") (pin "23") (pinfunction "P2_13/XTAL_23") (pintype "bidirectional"))
      (node (ref "X2") (pin "1") (pinfunction "1_1") (pintype "bidirectional"))
    )
    (net (code "253") (name "XTAL2") (class "Default")
      (node (ref "C18") (pin "P$1") (pinfunction "1_P$1") (pintype "passive"))
      (node (ref "U3") (pin "24") (pinfunction "P2_12/EXTAL_24") (pintype "bidirectional"))
      (node (ref "X2") (pin "3") (pinfunction "3_3") (pintype "bidirectional"))
    )
    (net (code "254") (name "X_A_DIR") (class "Default")
      (node (ref "R39") (pin "1") (pinfunction "1_1") (pintype "passive"))
    )
    (net (code "255") (name "X_A_ENABLE") (class "Default")
      (node (ref "R40") (pin "1") (pinfunction "1_1") (pintype "passive"))
    )
    (net (code "256") (name "X_A_HLFB_OUT") (class "Default")
      (node (ref "J13") (pin "5") (pinfunction "5-HLFB-_5") (pintype "passive"))
    )
    (net (code "257") (name "X_A_MI_DIR") (class "Default")
      (node (ref "J13") (pin "7") (pinfunction "7-INPUT_A-_7") (pintype "passive"))
      (node (ref "R41") (pin "1") (pinfunction "1_1") (pintype "passive"))
      (node (ref "U11") (pin "3") (pinfunction "C(3)_3") (pintype "input"))
    )
    (net (code "258") (name "X_A_MI_ENABLE") (class "Default")
      (node (ref "J13") (pin "8") (pinfunction "8-ENABLE-_8") (pintype "passive"))
      (node (ref "R42") (pin "1") (pinfunction "1_1") (pintype "passive"))
      (node (ref "U12") (pin "3") (pinfunction "C(3)_3") (pintype "input"))
    )
    (net (code "259") (name "X_A_MI_STEP") (class "Default")
      (node (ref "J13") (pin "6") (pinfunction "6-INPUT_B-_6") (pintype "passive"))
      (node (ref "R37") (pin "1") (pinfunction "1_1") (pintype "passive"))
      (node (ref "U10") (pin "3") (pinfunction "C(3)_3") (pintype "input"))
    )
    (net (code "260") (name "X_A_STEP") (class "Default")
      (node (ref "R38") (pin "1") (pinfunction "1_1") (pintype "passive"))
    )
    (net (code "261") (name "X_B_DIR") (class "Default")
      (node (ref "R45") (pin "1") (pinfunction "1_1") (pintype "passive"))
    )
    (net (code "262") (name "X_B_ENABLE") (class "Default")
      (node (ref "R46") (pin "1") (pinfunction "1_1") (pintype "passive"))
    )
    (net (code "263") (name "X_B_HLFB_OUT") (class "Default")
      (node (ref "J14") (pin "5") (pinfunction "5-HLFB-_5") (pintype "passive"))
    )
    (net (code "264") (name "X_B_MI_DIR") (class "Default")
      (node (ref "J14") (pin "7") (pinfunction "7-INPUT_A-_7") (pintype "passive"))
      (node (ref "R47") (pin "1") (pinfunction "1_1") (pintype "passive"))
      (node (ref "U14") (pin "3") (pinfunction "C(3)_3") (pintype "input"))
    )
    (net (code "265") (name "X_B_MI_ENABLE") (class "Default")
      (node (ref "J14") (pin "8") (pinfunction "8-ENABLE-_8") (pintype "passive"))
      (node (ref "R48") (pin "1") (pinfunction "1_1") (pintype "passive"))
      (node (ref "U15") (pin "3") (pinfunction "C(3)_3") (pintype "input"))
    )
    (net (code "266") (name "X_B_MI_STEP") (class "Default")
      (node (ref "J14") (pin "6") (pinfunction "6-INPUT_B-_6") (pintype "passive"))
      (node (ref "R43") (pin "1") (pinfunction "1_1") (pintype "passive"))
      (node (ref "U13") (pin "3") (pinfunction "C(3)_3") (pintype "input"))
    )
    (net (code "267") (name "X_B_STEP") (class "Default")
      (node (ref "R44") (pin "1") (pinfunction "1_1") (pintype "passive"))
    )
    (net (code "268") (name "Y_A_DIR") (class "Default")
      (node (ref "R63") (pin "1") (pinfunction "1_1") (pintype "passive"))
    )
    (net (code "269") (name "Y_A_ENABLE") (class "Default")
      (node (ref "R64") (pin "1") (pinfunction "1_1") (pintype "passive"))
    )
    (net (code "270") (name "Y_A_HLFB_OUT") (class "Default")
      (node (ref "J17") (pin "5") (pinfunction "5-HLFB-_5") (pintype "passive"))
    )
    (net (code "271") (name "Y_A_MI_DIR") (class "Default")
      (node (ref "J17") (pin "7") (pinfunction "7-INPUT_A-_7") (pintype "passive"))
      (node (ref "R65") (pin "1") (pinfunction "1_1") (pintype "passive"))
      (node (ref "U23") (pin "3") (pinfunction "C(3)_3") (pintype "input"))
    )
    (net (code "272") (name "Y_A_MI_ENABLE") (class "Default")
      (node (ref "J17") (pin "8") (pinfunction "8-ENABLE-_8") (pintype "passive"))
      (node (ref "R66") (pin "1") (pinfunction "1_1") (pintype "passive"))
      (node (ref "U24") (pin "3") (pinfunction "C(3)_3") (pintype "input"))
    )
    (net (code "273") (name "Y_A_MI_STEP") (class "Default")
      (node (ref "J17") (pin "6") (pinfunction "6-INPUT_B-_6") (pintype "passive"))
      (node (ref "R61") (pin "1") (pinfunction "1_1") (pintype "passive"))
      (node (ref "U22") (pin "3") (pinfunction "C(3)_3") (pintype "input"))
    )
    (net (code "274") (name "Y_A_STEP") (class "Default")
      (node (ref "R62") (pin "1") (pinfunction "1_1") (pintype "passive"))
    )
    (net (code "275") (name "Y_B_DIR") (class "Default")
      (node (ref "R69") (pin "1") (pinfunction "1_1") (pintype "passive"))
    )
    (net (code "276") (name "Y_B_ENABLE") (class "Default")
      (node (ref "R70") (pin "1") (pinfunction "1_1") (pintype "passive"))
    )
    (net (code "277") (name "Y_B_HLFB_OUT") (class "Default")
      (node (ref "J18") (pin "5") (pinfunction "5-HLFB-_5") (pintype "passive"))
    )
    (net (code "278") (name "Y_B_MI_DIR") (class "Default")
      (node (ref "J18") (pin "7") (pinfunction "7-INPUT_A-_7") (pintype "passive"))
      (node (ref "R71") (pin "1") (pinfunction "1_1") (pintype "passive"))
      (node (ref "U26") (pin "3") (pinfunction "C(3)_3") (pintype "input"))
    )
    (net (code "279") (name "Y_B_MI_ENABLE") (class "Default")
      (node (ref "J18") (pin "8") (pinfunction "8-ENABLE-_8") (pintype "passive"))
      (node (ref "R72") (pin "1") (pinfunction "1_1") (pintype "passive"))
      (node (ref "U27") (pin "3") (pinfunction "C(3)_3") (pintype "input"))
    )
    (net (code "280") (name "Y_B_MI_STEP") (class "Default")
      (node (ref "J18") (pin "6") (pinfunction "6-INPUT_B-_6") (pintype "passive"))
      (node (ref "R67") (pin "1") (pinfunction "1_1") (pintype "passive"))
      (node (ref "U25") (pin "3") (pinfunction "C(3)_3") (pintype "input"))
    )
    (net (code "281") (name "Y_B_STEP") (class "Default")
      (node (ref "R68") (pin "1") (pinfunction "1_1") (pintype "passive"))
    )
    (net (code "282") (name "Z_A_DIR") (class "Default")
      (node (ref "R87") (pin "1") (pinfunction "1_1") (pintype "passive"))
    )
    (net (code "283") (name "Z_A_ENABLE") (class "Default")
      (node (ref "R88") (pin "1") (pinfunction "1_1") (pintype "passive"))
    )
    (net (code "284") (name "Z_A_HLFB_OUT") (class "Default")
      (node (ref "J21") (pin "5") (pinfunction "5-HLFB-_5") (pintype "passive"))
    )
    (net (code "285") (name "Z_A_MI_DIR") (class "Default")
      (node (ref "J21") (pin "7") (pinfunction "7-INPUT_A-_7") (pintype "passive"))
      (node (ref "R89") (pin "1") (pinfunction "1_1") (pintype "passive"))
      (node (ref "U35") (pin "3") (pinfunction "C(3)_3") (pintype "input"))
    )
    (net (code "286") (name "Z_A_MI_ENABLE") (class "Default")
      (node (ref "J21") (pin "8") (pinfunction "8-ENABLE-_8") (pintype "passive"))
      (node (ref "R90") (pin "1") (pinfunction "1_1") (pintype "passive"))
      (node (ref "U36") (pin "3") (pinfunction "C(3)_3") (pintype "input"))
    )
    (net (code "287") (name "Z_A_MI_STEP") (class "Default")
      (node (ref "J21") (pin "6") (pinfunction "6-INPUT_B-_6") (pintype "passive"))
      (node (ref "R85") (pin "1") (pinfunction "1_1") (pintype "passive"))
      (node (ref "U34") (pin "3") (pinfunction "C(3)_3") (pintype "input"))
    )
    (net (code "288") (name "Z_A_STEP") (class "Default")
      (node (ref "R86") (pin "1") (pinfunction "1_1") (pintype "passive"))
    )
    (net (code "289") (name "Z_B_DIR") (class "Default")
      (node (ref "R93") (pin "1") (pinfunction "1_1") (pintype "passive"))
    )
    (net (code "290") (name "Z_B_ENABLE") (class "Default")
      (node (ref "R94") (pin "1") (pinfunction "1_1") (pintype "passive"))
    )
    (net (code "291") (name "Z_B_HLFB_OUT") (class "Default")
      (node (ref "J22") (pin "5") (pinfunction "5-HLFB-_5") (pintype "passive"))
    )
    (net (code "292") (name "Z_B_MI_DIR") (class "Default")
      (node (ref "J22") (pin "7") (pinfunction "7-INPUT_A-_7") (pintype "passive"))
      (node (ref "R95") (pin "1") (pinfunction "1_1") (pintype "passive"))
      (node (ref "U38") (pin "3") (pinfunction "C(3)_3") (pintype "input"))
    )
    (net (code "293") (name "Z_B_MI_ENABLE") (class "Default")
      (node (ref "J22") (pin "8") (pinfunction "8-ENABLE-_8") (pintype "passive"))
      (node (ref "R96") (pin "1") (pinfunction "1_1") (pintype "passive"))
      (node (ref "U39") (pin "3") (pinfunction "C(3)_3") (pintype "input"))
    )
    (net (code "294") (name "Z_B_MI_STEP") (class "Default")
      (node (ref "J22") (pin "6") (pinfunction "6-INPUT_B-_6") (pintype "passive"))
      (node (ref "R91") (pin "1") (pinfunction "1_1") (pintype "passive"))
      (node (ref "U37") (pin "3") (pinfunction "C(3)_3") (pintype "input"))
    )
    (net (code "295") (name "Z_B_STEP") (class "Default")
      (node (ref "R92") (pin "1") (pinfunction "1_1") (pintype "passive"))
    )
    (net (code "296") (name "unconnected-(J27-PadP$1)") (class "Default")
      (node (ref "J27") (pin "P$1") (pinfunction "P$1_P$1") (pintype "bidirectional"))
    )
    (net (code "297") (name "unconnected-(J27-PadP$2)") (class "Default")
      (node (ref "J27") (pin "P$2") (pinfunction "P$2_P$2") (pintype "bidirectional"))
    )
    (net (code "298") (name "unconnected-(J28-PadP$1)") (class "Default")
      (node (ref "J28") (pin "P$1") (pinfunction "P$1_P$1") (pintype "bidirectional"))
    )
    (net (code "299") (name "unconnected-(J28-PadP$2)") (class "Default")
      (node (ref "J28") (pin "P$2") (pinfunction "P$2_P$2") (pintype "bidirectional"))
    )
    (net (code "300") (name "unconnected-(J31-PadP$1)") (class "Default")
      (node (ref "J31") (pin "P$1") (pinfunction "P$1_P$1") (pintype "bidirectional"))
    )
    (net (code "301") (name "unconnected-(J31-PadP$2)") (class "Default")
      (node (ref "J31") (pin "P$2") (pinfunction "P$2_P$2") (pintype "bidirectional"))
    )
    (net (code "302") (name "unconnected-(J32-PadP$1)") (class "Default")
      (node (ref "J32") (pin "P$1") (pinfunction "P$1_P$1") (pintype "bidirectional"))
    )
    (net (code "303") (name "unconnected-(J32-PadP$2)") (class "Default")
      (node (ref "J32") (pin "P$2") (pinfunction "P$2_P$2") (pintype "bidirectional"))
    )
    (net (code "304") (name "unconnected-(J35-PadP$1)") (class "Default")
      (node (ref "J35") (pin "P$1") (pinfunction "P$1_P$1") (pintype "bidirectional"))
    )
    (net (code "305") (name "unconnected-(J35-PadP$2)") (class "Default")
      (node (ref "J35") (pin "P$2") (pinfunction "P$2_P$2") (pintype "bidirectional"))
    )
    (net (code "306") (name "unconnected-(J36-PadP$1)") (class "Default")
      (node (ref "J36") (pin "P$1") (pinfunction "P$1_P$1") (pintype "bidirectional"))
    )
    (net (code "307") (name "unconnected-(J36-PadP$2)") (class "Default")
      (node (ref "J36") (pin "P$2") (pinfunction "P$2_P$2") (pintype "bidirectional"))
    )
    (net (code "308") (name "unconnected-(J37-PadP$1)") (class "Default")
      (node (ref "J37") (pin "P$1") (pinfunction "P$1_P$1") (pintype "bidirectional"))
    )
    (net (code "309") (name "unconnected-(J37-PadP$2)") (class "Default")
      (node (ref "J37") (pin "P$2") (pinfunction "P$2_P$2") (pintype "bidirectional"))
    )
    (net (code "310") (name "unconnected-(J38-PadP$1)") (class "Default")
      (node (ref "J38") (pin "P$1") (pinfunction "P$1_P$1") (pintype "bidirectional"))
    )
    (net (code "311") (name "unconnected-(J38-PadP$2)") (class "Default")
      (node (ref "J38") (pin "P$2") (pinfunction "P$2_P$2") (pintype "bidirectional"))
    )
    (net (code "312") (name "unconnected-(U3-P3_3-Pad85)") (class "Default")
      (node (ref "U3") (pin "85") (pinfunction "P3_3_85") (pintype "bidirectional"))
    )
    (net (code "313") (name "unconnected-(U3-VBAT-Pad18)") (class "Default")
      (node (ref "U3") (pin "18") (pinfunction "VBAT_18") (pintype "bidirectional"))
    )
  )
)
